# rel-8bit-computer.net
KiCad netlist of a schematic drawn in EAGLE
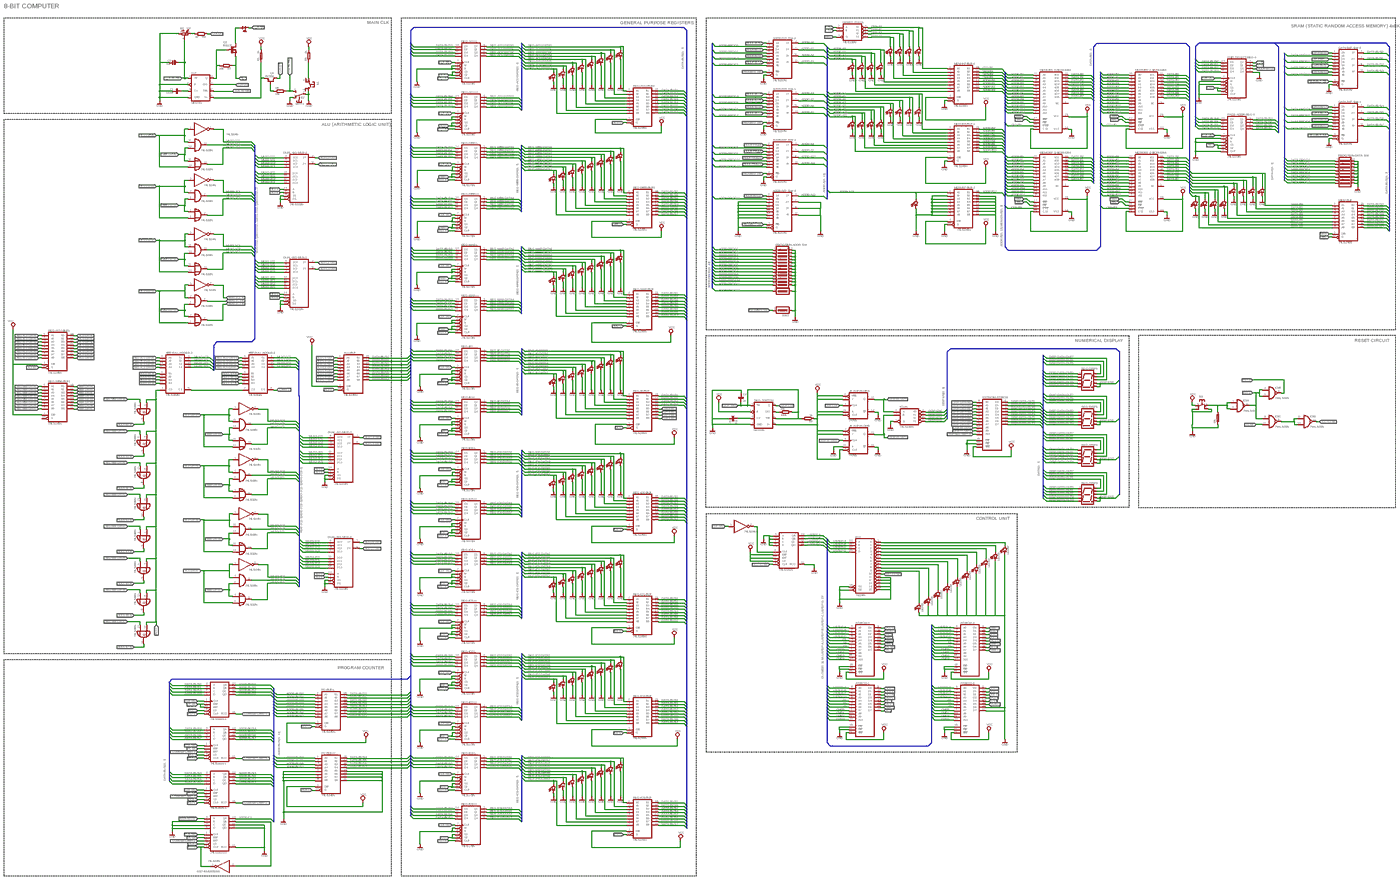
[diagram p0: schematic, sheet 1, overview]
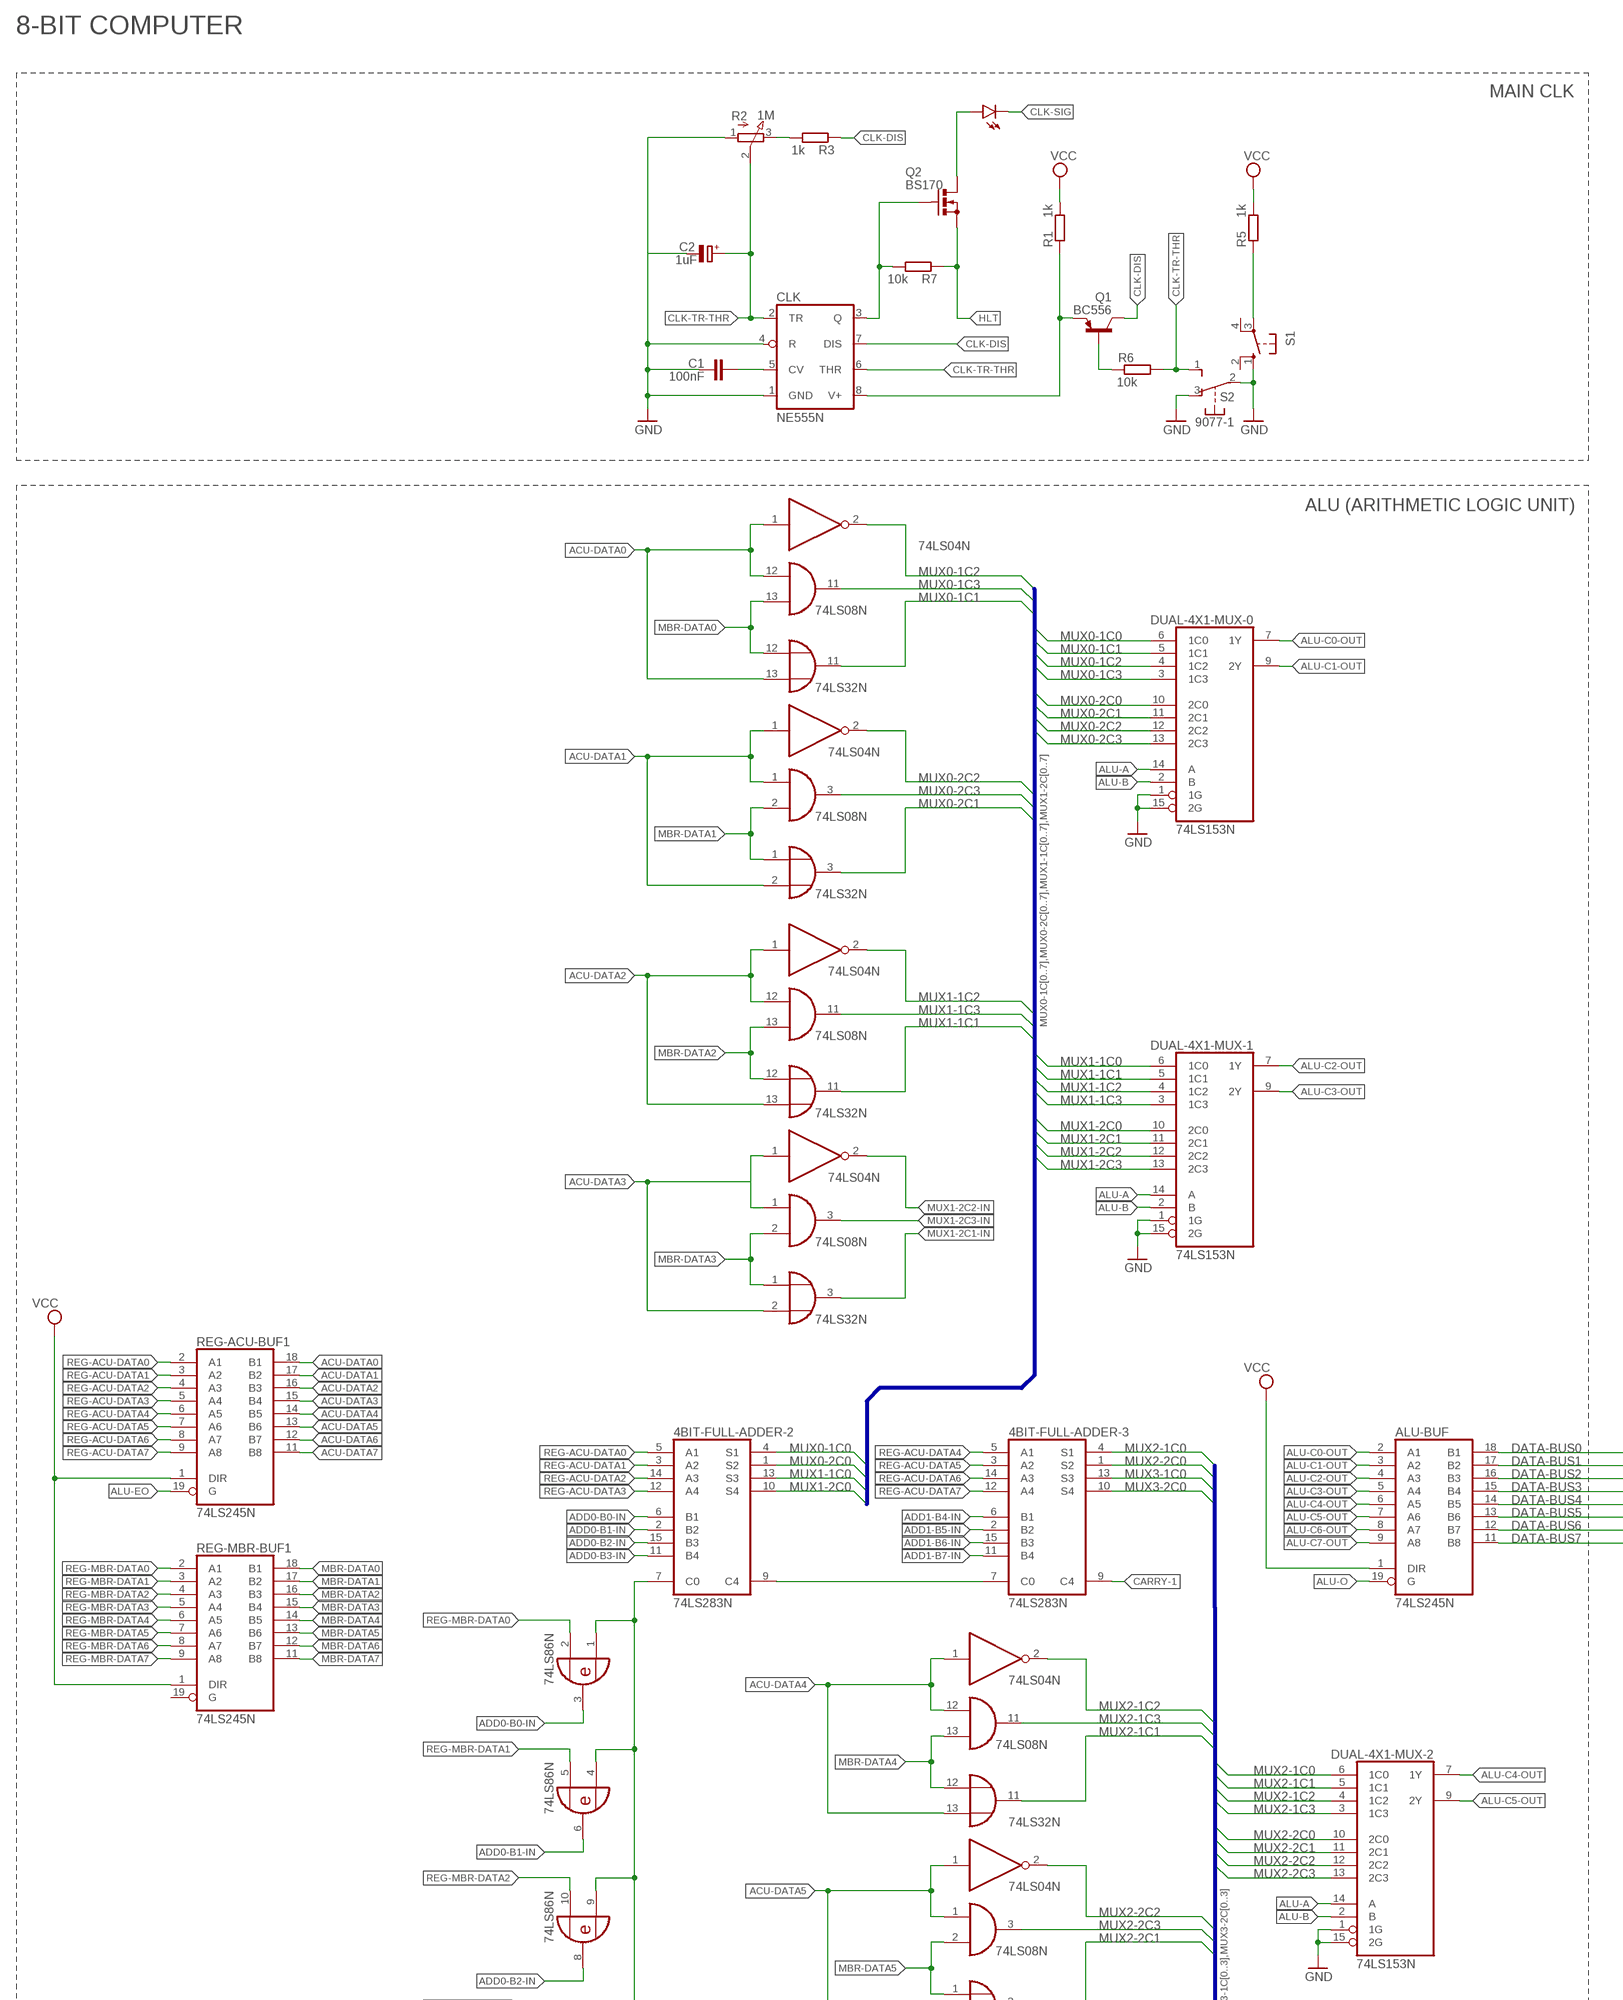
[diagram p1: schematic, sheet 1, part 1 of 8]
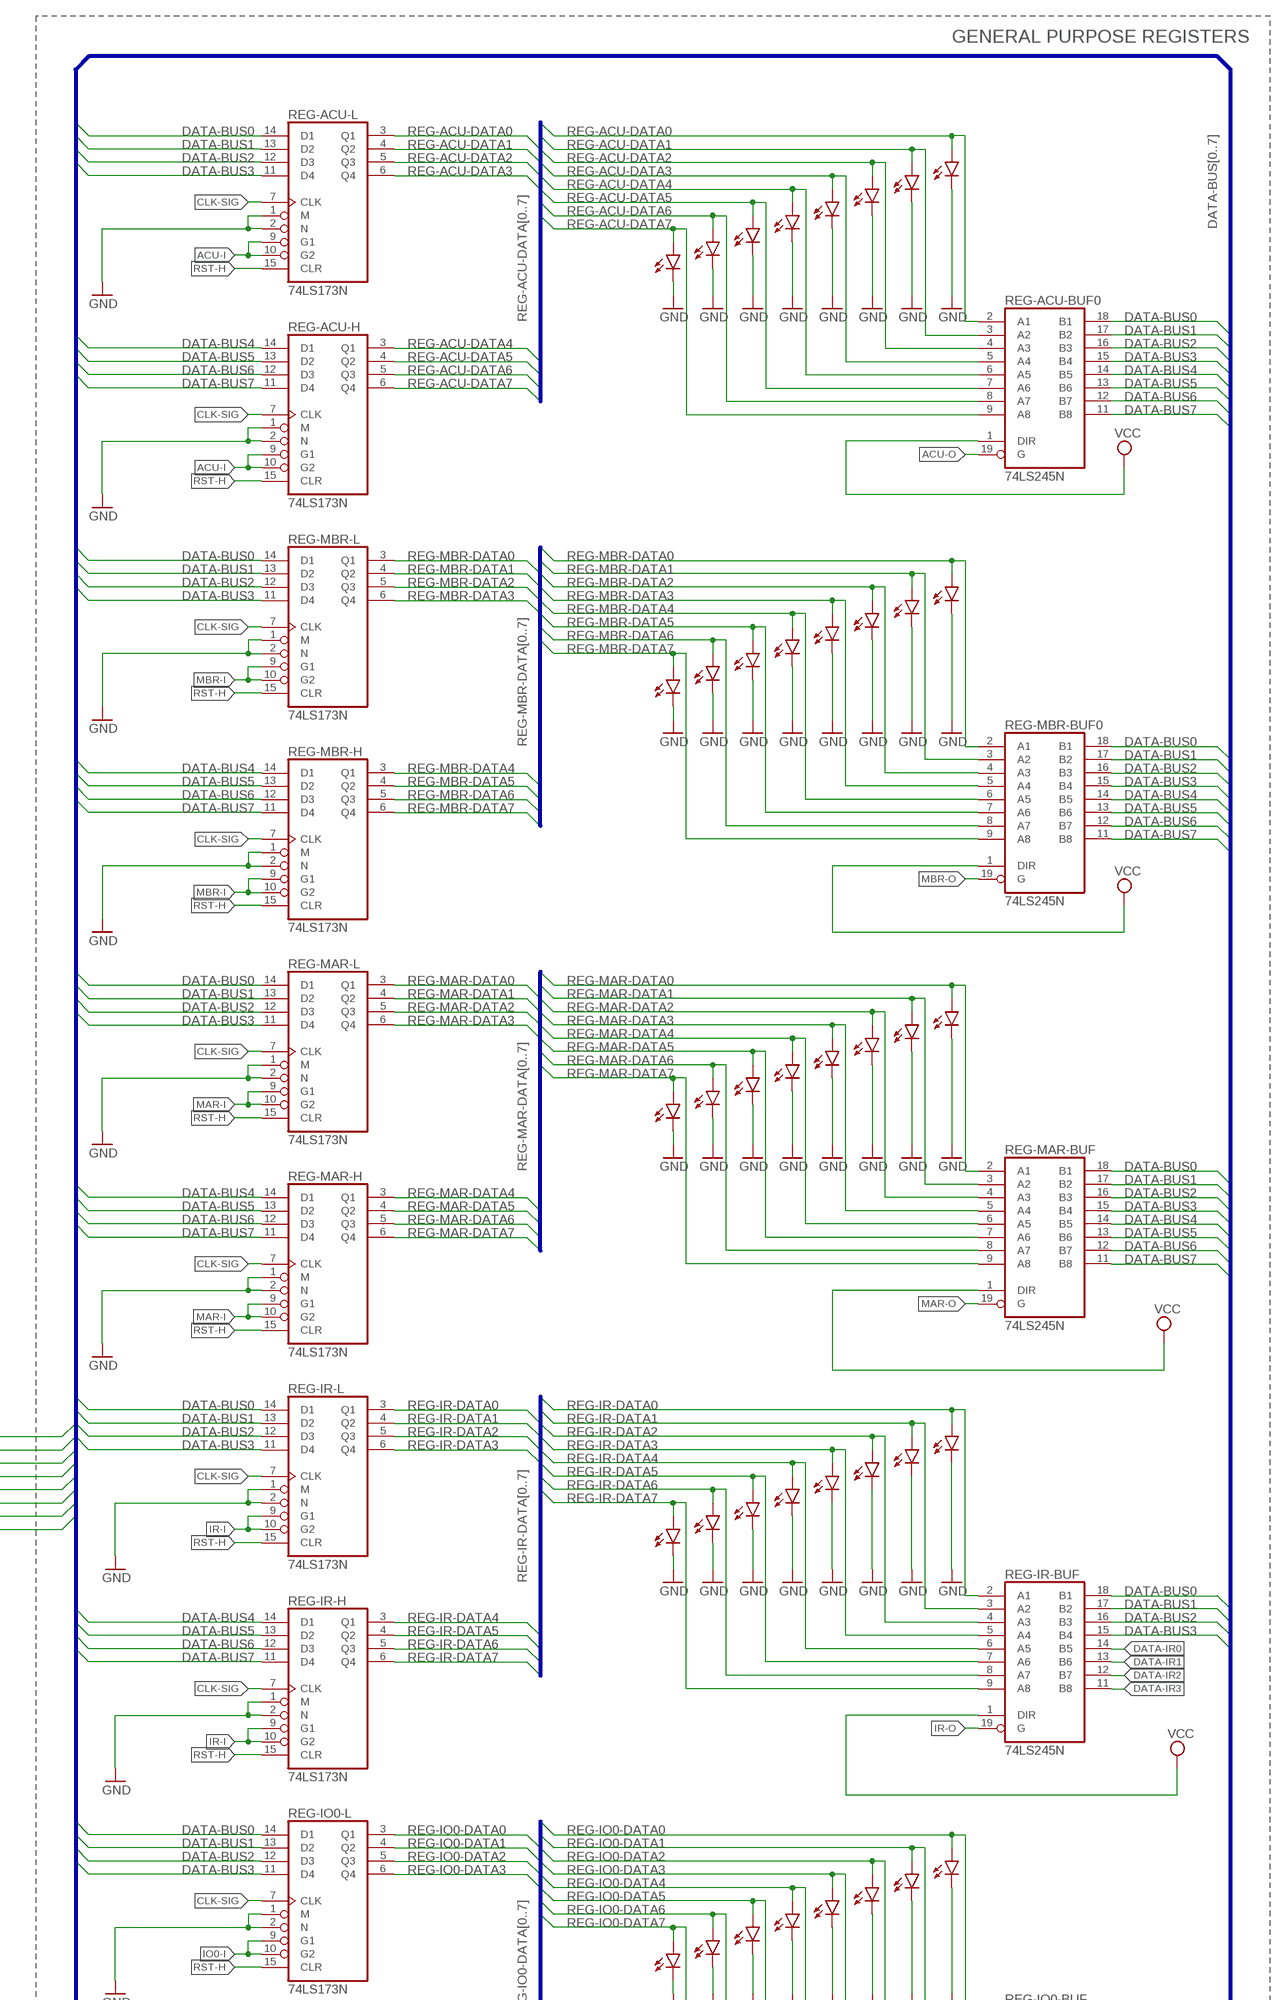
[diagram p2: schematic, sheet 1, part 2 of 8]
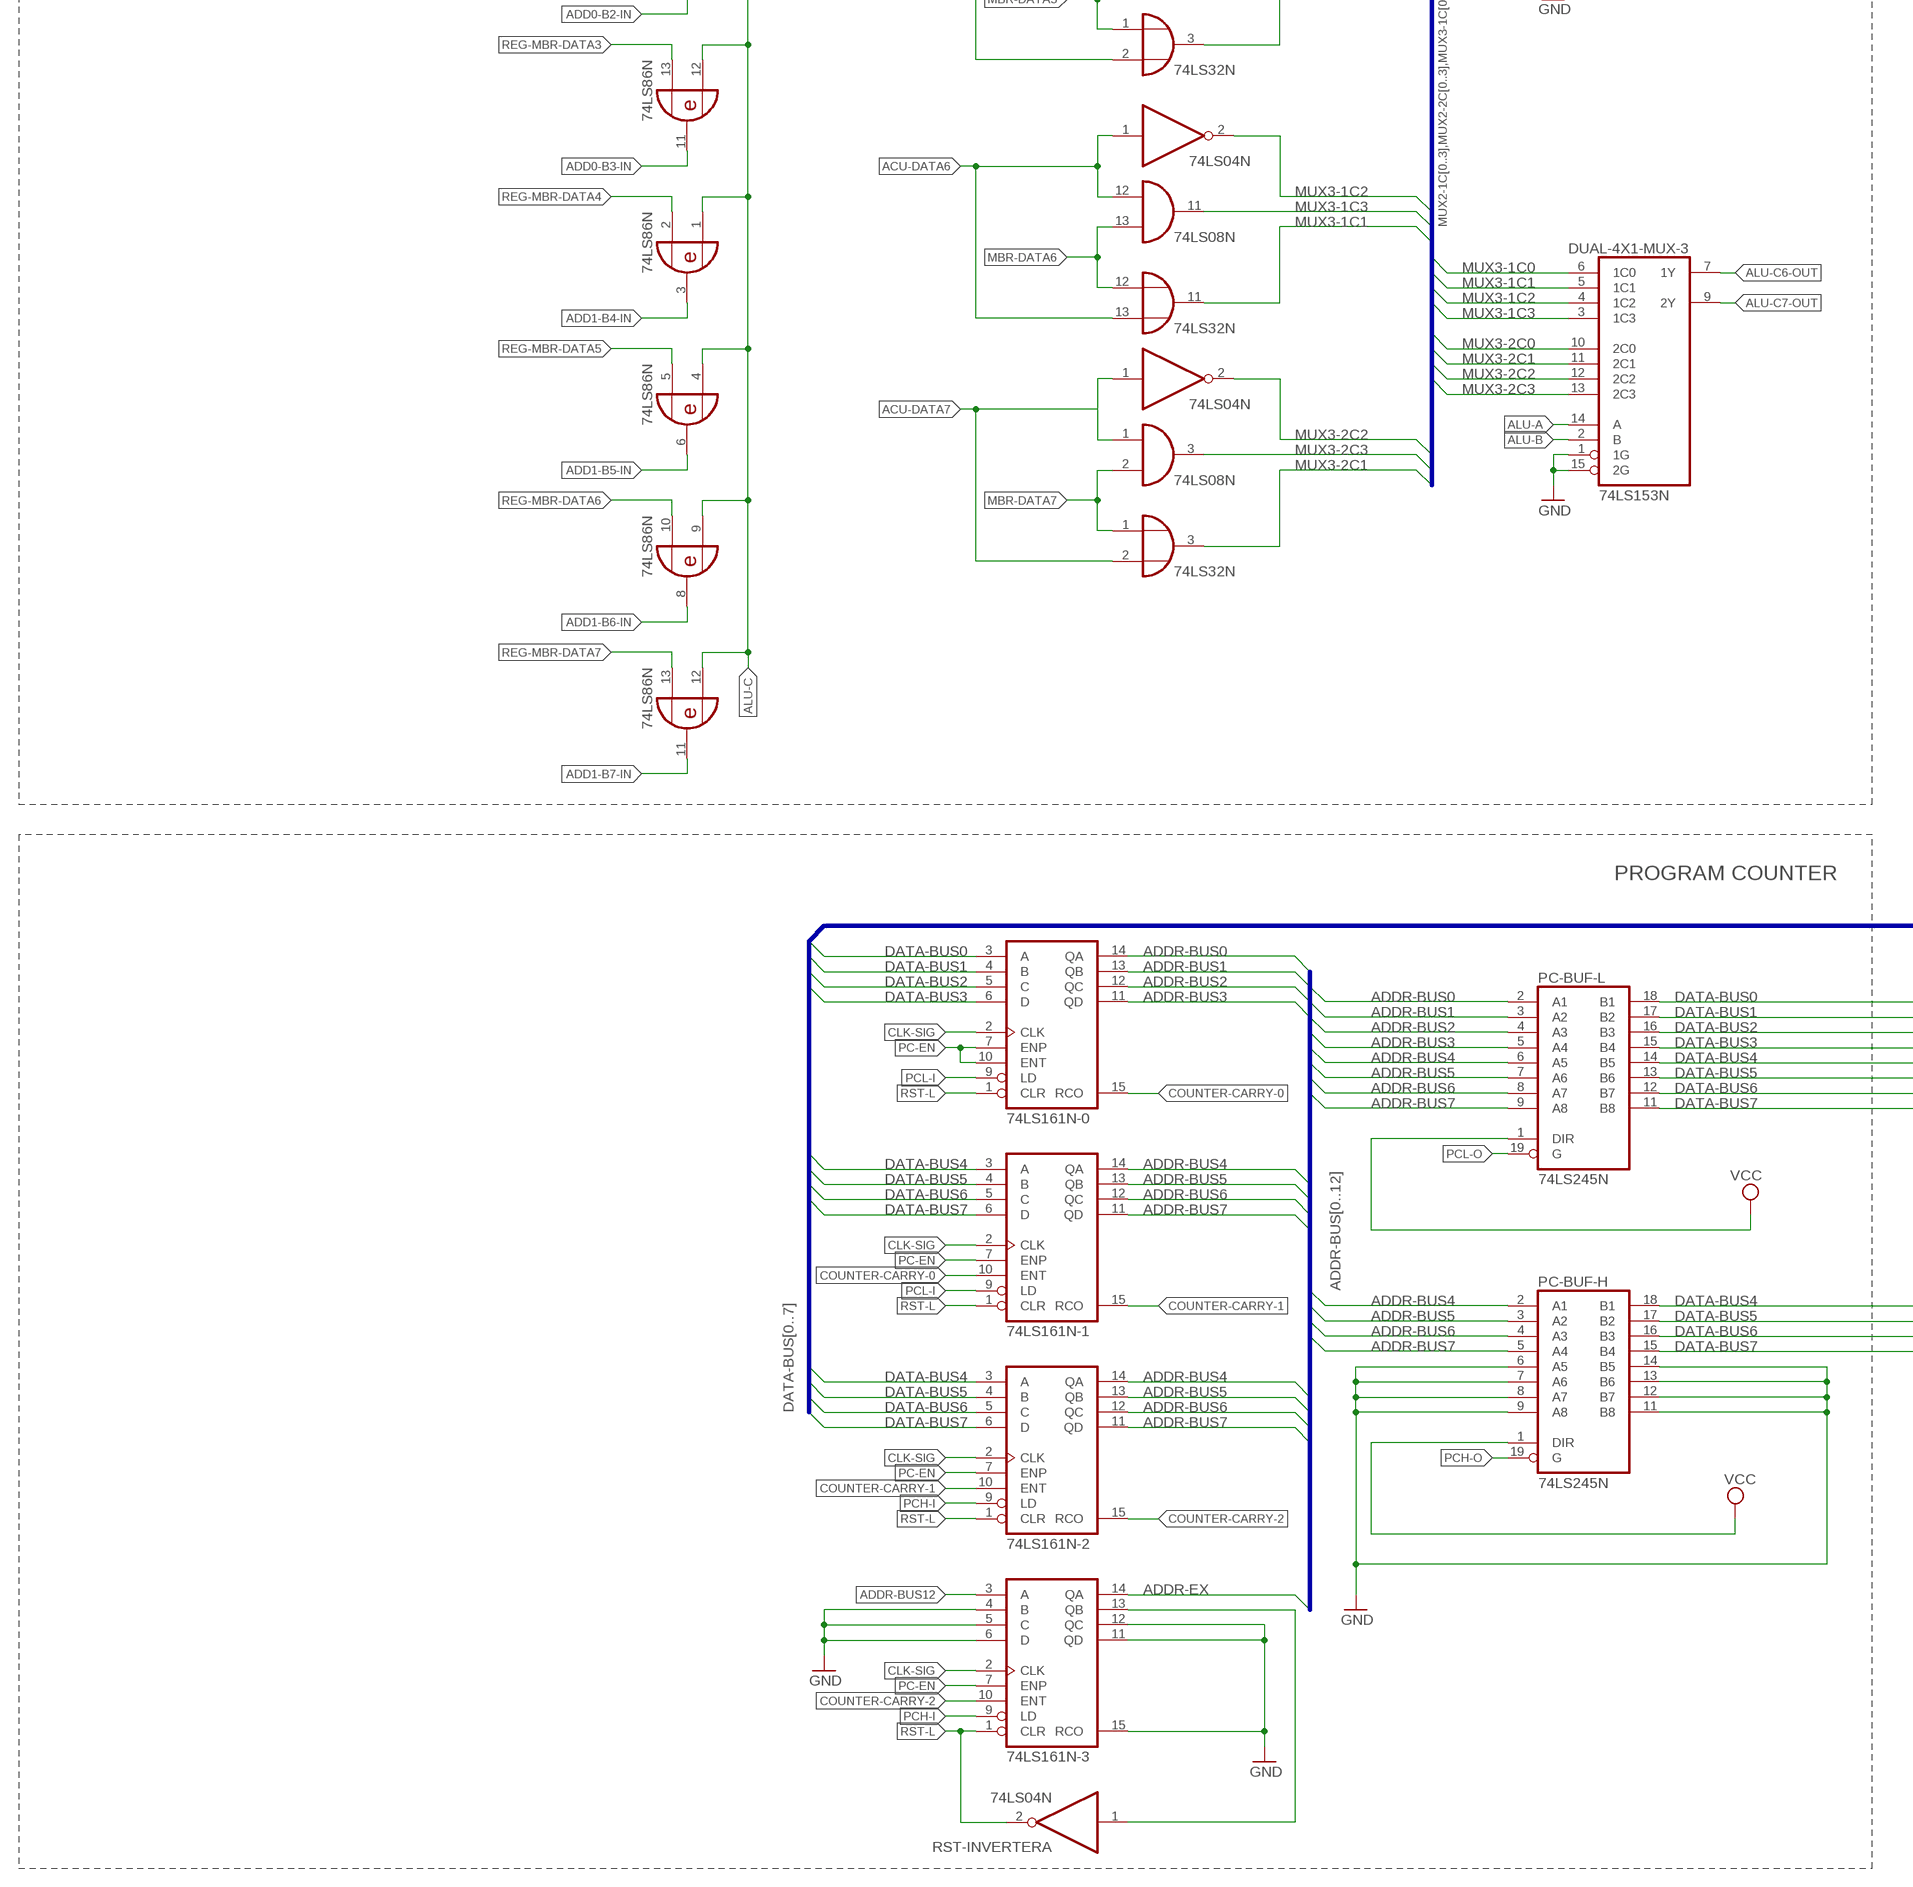
[diagram p3: schematic, sheet 1, part 3 of 8]
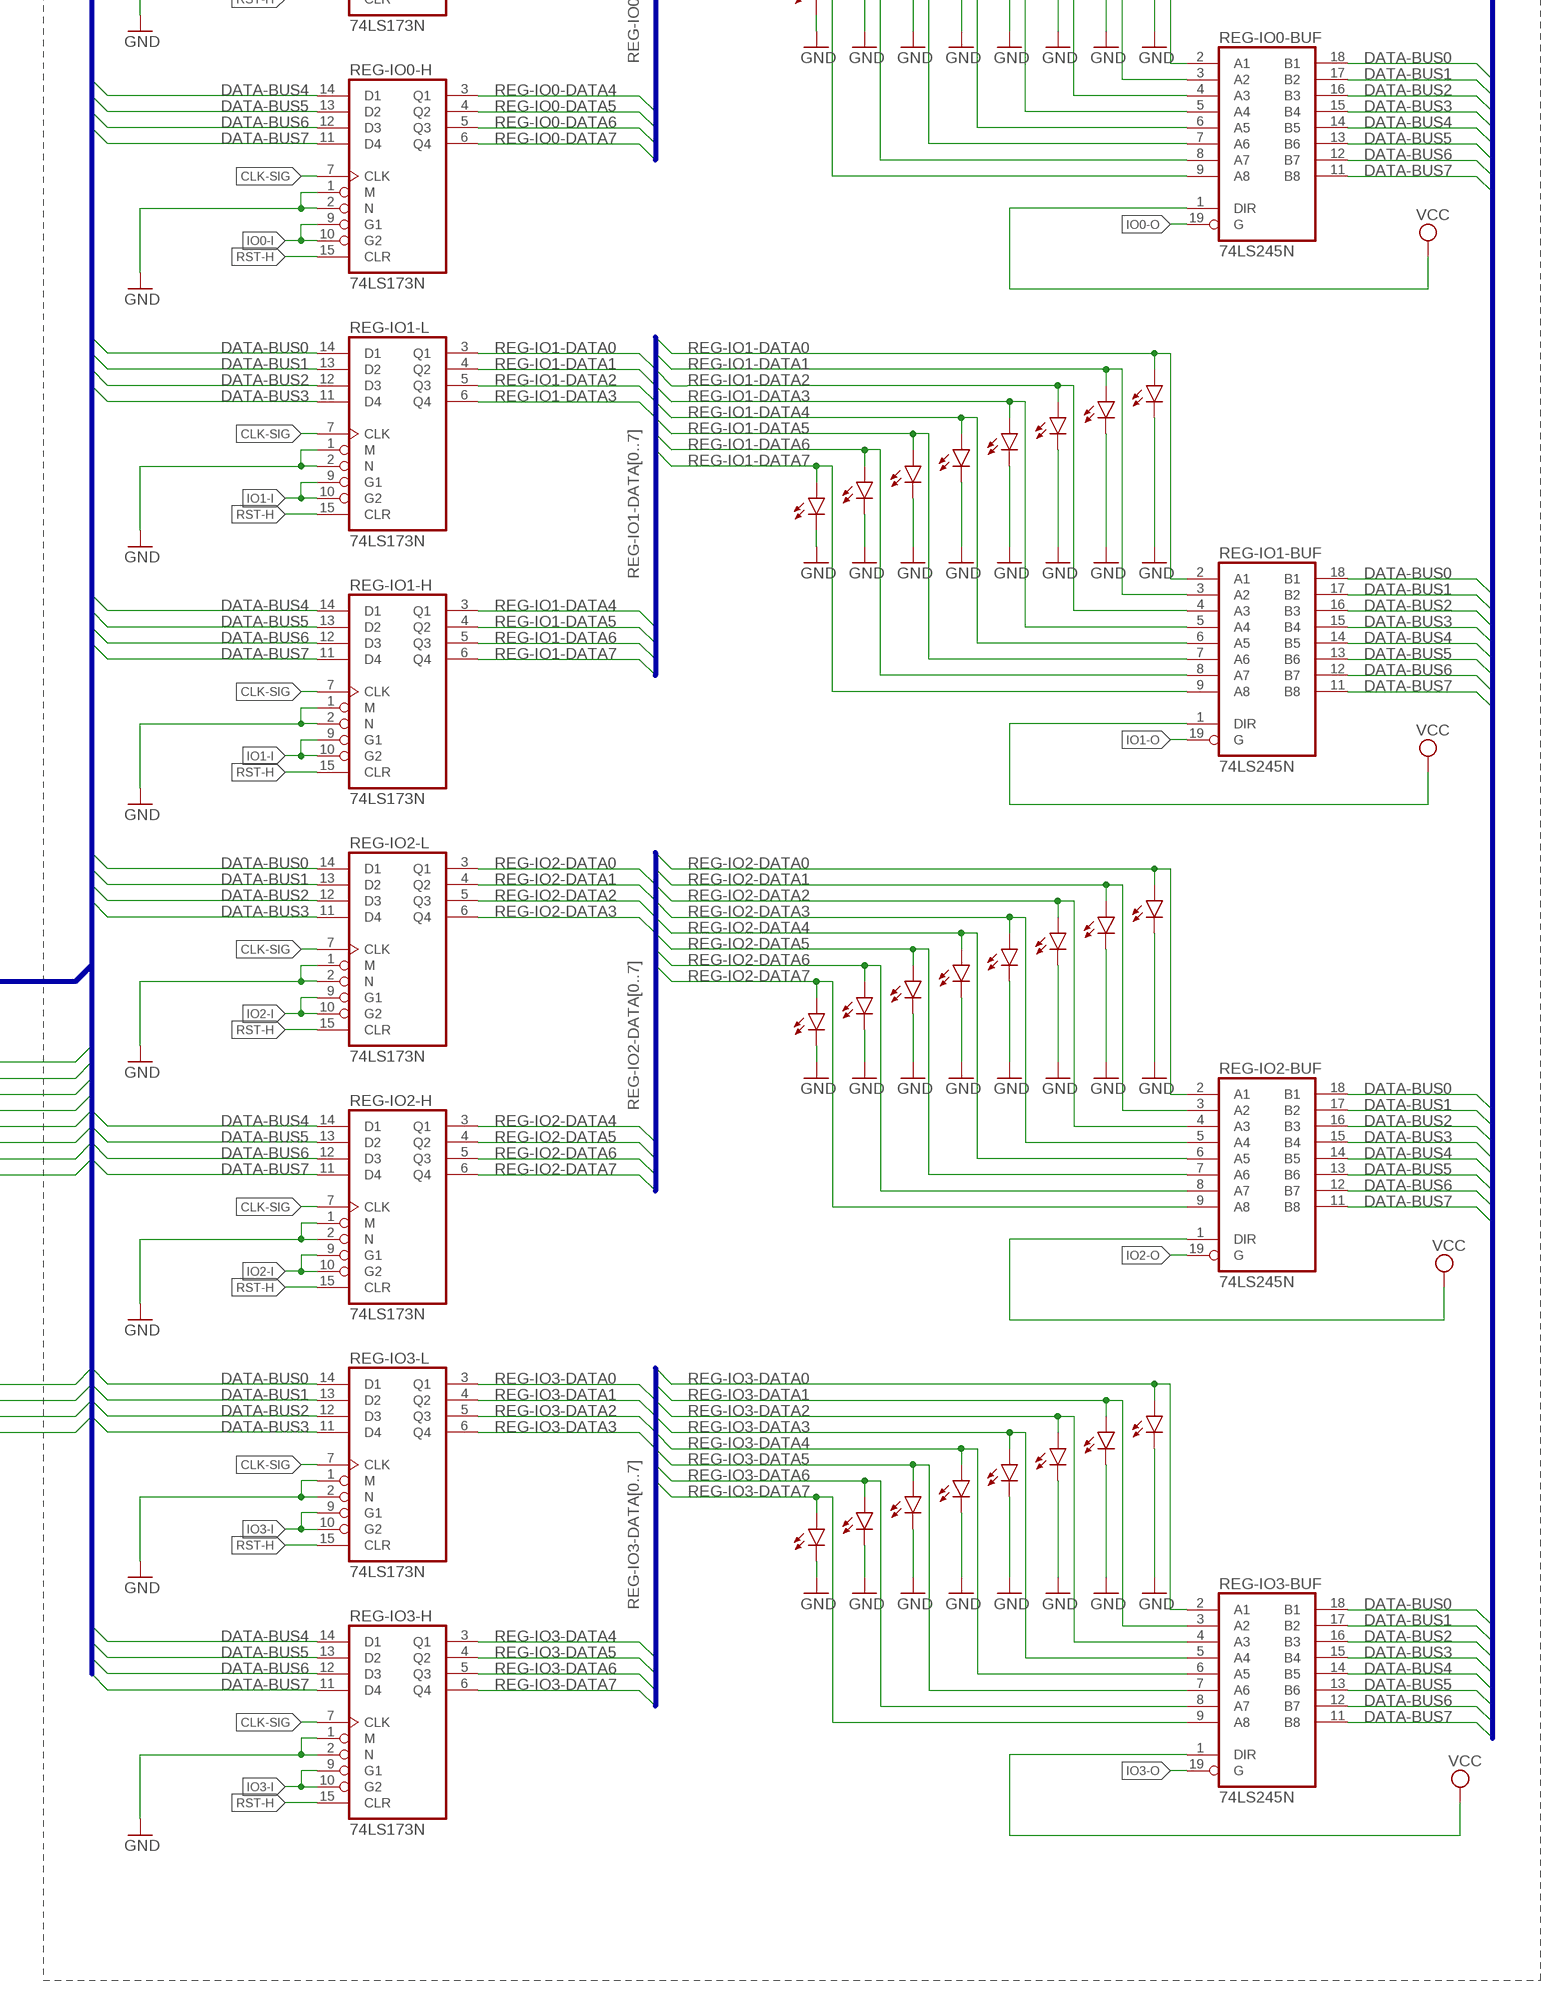
[diagram p4: schematic, sheet 1, part 4 of 8]
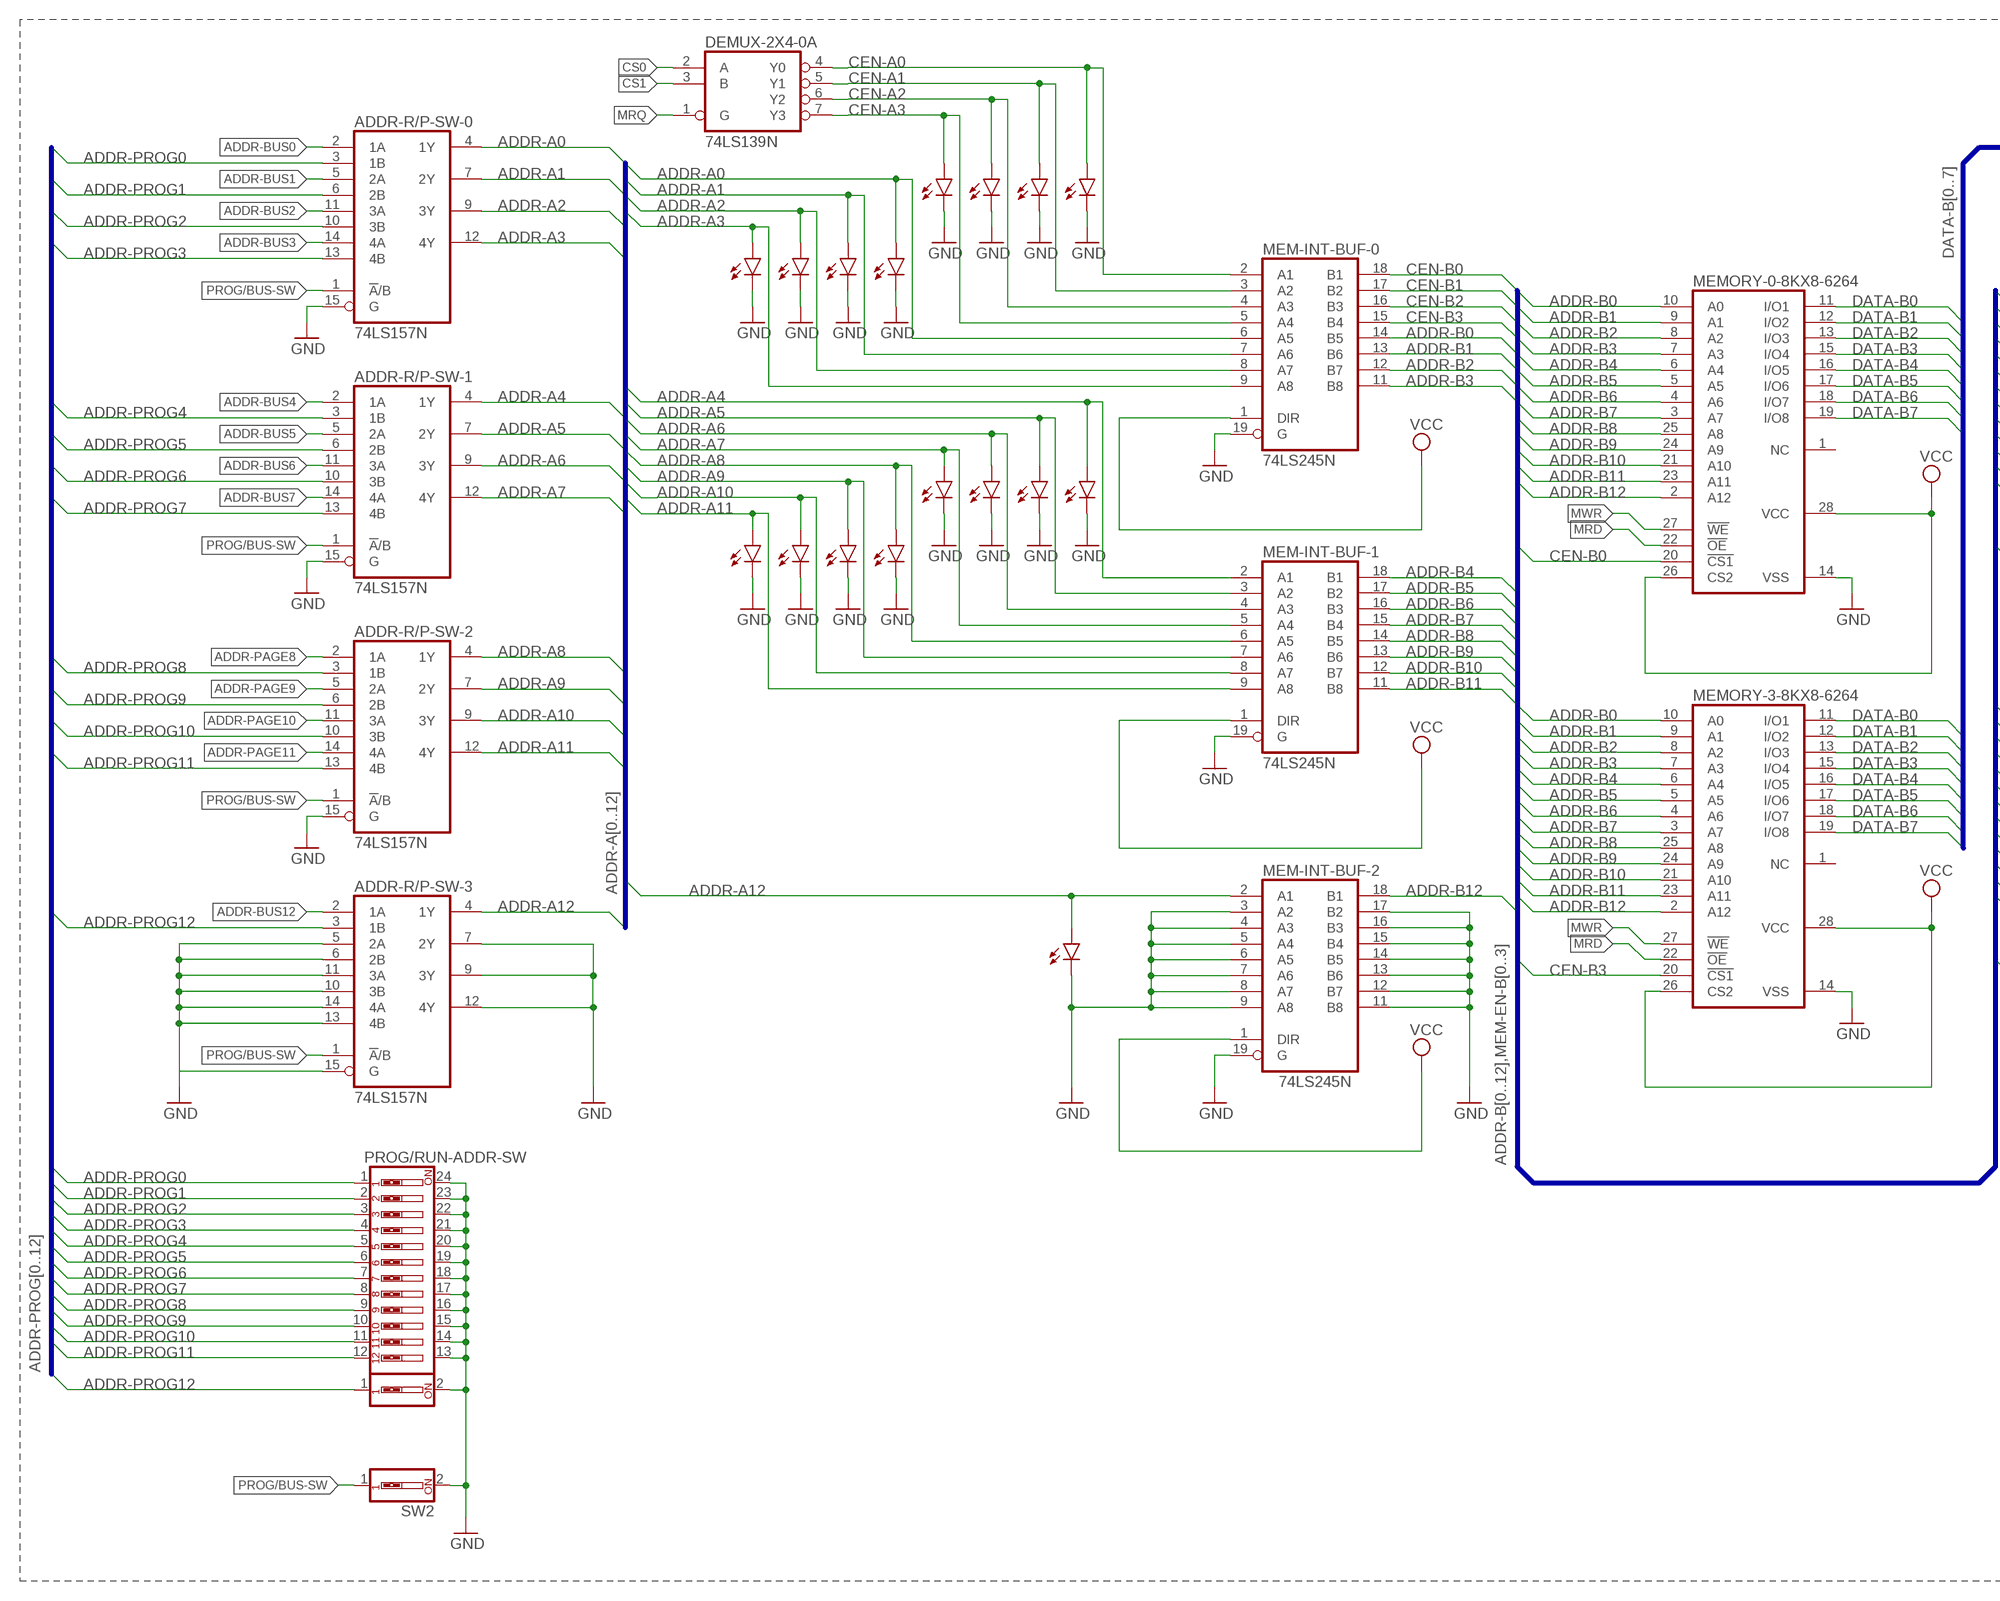
[diagram p5: schematic, sheet 1, part 5 of 8]
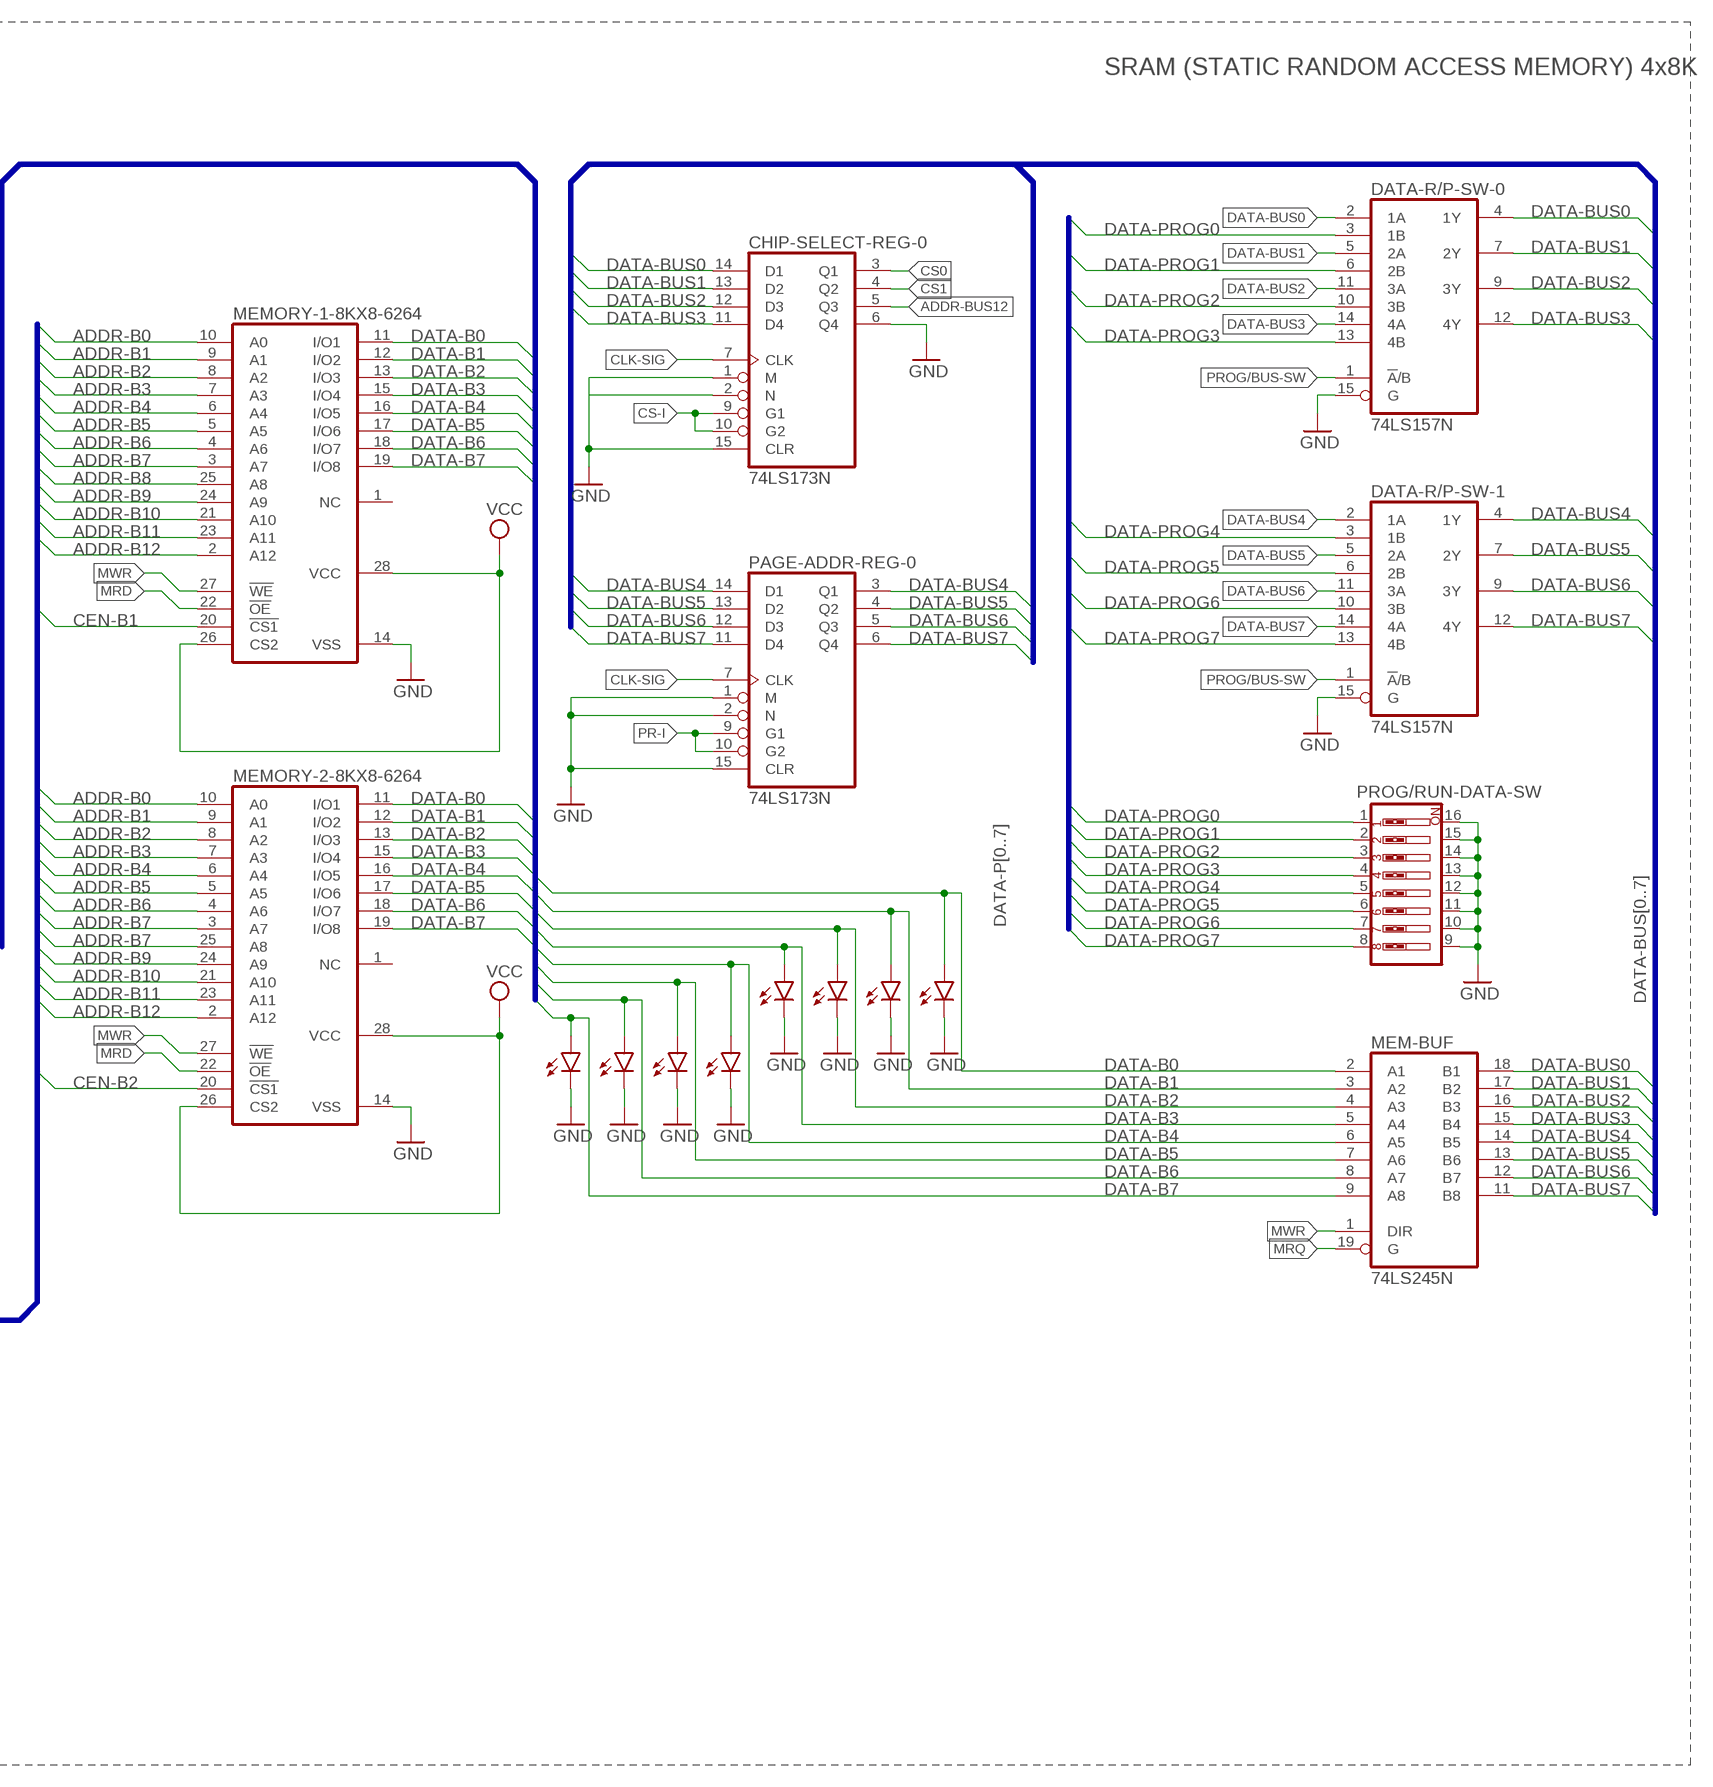
[diagram p6: schematic, sheet 1, part 6 of 8]
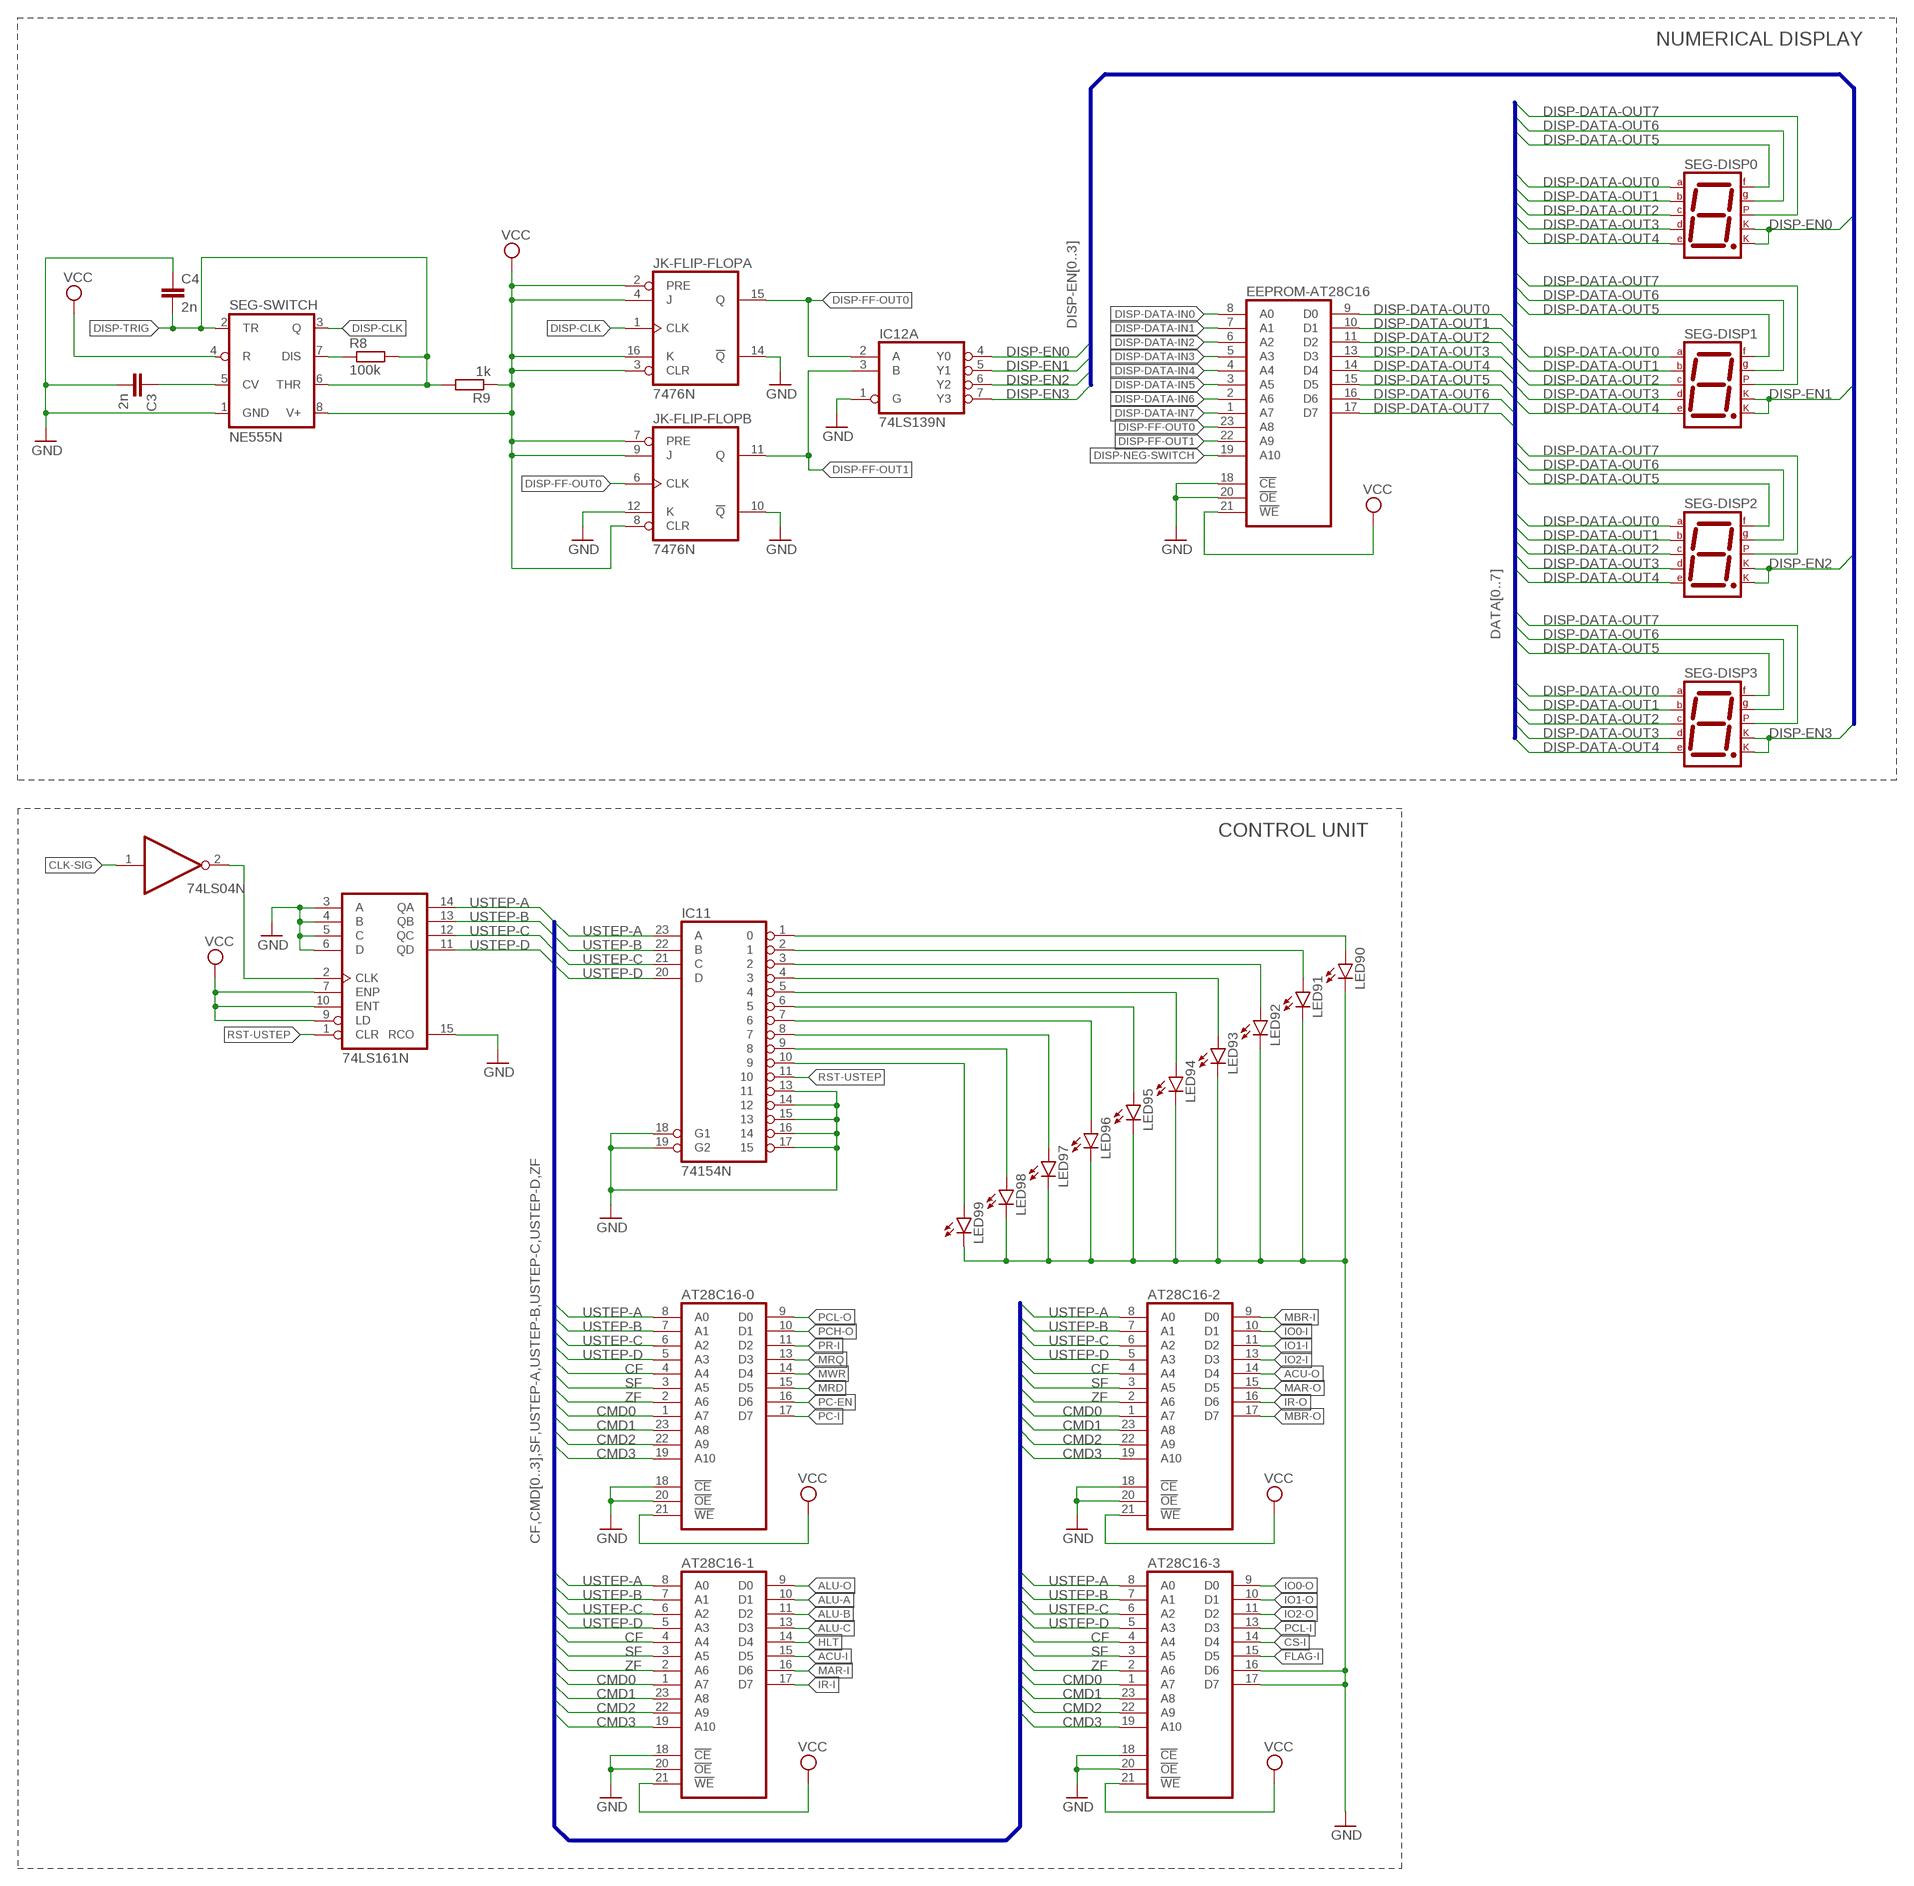
[diagram p7: schematic, sheet 1, part 7 of 8]
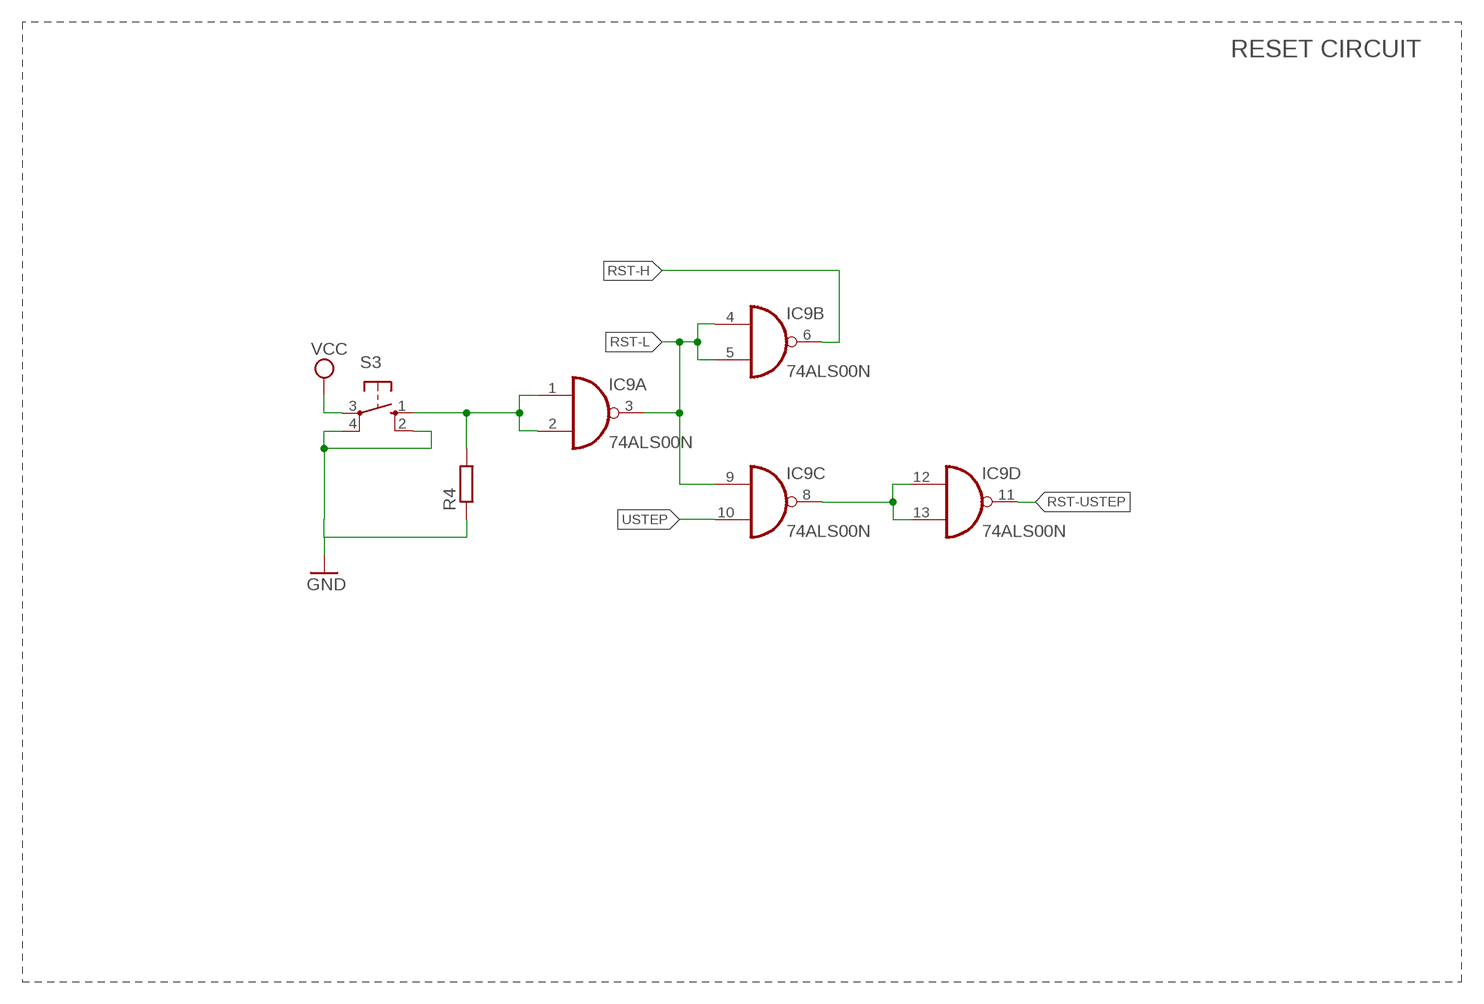
[diagram p8: schematic, sheet 1, part 8 of 8]

(export (version "E")
  (design (tool "Eeschema 10.0.6"))
  (components
    (comp (ref "4BIT-FULL-ADDER-2")
      (value "74LS283N")
      (footprint "eagle-import:DIL16")
      (libsource (lib "eagle-import") (part "74283NLS"))
    )
    (comp (ref "4BIT-FULL-ADDER-3")
      (value "74LS283N")
      (footprint "eagle-import:DIL16")
      (libsource (lib "eagle-import") (part "74283NLS"))
    )
    (comp (ref "74LS161N")
      (value "74160N")
      (footprint "eagle-import:DIL16")
      (libsource (lib "eagle-import") (part "74160N"))
    )
    (comp (ref "74LS161N-0")
      (value "74160N")
      (footprint "eagle-import:DIL16")
      (libsource (lib "eagle-import") (part "74160N"))
    )
    (comp (ref "74LS161N-1")
      (value "74160N")
      (footprint "eagle-import:DIL16")
      (libsource (lib "eagle-import") (part "74160N"))
    )
    (comp (ref "74LS161N-2")
      (value "74160N")
      (footprint "eagle-import:DIL16")
      (libsource (lib "eagle-import") (part "74160N"))
    )
    (comp (ref "74LS161N-3")
      (value "74160N")
      (footprint "eagle-import:DIL16")
      (libsource (lib "eagle-import") (part "74160N"))
    )
    (comp (ref "ADDR-R/P-SW-0")
      (value "74LS157N")
      (footprint "eagle-import:DIL16")
      (libsource (lib "eagle-import") (part "74157NLS"))
    )
    (comp (ref "ADDR-R/P-SW-1")
      (value "74LS157N")
      (footprint "eagle-import:DIL16")
      (libsource (lib "eagle-import") (part "74157NLS"))
    )
    (comp (ref "ADDR-R/P-SW-2")
      (value "74LS157N")
      (footprint "eagle-import:DIL16")
      (libsource (lib "eagle-import") (part "74157NLS"))
    )
    (comp (ref "ADDR-R/P-SW-3")
      (value "74LS157N")
      (footprint "eagle-import:DIL16")
      (libsource (lib "eagle-import") (part "74157NLS"))
    )
    (comp (ref "ALU-BUF")
      (value "74LS245N")
      (footprint "eagle-import:DIL20")
      (libsource (lib "eagle-import") (part "74245NLS"))
    )
    (comp (ref "AT28C16-0")
      (value "2816")
      (footprint "eagle-import:DIL24")
      (libsource (lib "eagle-import") (part "2816"))
    )
    (comp (ref "AT28C16-1")
      (value "2816")
      (footprint "eagle-import:DIL24")
      (libsource (lib "eagle-import") (part "2816"))
    )
    (comp (ref "AT28C16-2")
      (value "2816")
      (footprint "eagle-import:DIL24")
      (libsource (lib "eagle-import") (part "2816"))
    )
    (comp (ref "AT28C16-3")
      (value "2816")
      (footprint "eagle-import:DIL24")
      (libsource (lib "eagle-import") (part "2816"))
    )
    (comp (ref "C1")
      (value "100nF")
      (footprint "eagle-import:C025-050X050")
      (libsource (lib "eagle-import") (part "C-EU025-050X050"))
    )
    (comp (ref "C2")
      (value "1uF")
      (footprint "eagle-import:E2-5")
      (libsource (lib "eagle-import") (part "CPOL-EUE2-5"))
    )
    (comp (ref "C3")
      (value "2n")
      (footprint "eagle-import:C025-025X050")
      (libsource (lib "eagle-import") (part "C-EU025-025X050"))
    )
    (comp (ref "C4")
      (value "2n")
      (footprint "eagle-import:C025-025X050")
      (libsource (lib "eagle-import") (part "C-EU025-025X050"))
    )
    (comp (ref "CHIP-SELECT-REG-0")
      (value "74LS173N")
      (footprint "eagle-import:DIL16")
      (libsource (lib "eagle-import") (part "74173NLS"))
    )
    (comp (ref "CLK")
      (value "NE555N")
      (footprint "eagle-import:DIL08")
      (libsource (lib "eagle-import") (part "555NNE"))
    )
    (comp (ref "DATA-R/P-SW-0")
      (value "74LS157N")
      (footprint "eagle-import:DIL16")
      (libsource (lib "eagle-import") (part "74157NLS"))
    )
    (comp (ref "DATA-R/P-SW-1")
      (value "74LS157N")
      (footprint "eagle-import:DIL16")
      (libsource (lib "eagle-import") (part "74157NLS"))
    )
    (comp (ref "DEMUX-2X4-0")
      (value "74LS139N")
      (footprint "eagle-import:DIL16")
      (libsource (lib "eagle-import") (part "74139NLS"))
    )
    (comp (ref "DUAL-4X1-MUX-0")
      (value "74LS153N")
      (footprint "eagle-import:DIL16")
      (libsource (lib "eagle-import") (part "74153NLS"))
    )
    (comp (ref "DUAL-4X1-MUX-1")
      (value "74LS153N")
      (footprint "eagle-import:DIL16")
      (libsource (lib "eagle-import") (part "74153NLS"))
    )
    (comp (ref "DUAL-4X1-MUX-2")
      (value "74LS153N")
      (footprint "eagle-import:DIL16")
      (libsource (lib "eagle-import") (part "74153NLS"))
    )
    (comp (ref "DUAL-4X1-MUX-3")
      (value "74LS153N")
      (footprint "eagle-import:DIL16")
      (libsource (lib "eagle-import") (part "74153NLS"))
    )
    (comp (ref "EEPROM-AT28C16")
      (value "2816")
      (footprint "eagle-import:DIL24")
      (libsource (lib "eagle-import") (part "2816"))
    )
    (comp (ref "IC1")
      (value "74LS04N")
      (footprint "eagle-import:DIL14")
      (libsource (lib "eagle-import") (part "7404NLS"))
    )
    (comp (ref "IC2")
      (value "74LS04N")
      (footprint "eagle-import:DIL14")
      (libsource (lib "eagle-import") (part "7404NLS"))
    )
    (comp (ref "IC3")
      (value "74LS04N")
      (footprint "eagle-import:DIL14")
      (libsource (lib "eagle-import") (part "7404NLS"))
    )
    (comp (ref "IC4")
      (value "74LS04N")
      (footprint "eagle-import:DIL14")
      (libsource (lib "eagle-import") (part "7404NLS"))
    )
    (comp (ref "IC5")
      (value "74LS04N")
      (footprint "eagle-import:DIL14")
      (libsource (lib "eagle-import") (part "7404NLS"))
    )
    (comp (ref "IC6")
      (value "74LS04N")
      (footprint "eagle-import:DIL14")
      (libsource (lib "eagle-import") (part "7404NLS"))
    )
    (comp (ref "IC7")
      (value "74LS04N")
      (footprint "eagle-import:DIL14")
      (libsource (lib "eagle-import") (part "7404NLS"))
    )
    (comp (ref "IC8")
      (value "74LS04N")
      (footprint "eagle-import:DIL14")
      (libsource (lib "eagle-import") (part "7404NLS"))
    )
    (comp (ref "IC9")
      (value "74ALS00N")
      (footprint "eagle-import:DIL14")
      (libsource (lib "eagle-import") (part "7400NALS"))
    )
    (comp (ref "IC10")
      (value "74LS04N")
      (footprint "eagle-import:DIL14")
      (libsource (lib "eagle-import") (part "7404NLS"))
    )
    (comp (ref "IC11")
      (value "74154N")
      (footprint "eagle-import:DIL24-6")
      (libsource (lib "eagle-import") (part "74154N"))
    )
    (comp (ref "IC12")
      (value "74LS139N")
      (footprint "eagle-import:DIL16")
      (libsource (lib "eagle-import") (part "74139NLS"))
    )
    (comp (ref "IC35")
      (value "74LS32N")
      (footprint "eagle-import:DIL14")
      (libsource (lib "eagle-import") (part "7432NLS"))
    )
    (comp (ref "IC37")
      (value "74LS08N")
      (footprint "eagle-import:DIL14")
      (libsource (lib "eagle-import") (part "7408NLS"))
    )
    (comp (ref "IC38")
      (value "74LS08N")
      (footprint "eagle-import:DIL14")
      (libsource (lib "eagle-import") (part "7408NLS"))
    )
    (comp (ref "IC39")
      (value "74LS32N")
      (footprint "eagle-import:DIL14")
      (libsource (lib "eagle-import") (part "7432NLS"))
    )
    (comp (ref "IC41")
      (value "74LS08N")
      (footprint "eagle-import:DIL14")
      (libsource (lib "eagle-import") (part "7408NLS"))
    )
    (comp (ref "IC42")
      (value "74LS32N")
      (footprint "eagle-import:DIL14")
      (libsource (lib "eagle-import") (part "7432NLS"))
    )
    (comp (ref "IC44")
      (value "74LS08N")
      (footprint "eagle-import:DIL14")
      (libsource (lib "eagle-import") (part "7408NLS"))
    )
    (comp (ref "IC45")
      (value "74LS32N")
      (footprint "eagle-import:DIL14")
      (libsource (lib "eagle-import") (part "7432NLS"))
    )
    (comp (ref "IC46")
      (value "74LS86N")
      (footprint "eagle-import:DIL14")
      (libsource (lib "eagle-import") (part "7486NLS"))
    )
    (comp (ref "IC47")
      (value "74LS86N")
      (footprint "eagle-import:DIL14")
      (libsource (lib "eagle-import") (part "7486NLS"))
    )
    (comp (ref "IC48")
      (value "74LS32N")
      (footprint "eagle-import:DIL14")
      (libsource (lib "eagle-import") (part "7432NLS"))
    )
    (comp (ref "IC50")
      (value "74LS08N")
      (footprint "eagle-import:DIL14")
      (libsource (lib "eagle-import") (part "7408NLS"))
    )
    (comp (ref "IC51")
      (value "74LS08N")
      (footprint "eagle-import:DIL14")
      (libsource (lib "eagle-import") (part "7408NLS"))
    )
    (comp (ref "IC52")
      (value "74LS32N")
      (footprint "eagle-import:DIL14")
      (libsource (lib "eagle-import") (part "7432NLS"))
    )
    (comp (ref "IC54")
      (value "74LS08N")
      (footprint "eagle-import:DIL14")
      (libsource (lib "eagle-import") (part "7408NLS"))
    )
    (comp (ref "IC55")
      (value "74LS32N")
      (footprint "eagle-import:DIL14")
      (libsource (lib "eagle-import") (part "7432NLS"))
    )
    (comp (ref "IC57")
      (value "74LS08N")
      (footprint "eagle-import:DIL14")
      (libsource (lib "eagle-import") (part "7408NLS"))
    )
    (comp (ref "IC58")
      (value "74LS32N")
      (footprint "eagle-import:DIL14")
      (libsource (lib "eagle-import") (part "7432NLS"))
    )
    (comp (ref "JK-FLIP-FLOP")
      (value "7476N")
      (footprint "eagle-import:DIL16")
      (libsource (lib "eagle-import") (part "7476N"))
    )
    (comp (ref "LED0")
      (value "LED5MM")
      (footprint "eagle-import:LED5MM")
      (libsource (lib "eagle-import") (part "LED5MM"))
    )
    (comp (ref "LED1")
      (value "LED5MM")
      (footprint "eagle-import:LED5MM")
      (libsource (lib "eagle-import") (part "LED5MM"))
    )
    (comp (ref "LED2")
      (value "LED5MM")
      (footprint "eagle-import:LED5MM")
      (libsource (lib "eagle-import") (part "LED5MM"))
    )
    (comp (ref "LED3")
      (value "LED5MM")
      (footprint "eagle-import:LED5MM")
      (libsource (lib "eagle-import") (part "LED5MM"))
    )
    (comp (ref "LED4")
      (value "LED5MM")
      (footprint "eagle-import:LED5MM")
      (libsource (lib "eagle-import") (part "LED5MM"))
    )
    (comp (ref "LED5")
      (value "LED5MM")
      (footprint "eagle-import:LED5MM")
      (libsource (lib "eagle-import") (part "LED5MM"))
    )
    (comp (ref "LED6")
      (value "LED5MM")
      (footprint "eagle-import:LED5MM")
      (libsource (lib "eagle-import") (part "LED5MM"))
    )
    (comp (ref "LED7")
      (value "LED5MM")
      (footprint "eagle-import:LED5MM")
      (libsource (lib "eagle-import") (part "LED5MM"))
    )
    (comp (ref "LED8")
      (value "LED5MM")
      (footprint "eagle-import:LED5MM")
      (libsource (lib "eagle-import") (part "LED5MM"))
    )
    (comp (ref "LED9")
      (value "LED5MM")
      (footprint "eagle-import:LED5MM")
      (libsource (lib "eagle-import") (part "LED5MM"))
    )
    (comp (ref "LED10")
      (value "LED5MM")
      (footprint "eagle-import:LED5MM")
      (libsource (lib "eagle-import") (part "LED5MM"))
    )
    (comp (ref "LED11")
      (value "LED5MM")
      (footprint "eagle-import:LED5MM")
      (libsource (lib "eagle-import") (part "LED5MM"))
    )
    (comp (ref "LED12")
      (value "LED5MM")
      (footprint "eagle-import:LED5MM")
      (libsource (lib "eagle-import") (part "LED5MM"))
    )
    (comp (ref "LED13")
      (value "LED5MM")
      (footprint "eagle-import:LED5MM")
      (libsource (lib "eagle-import") (part "LED5MM"))
    )
    (comp (ref "LED14")
      (value "LED5MM")
      (footprint "eagle-import:LED5MM")
      (libsource (lib "eagle-import") (part "LED5MM"))
    )
    (comp (ref "LED15")
      (value "LED5MM")
      (footprint "eagle-import:LED5MM")
      (libsource (lib "eagle-import") (part "LED5MM"))
    )
    (comp (ref "LED16")
      (value "LED5MM")
      (footprint "eagle-import:LED5MM")
      (libsource (lib "eagle-import") (part "LED5MM"))
    )
    (comp (ref "LED17")
      (value "LED5MM")
      (footprint "eagle-import:LED5MM")
      (libsource (lib "eagle-import") (part "LED5MM"))
    )
    (comp (ref "LED18")
      (value "LED5MM")
      (footprint "eagle-import:LED5MM")
      (libsource (lib "eagle-import") (part "LED5MM"))
    )
    (comp (ref "LED19")
      (value "LED5MM")
      (footprint "eagle-import:LED5MM")
      (libsource (lib "eagle-import") (part "LED5MM"))
    )
    (comp (ref "LED20")
      (value "LED5MM")
      (footprint "eagle-import:LED5MM")
      (libsource (lib "eagle-import") (part "LED5MM"))
    )
    (comp (ref "LED21")
      (value "LED5MM")
      (footprint "eagle-import:LED5MM")
      (libsource (lib "eagle-import") (part "LED5MM"))
    )
    (comp (ref "LED22")
      (value "LED5MM")
      (footprint "eagle-import:LED5MM")
      (libsource (lib "eagle-import") (part "LED5MM"))
    )
    (comp (ref "LED23")
      (value "LED5MM")
      (footprint "eagle-import:LED5MM")
      (libsource (lib "eagle-import") (part "LED5MM"))
    )
    (comp (ref "LED24")
      (value "LED5MM")
      (footprint "eagle-import:LED5MM")
      (libsource (lib "eagle-import") (part "LED5MM"))
    )
    (comp (ref "LED25")
      (value "LED5MM")
      (footprint "eagle-import:LED5MM")
      (libsource (lib "eagle-import") (part "LED5MM"))
    )
    (comp (ref "LED26")
      (value "LED5MM")
      (footprint "eagle-import:LED5MM")
      (libsource (lib "eagle-import") (part "LED5MM"))
    )
    (comp (ref "LED27")
      (value "LED5MM")
      (footprint "eagle-import:LED5MM")
      (libsource (lib "eagle-import") (part "LED5MM"))
    )
    (comp (ref "LED28")
      (value "LED5MM")
      (footprint "eagle-import:LED5MM")
      (libsource (lib "eagle-import") (part "LED5MM"))
    )
    (comp (ref "LED29")
      (value "LED5MM")
      (footprint "eagle-import:LED5MM")
      (libsource (lib "eagle-import") (part "LED5MM"))
    )
    (comp (ref "LED30")
      (value "LED5MM")
      (footprint "eagle-import:LED5MM")
      (libsource (lib "eagle-import") (part "LED5MM"))
    )
    (comp (ref "LED31")
      (value "LED5MM")
      (footprint "eagle-import:LED5MM")
      (libsource (lib "eagle-import") (part "LED5MM"))
    )
    (comp (ref "LED32")
      (value "LED5MM")
      (footprint "eagle-import:LED5MM")
      (libsource (lib "eagle-import") (part "LED5MM"))
    )
    (comp (ref "LED33")
      (value "LED5MM")
      (footprint "eagle-import:LED5MM")
      (libsource (lib "eagle-import") (part "LED5MM"))
    )
    (comp (ref "LED34")
      (value "LED5MM")
      (footprint "eagle-import:LED5MM")
      (libsource (lib "eagle-import") (part "LED5MM"))
    )
    (comp (ref "LED35")
      (value "LED5MM")
      (footprint "eagle-import:LED5MM")
      (libsource (lib "eagle-import") (part "LED5MM"))
    )
    (comp (ref "LED36")
      (value "LED5MM")
      (footprint "eagle-import:LED5MM")
      (libsource (lib "eagle-import") (part "LED5MM"))
    )
    (comp (ref "LED37")
      (value "LED5MM")
      (footprint "eagle-import:LED5MM")
      (libsource (lib "eagle-import") (part "LED5MM"))
    )
    (comp (ref "LED38")
      (value "LED5MM")
      (footprint "eagle-import:LED5MM")
      (libsource (lib "eagle-import") (part "LED5MM"))
    )
    (comp (ref "LED39")
      (value "LED5MM")
      (footprint "eagle-import:LED5MM")
      (libsource (lib "eagle-import") (part "LED5MM"))
    )
    (comp (ref "LED40")
      (value "LED5MM")
      (footprint "eagle-import:LED5MM")
      (libsource (lib "eagle-import") (part "LED5MM"))
    )
    (comp (ref "LED41")
      (value "LED5MM")
      (footprint "eagle-import:LED5MM")
      (libsource (lib "eagle-import") (part "LED5MM"))
    )
    (comp (ref "LED42")
      (value "LED5MM")
      (footprint "eagle-import:LED5MM")
      (libsource (lib "eagle-import") (part "LED5MM"))
    )
    (comp (ref "LED43")
      (value "LED5MM")
      (footprint "eagle-import:LED5MM")
      (libsource (lib "eagle-import") (part "LED5MM"))
    )
    (comp (ref "LED44")
      (value "LED5MM")
      (footprint "eagle-import:LED5MM")
      (libsource (lib "eagle-import") (part "LED5MM"))
    )
    (comp (ref "LED45")
      (value "LED5MM")
      (footprint "eagle-import:LED5MM")
      (libsource (lib "eagle-import") (part "LED5MM"))
    )
    (comp (ref "LED46")
      (value "LED5MM")
      (footprint "eagle-import:LED5MM")
      (libsource (lib "eagle-import") (part "LED5MM"))
    )
    (comp (ref "LED47")
      (value "LED5MM")
      (footprint "eagle-import:LED5MM")
      (libsource (lib "eagle-import") (part "LED5MM"))
    )
    (comp (ref "LED48")
      (value "LED5MM")
      (footprint "eagle-import:LED5MM")
      (libsource (lib "eagle-import") (part "LED5MM"))
    )
    (comp (ref "LED49")
      (value "LED5MM")
      (footprint "eagle-import:LED5MM")
      (libsource (lib "eagle-import") (part "LED5MM"))
    )
    (comp (ref "LED50")
      (value "LED5MM")
      (footprint "eagle-import:LED5MM")
      (libsource (lib "eagle-import") (part "LED5MM"))
    )
    (comp (ref "LED51")
      (value "LED5MM")
      (footprint "eagle-import:LED5MM")
      (libsource (lib "eagle-import") (part "LED5MM"))
    )
    (comp (ref "LED52")
      (value "LED5MM")
      (footprint "eagle-import:LED5MM")
      (libsource (lib "eagle-import") (part "LED5MM"))
    )
    (comp (ref "LED53")
      (value "LED5MM")
      (footprint "eagle-import:LED5MM")
      (libsource (lib "eagle-import") (part "LED5MM"))
    )
    (comp (ref "LED54")
      (value "LED5MM")
      (footprint "eagle-import:LED5MM")
      (libsource (lib "eagle-import") (part "LED5MM"))
    )
    (comp (ref "LED55")
      (value "LED5MM")
      (footprint "eagle-import:LED5MM")
      (libsource (lib "eagle-import") (part "LED5MM"))
    )
    (comp (ref "LED56")
      (value "LED5MM")
      (footprint "eagle-import:LED5MM")
      (libsource (lib "eagle-import") (part "LED5MM"))
    )
    (comp (ref "LED57")
      (value "LED5MM")
      (footprint "eagle-import:LED5MM")
      (libsource (lib "eagle-import") (part "LED5MM"))
    )
    (comp (ref "LED58")
      (value "LED5MM")
      (footprint "eagle-import:LED5MM")
      (libsource (lib "eagle-import") (part "LED5MM"))
    )
    (comp (ref "LED59")
      (value "LED5MM")
      (footprint "eagle-import:LED5MM")
      (libsource (lib "eagle-import") (part "LED5MM"))
    )
    (comp (ref "LED60")
      (value "LED5MM")
      (footprint "eagle-import:LED5MM")
      (libsource (lib "eagle-import") (part "LED5MM"))
    )
    (comp (ref "LED61")
      (value "LED5MM")
      (footprint "eagle-import:LED5MM")
      (libsource (lib "eagle-import") (part "LED5MM"))
    )
    (comp (ref "LED62")
      (value "LED5MM")
      (footprint "eagle-import:LED5MM")
      (libsource (lib "eagle-import") (part "LED5MM"))
    )
    (comp (ref "LED63")
      (value "LED5MM")
      (footprint "eagle-import:LED5MM")
      (libsource (lib "eagle-import") (part "LED5MM"))
    )
    (comp (ref "LED64")
      (value "LED5MM")
      (footprint "eagle-import:LED5MM")
      (libsource (lib "eagle-import") (part "LED5MM"))
    )
    (comp (ref "LED65")
      (value "LED5MM")
      (footprint "eagle-import:LED5MM")
      (libsource (lib "eagle-import") (part "LED5MM"))
    )
    (comp (ref "LED66")
      (value "LED5MM")
      (footprint "eagle-import:LED5MM")
      (libsource (lib "eagle-import") (part "LED5MM"))
    )
    (comp (ref "LED67")
      (value "LED5MM")
      (footprint "eagle-import:LED5MM")
      (libsource (lib "eagle-import") (part "LED5MM"))
    )
    (comp (ref "LED68")
      (value "LED5MM")
      (footprint "eagle-import:LED5MM")
      (libsource (lib "eagle-import") (part "LED5MM"))
    )
    (comp (ref "LED69")
      (value "LED5MM")
      (footprint "eagle-import:LED5MM")
      (libsource (lib "eagle-import") (part "LED5MM"))
    )
    (comp (ref "LED70")
      (value "LED5MM")
      (footprint "eagle-import:LED5MM")
      (libsource (lib "eagle-import") (part "LED5MM"))
    )
    (comp (ref "LED71")
      (value "LED5MM")
      (footprint "eagle-import:LED5MM")
      (libsource (lib "eagle-import") (part "LED5MM"))
    )
    (comp (ref "LED72")
      (value "LED5MM")
      (footprint "eagle-import:LED5MM")
      (libsource (lib "eagle-import") (part "LED5MM"))
    )
    (comp (ref "LED73")
      (value "LED5MM")
      (footprint "eagle-import:LED5MM")
      (libsource (lib "eagle-import") (part "LED5MM"))
    )
    (comp (ref "LED74")
      (value "LED5MM")
      (footprint "eagle-import:LED5MM")
      (libsource (lib "eagle-import") (part "LED5MM"))
    )
    (comp (ref "LED75")
      (value "LED5MM")
      (footprint "eagle-import:LED5MM")
      (libsource (lib "eagle-import") (part "LED5MM"))
    )
    (comp (ref "LED76")
      (value "LED5MM")
      (footprint "eagle-import:LED5MM")
      (libsource (lib "eagle-import") (part "LED5MM"))
    )
    (comp (ref "LED77")
      (value "LED5MM")
      (footprint "eagle-import:LED5MM")
      (libsource (lib "eagle-import") (part "LED5MM"))
    )
    (comp (ref "LED78")
      (value "LED5MM")
      (footprint "eagle-import:LED5MM")
      (libsource (lib "eagle-import") (part "LED5MM"))
    )
    (comp (ref "LED79")
      (value "LED5MM")
      (footprint "eagle-import:LED5MM")
      (libsource (lib "eagle-import") (part "LED5MM"))
    )
    (comp (ref "LED80")
      (value "LED5MM")
      (footprint "eagle-import:LED5MM")
      (libsource (lib "eagle-import") (part "LED5MM"))
    )
    (comp (ref "LED81")
      (value "LED5MM")
      (footprint "eagle-import:LED5MM")
      (libsource (lib "eagle-import") (part "LED5MM"))
    )
    (comp (ref "LED82")
      (value "LED5MM")
      (footprint "eagle-import:LED5MM")
      (libsource (lib "eagle-import") (part "LED5MM"))
    )
    (comp (ref "LED83")
      (value "LED5MM")
      (footprint "eagle-import:LED5MM")
      (libsource (lib "eagle-import") (part "LED5MM"))
    )
    (comp (ref "LED84")
      (value "LED5MM")
      (footprint "eagle-import:LED5MM")
      (libsource (lib "eagle-import") (part "LED5MM"))
    )
    (comp (ref "LED85")
      (value "LED5MM")
      (footprint "eagle-import:LED5MM")
      (libsource (lib "eagle-import") (part "LED5MM"))
    )
    (comp (ref "LED86")
      (value "LED5MM")
      (footprint "eagle-import:LED5MM")
      (libsource (lib "eagle-import") (part "LED5MM"))
    )
    (comp (ref "LED87")
      (value "LED5MM")
      (footprint "eagle-import:LED5MM")
      (libsource (lib "eagle-import") (part "LED5MM"))
    )
    (comp (ref "LED88")
      (value "LED5MM")
      (footprint "eagle-import:LED5MM")
      (libsource (lib "eagle-import") (part "LED5MM"))
    )
    (comp (ref "LED89")
      (value "LED5MM")
      (footprint "eagle-import:LED5MM")
      (libsource (lib "eagle-import") (part "LED5MM"))
    )
    (comp (ref "LED90")
      (value "LED5MM")
      (footprint "eagle-import:LED5MM")
      (libsource (lib "eagle-import") (part "LED5MM"))
    )
    (comp (ref "LED91")
      (value "LED5MM")
      (footprint "eagle-import:LED5MM")
      (libsource (lib "eagle-import") (part "LED5MM"))
    )
    (comp (ref "LED92")
      (value "LED5MM")
      (footprint "eagle-import:LED5MM")
      (libsource (lib "eagle-import") (part "LED5MM"))
    )
    (comp (ref "LED93")
      (value "LED5MM")
      (footprint "eagle-import:LED5MM")
      (libsource (lib "eagle-import") (part "LED5MM"))
    )
    (comp (ref "LED94")
      (value "LED5MM")
      (footprint "eagle-import:LED5MM")
      (libsource (lib "eagle-import") (part "LED5MM"))
    )
    (comp (ref "LED95")
      (value "LED5MM")
      (footprint "eagle-import:LED5MM")
      (libsource (lib "eagle-import") (part "LED5MM"))
    )
    (comp (ref "LED96")
      (value "LED5MM")
      (footprint "eagle-import:LED5MM")
      (libsource (lib "eagle-import") (part "LED5MM"))
    )
    (comp (ref "LED97")
      (value "LED5MM")
      (footprint "eagle-import:LED5MM")
      (libsource (lib "eagle-import") (part "LED5MM"))
    )
    (comp (ref "LED98")
      (value "LED5MM")
      (footprint "eagle-import:LED5MM")
      (libsource (lib "eagle-import") (part "LED5MM"))
    )
    (comp (ref "LED99")
      (value "LED5MM")
      (footprint "eagle-import:LED5MM")
      (libsource (lib "eagle-import") (part "LED5MM"))
    )
    (comp (ref "MEM-BUF")
      (value "74LS245N")
      (footprint "eagle-import:DIL20")
      (libsource (lib "eagle-import") (part "74245NLS"))
    )
    (comp (ref "MEM-INT-BUF-0")
      (value "74LS245N")
      (footprint "eagle-import:DIL20")
      (libsource (lib "eagle-import") (part "74245NLS"))
    )
    (comp (ref "MEM-INT-BUF-1")
      (value "74LS245N")
      (footprint "eagle-import:DIL20")
      (libsource (lib "eagle-import") (part "74245NLS"))
    )
    (comp (ref "MEM-INT-BUF-2")
      (value "74LS245N")
      (footprint "eagle-import:DIL20")
      (libsource (lib "eagle-import") (part "74245NLS"))
    )
    (comp (ref "MEMORY-0-8KX8-6264")
      (value "6264A")
      (footprint "eagle-import:DIL28-6")
      (libsource (lib "eagle-import") (part "6264A"))
    )
    (comp (ref "MEMORY-1-8KX8-6264")
      (value "6264A")
      (footprint "eagle-import:DIL28-6")
      (libsource (lib "eagle-import") (part "6264A"))
    )
    (comp (ref "MEMORY-2-8KX8-6264")
      (value "6264A")
      (footprint "eagle-import:DIL28-6")
      (libsource (lib "eagle-import") (part "6264A"))
    )
    (comp (ref "MEMORY-3-8KX8-6264")
      (value "6264A")
      (footprint "eagle-import:DIL28-6")
      (libsource (lib "eagle-import") (part "6264A"))
    )
    (comp (ref "PAGE-ADDR-REG-0")
      (value "74LS173N")
      (footprint "eagle-import:DIL16")
      (libsource (lib "eagle-import") (part "74173NLS"))
    )
    (comp (ref "PC-BUF-H")
      (value "74LS245N")
      (footprint "eagle-import:DIL20")
      (libsource (lib "eagle-import") (part "74245NLS"))
    )
    (comp (ref "PC-BUF-L")
      (value "74LS245N")
      (footprint "eagle-import:DIL20")
      (libsource (lib "eagle-import") (part "74245NLS"))
    )
    (comp (ref "PROG/RUN-ADDR-SW")
      (value "SW_DIP-12")
      (footprint "eagle-import:EDG-12")
      (libsource (lib "eagle-import") (part "SW_DIP-12"))
    )
    (comp (ref "PROG/RUN-DATA-SW")
      (value "SW_DIP-8")
      (footprint "eagle-import:EDG-08")
      (libsource (lib "eagle-import") (part "SW_DIP-8"))
    )
    (comp (ref "Q1")
      (value "BC556")
      (footprint "eagle-import:TO92-EBC")
      (libsource (lib "eagle-import") (part "BC556"))
    )
    (comp (ref "Q2")
      (value "BS170")
      (footprint "eagle-import:SOT54E")
      (libsource (lib "eagle-import") (part "BS170"))
    )
    (comp (ref "R1")
      (value "1k")
      (footprint "eagle-import:0204_5")
      (libsource (lib "eagle-import") (part "R-EU_0204/5"))
    )
    (comp (ref "R2")
      (value "1M")
      (footprint "eagle-import:3RP_1610N")
      (libsource (lib "eagle-import") (part "3RP/1610N"))
    )
    (comp (ref "R3")
      (value "1k")
      (footprint "eagle-import:0204_5")
      (libsource (lib "eagle-import") (part "R-EU_0204/5"))
    )
    (comp (ref "R4")
      (value "R-EU_0204/5")
      (footprint "eagle-import:0204_5")
      (libsource (lib "eagle-import") (part "R-EU_0204/5"))
    )
    (comp (ref "R5")
      (value "1k")
      (footprint "eagle-import:0204_5")
      (libsource (lib "eagle-import") (part "R-EU_0204/5"))
    )
    (comp (ref "R6")
      (value "10k")
      (footprint "eagle-import:0204_5")
      (libsource (lib "eagle-import") (part "R-EU_0204/5"))
    )
    (comp (ref "R7")
      (value "10k")
      (footprint "eagle-import:0204_5")
      (libsource (lib "eagle-import") (part "R-EU_0204/5"))
    )
    (comp (ref "R8")
      (value "100k")
      (footprint "eagle-import:0204_5")
      (libsource (lib "eagle-import") (part "R-EU_0204/5"))
    )
    (comp (ref "R9")
      (value "1k")
      (footprint "eagle-import:0204_5")
      (libsource (lib "eagle-import") (part "R-EU_0204/5"))
    )
    (comp (ref "REG-ACU-BUF0")
      (value "74LS245N")
      (footprint "eagle-import:DIL20")
      (libsource (lib "eagle-import") (part "74245NLS"))
    )
    (comp (ref "REG-ACU-BUF1")
      (value "74LS245N")
      (footprint "eagle-import:DIL20")
      (libsource (lib "eagle-import") (part "74245NLS"))
    )
    (comp (ref "REG-ACU-H")
      (value "74LS173N")
      (footprint "eagle-import:DIL16")
      (libsource (lib "eagle-import") (part "74173NLS"))
    )
    (comp (ref "REG-ACU-L")
      (value "74LS173N")
      (footprint "eagle-import:DIL16")
      (libsource (lib "eagle-import") (part "74173NLS"))
    )
    (comp (ref "REG-IO0-BUF")
      (value "74LS245N")
      (footprint "eagle-import:DIL20")
      (libsource (lib "eagle-import") (part "74245NLS"))
    )
    (comp (ref "REG-IO0-H")
      (value "74LS173N")
      (footprint "eagle-import:DIL16")
      (libsource (lib "eagle-import") (part "74173NLS"))
    )
    (comp (ref "REG-IO0-L")
      (value "74LS173N")
      (footprint "eagle-import:DIL16")
      (libsource (lib "eagle-import") (part "74173NLS"))
    )
    (comp (ref "REG-IO1-BUF")
      (value "74LS245N")
      (footprint "eagle-import:DIL20")
      (libsource (lib "eagle-import") (part "74245NLS"))
    )
    (comp (ref "REG-IO1-H")
      (value "74LS173N")
      (footprint "eagle-import:DIL16")
      (libsource (lib "eagle-import") (part "74173NLS"))
    )
    (comp (ref "REG-IO1-L")
      (value "74LS173N")
      (footprint "eagle-import:DIL16")
      (libsource (lib "eagle-import") (part "74173NLS"))
    )
    (comp (ref "REG-IO2-BUF")
      (value "74LS245N")
      (footprint "eagle-import:DIL20")
      (libsource (lib "eagle-import") (part "74245NLS"))
    )
    (comp (ref "REG-IO2-H")
      (value "74LS173N")
      (footprint "eagle-import:DIL16")
      (libsource (lib "eagle-import") (part "74173NLS"))
    )
    (comp (ref "REG-IO2-L")
      (value "74LS173N")
      (footprint "eagle-import:DIL16")
      (libsource (lib "eagle-import") (part "74173NLS"))
    )
    (comp (ref "REG-IO3-BUF")
      (value "74LS245N")
      (footprint "eagle-import:DIL20")
      (libsource (lib "eagle-import") (part "74245NLS"))
    )
    (comp (ref "REG-IO3-H")
      (value "74LS173N")
      (footprint "eagle-import:DIL16")
      (libsource (lib "eagle-import") (part "74173NLS"))
    )
    (comp (ref "REG-IO3-L")
      (value "74LS173N")
      (footprint "eagle-import:DIL16")
      (libsource (lib "eagle-import") (part "74173NLS"))
    )
    (comp (ref "REG-IR-BUF")
      (value "74LS245N")
      (footprint "eagle-import:DIL20")
      (libsource (lib "eagle-import") (part "74245NLS"))
    )
    (comp (ref "REG-IR-H")
      (value "74LS173N")
      (footprint "eagle-import:DIL16")
      (libsource (lib "eagle-import") (part "74173NLS"))
    )
    (comp (ref "REG-IR-L")
      (value "74LS173N")
      (footprint "eagle-import:DIL16")
      (libsource (lib "eagle-import") (part "74173NLS"))
    )
    (comp (ref "REG-MAR-BUF")
      (value "74LS245N")
      (footprint "eagle-import:DIL20")
      (libsource (lib "eagle-import") (part "74245NLS"))
    )
    (comp (ref "REG-MAR-H")
      (value "74LS173N")
      (footprint "eagle-import:DIL16")
      (libsource (lib "eagle-import") (part "74173NLS"))
    )
    (comp (ref "REG-MAR-L")
      (value "74LS173N")
      (footprint "eagle-import:DIL16")
      (libsource (lib "eagle-import") (part "74173NLS"))
    )
    (comp (ref "REG-MBR-BUF0")
      (value "74LS245N")
      (footprint "eagle-import:DIL20")
      (libsource (lib "eagle-import") (part "74245NLS"))
    )
    (comp (ref "REG-MBR-BUF1")
      (value "74LS245N")
      (footprint "eagle-import:DIL20")
      (libsource (lib "eagle-import") (part "74245NLS"))
    )
    (comp (ref "REG-MBR-H")
      (value "74LS173N")
      (footprint "eagle-import:DIL16")
      (libsource (lib "eagle-import") (part "74173NLS"))
    )
    (comp (ref "REG-MBR-L")
      (value "74LS173N")
      (footprint "eagle-import:DIL16")
      (libsource (lib "eagle-import") (part "74173NLS"))
    )
    (comp (ref "RST-INVERTER")
      (value "74LS04N")
      (footprint "eagle-import:DIL14")
      (libsource (lib "eagle-import") (part "7404NLS"))
    )
    (comp (ref "S1")
      (value "10-XX")
      (footprint "eagle-import:B3F-10XX")
      (fields (field (name "MPN") "B3F-1000"))
      (libsource (lib "eagle-import") (part "10-XX"))
    )
    (comp (ref "S2")
      (value "9077-1")
      (footprint "eagle-import:9077-1")
      (libsource (lib "eagle-import") (part "9077-1"))
    )
    (comp (ref "S3")
      (value "10-XX")
      (footprint "eagle-import:B3F-10XX")
      (fields (field (name "MPN") "B3F-1000"))
      (libsource (lib "eagle-import") (part "10-XX"))
    )
    (comp (ref "SEG-DISP0")
      (value "7SEG-CK")
      (footprint "eagle-import:7SEG-13")
      (libsource (lib "eagle-import") (part "7SEG-CK"))
    )
    (comp (ref "SEG-DISP1")
      (value "7SEG-CK")
      (footprint "eagle-import:7SEG-13")
      (libsource (lib "eagle-import") (part "7SEG-CK"))
    )
    (comp (ref "SEG-DISP2")
      (value "7SEG-CK")
      (footprint "eagle-import:7SEG-13")
      (libsource (lib "eagle-import") (part "7SEG-CK"))
    )
    (comp (ref "SEG-DISP3")
      (value "7SEG-CK")
      (footprint "eagle-import:7SEG-13")
      (libsource (lib "eagle-import") (part "7SEG-CK"))
    )
    (comp (ref "SEG-SWITCH")
      (value "NE555N")
      (footprint "eagle-import:DIL08")
      (libsource (lib "eagle-import") (part "555NNE"))
    )
    (comp (ref "SW2")
      (value "SW_DIP-1")
      (footprint "eagle-import:EDG-01")
      (libsource (lib "eagle-import") (part "SW_DIP-1"))
    )
    (comp (ref "SW3")
      (value "SW_DIP-1")
      (footprint "eagle-import:EDG-01")
      (libsource (lib "eagle-import") (part "SW_DIP-1"))
    )
  )
  (nets
    (net (code "21") (name "/ADDR-A0") (class "Default")
      (node (ref "ADDR-R/P-SW-0") (pin "4") (pinfunction "1Y_4") (pintype "output"))
      (node (ref "LED2") (pin "A") (pinfunction "A_A") (pintype "passive"))
      (node (ref "MEM-INT-BUF-0") (pin "6") (pinfunction "A5_6") (pintype "bidirectional"))
    )
    (net (code "22") (name "/ADDR-A1") (class "Default")
      (node (ref "ADDR-R/P-SW-0") (pin "7") (pinfunction "2Y_7") (pintype "output"))
      (node (ref "LED3") (pin "A") (pinfunction "A_A") (pintype "passive"))
      (node (ref "MEM-INT-BUF-0") (pin "7") (pinfunction "A6_7") (pintype "bidirectional"))
    )
    (net (code "23") (name "/ADDR-A2") (class "Default")
      (node (ref "ADDR-R/P-SW-0") (pin "9") (pinfunction "3Y_9") (pintype "output"))
      (node (ref "LED4") (pin "A") (pinfunction "A_A") (pintype "passive"))
      (node (ref "MEM-INT-BUF-0") (pin "8") (pinfunction "A7_8") (pintype "bidirectional"))
    )
    (net (code "24") (name "/ADDR-A3") (class "Default")
      (node (ref "ADDR-R/P-SW-0") (pin "12") (pinfunction "4Y_12") (pintype "output"))
      (node (ref "LED5") (pin "A") (pinfunction "A_A") (pintype "passive"))
      (node (ref "MEM-INT-BUF-0") (pin "9") (pinfunction "A8_9") (pintype "bidirectional"))
    )
    (net (code "25") (name "/ADDR-A4") (class "Default")
      (node (ref "ADDR-R/P-SW-1") (pin "4") (pinfunction "1Y_4") (pintype "output"))
      (node (ref "LED6") (pin "A") (pinfunction "A_A") (pintype "passive"))
      (node (ref "MEM-INT-BUF-1") (pin "2") (pinfunction "A1_2") (pintype "bidirectional"))
    )
    (net (code "26") (name "/ADDR-A5") (class "Default")
      (node (ref "ADDR-R/P-SW-1") (pin "7") (pinfunction "2Y_7") (pintype "output"))
      (node (ref "LED7") (pin "A") (pinfunction "A_A") (pintype "passive"))
      (node (ref "MEM-INT-BUF-1") (pin "3") (pinfunction "A2_3") (pintype "bidirectional"))
    )
    (net (code "27") (name "/ADDR-A6") (class "Default")
      (node (ref "ADDR-R/P-SW-1") (pin "9") (pinfunction "3Y_9") (pintype "output"))
      (node (ref "LED11") (pin "A") (pinfunction "A_A") (pintype "passive"))
      (node (ref "MEM-INT-BUF-1") (pin "4") (pinfunction "A3_4") (pintype "bidirectional"))
    )
    (net (code "28") (name "/ADDR-A7") (class "Default")
      (node (ref "ADDR-R/P-SW-1") (pin "12") (pinfunction "4Y_12") (pintype "output"))
      (node (ref "LED8") (pin "A") (pinfunction "A_A") (pintype "passive"))
      (node (ref "MEM-INT-BUF-1") (pin "5") (pinfunction "A4_5") (pintype "bidirectional"))
    )
    (net (code "29") (name "/ADDR-A8") (class "Default")
      (node (ref "ADDR-R/P-SW-2") (pin "4") (pinfunction "1Y_4") (pintype "output"))
      (node (ref "LED9") (pin "A") (pinfunction "A_A") (pintype "passive"))
      (node (ref "MEM-INT-BUF-1") (pin "6") (pinfunction "A5_6") (pintype "bidirectional"))
    )
    (net (code "30") (name "/ADDR-A9") (class "Default")
      (node (ref "ADDR-R/P-SW-2") (pin "7") (pinfunction "2Y_7") (pintype "output"))
      (node (ref "LED10") (pin "A") (pinfunction "A_A") (pintype "passive"))
      (node (ref "MEM-INT-BUF-1") (pin "7") (pinfunction "A6_7") (pintype "bidirectional"))
    )
    (net (code "31") (name "/ADDR-A10") (class "Default")
      (node (ref "ADDR-R/P-SW-2") (pin "9") (pinfunction "3Y_9") (pintype "output"))
      (node (ref "LED16") (pin "A") (pinfunction "A_A") (pintype "passive"))
      (node (ref "MEM-INT-BUF-1") (pin "8") (pinfunction "A7_8") (pintype "bidirectional"))
    )
    (net (code "32") (name "/ADDR-A11") (class "Default")
      (node (ref "ADDR-R/P-SW-2") (pin "12") (pinfunction "4Y_12") (pintype "output"))
      (node (ref "LED17") (pin "A") (pinfunction "A_A") (pintype "passive"))
      (node (ref "MEM-INT-BUF-1") (pin "9") (pinfunction "A8_9") (pintype "bidirectional"))
    )
    (net (code "33") (name "/ADDR-A12") (class "Default")
      (node (ref "ADDR-R/P-SW-3") (pin "4") (pinfunction "1Y_4") (pintype "output"))
      (node (ref "LED26") (pin "A") (pinfunction "A_A") (pintype "passive"))
      (node (ref "MEM-INT-BUF-2") (pin "2") (pinfunction "A1_2") (pintype "bidirectional"))
    )
    (net (code "35") (name "/ADDR-B0") (class "Default")
      (node (ref "MEM-INT-BUF-0") (pin "14") (pinfunction "B5_14") (pintype "bidirectional"))
      (node (ref "MEMORY-0-8KX8-6264") (pin "10") (pinfunction "A0_10") (pintype "input"))
      (node (ref "MEMORY-1-8KX8-6264") (pin "10") (pinfunction "A0_10") (pintype "input"))
      (node (ref "MEMORY-2-8KX8-6264") (pin "10") (pinfunction "A0_10") (pintype "input"))
      (node (ref "MEMORY-3-8KX8-6264") (pin "10") (pinfunction "A0_10") (pintype "input"))
    )
    (net (code "36") (name "/ADDR-B1") (class "Default")
      (node (ref "MEM-INT-BUF-0") (pin "13") (pinfunction "B6_13") (pintype "bidirectional"))
      (node (ref "MEMORY-0-8KX8-6264") (pin "9") (pinfunction "A1_9") (pintype "input"))
      (node (ref "MEMORY-1-8KX8-6264") (pin "9") (pinfunction "A1_9") (pintype "input"))
      (node (ref "MEMORY-2-8KX8-6264") (pin "9") (pinfunction "A1_9") (pintype "input"))
      (node (ref "MEMORY-3-8KX8-6264") (pin "9") (pinfunction "A1_9") (pintype "input"))
    )
    (net (code "37") (name "/ADDR-B2") (class "Default")
      (node (ref "MEM-INT-BUF-0") (pin "12") (pinfunction "B7_12") (pintype "bidirectional"))
      (node (ref "MEMORY-0-8KX8-6264") (pin "8") (pinfunction "A2_8") (pintype "input"))
      (node (ref "MEMORY-1-8KX8-6264") (pin "8") (pinfunction "A2_8") (pintype "input"))
      (node (ref "MEMORY-2-8KX8-6264") (pin "8") (pinfunction "A2_8") (pintype "input"))
      (node (ref "MEMORY-3-8KX8-6264") (pin "8") (pinfunction "A2_8") (pintype "input"))
    )
    (net (code "38") (name "/ADDR-B3") (class "Default")
      (node (ref "MEM-INT-BUF-0") (pin "11") (pinfunction "B8_11") (pintype "bidirectional"))
      (node (ref "MEMORY-0-8KX8-6264") (pin "7") (pinfunction "A3_7") (pintype "input"))
      (node (ref "MEMORY-1-8KX8-6264") (pin "7") (pinfunction "A3_7") (pintype "input"))
      (node (ref "MEMORY-2-8KX8-6264") (pin "7") (pinfunction "A3_7") (pintype "input"))
      (node (ref "MEMORY-3-8KX8-6264") (pin "7") (pinfunction "A3_7") (pintype "input"))
    )
    (net (code "39") (name "/ADDR-B4") (class "Default")
      (node (ref "MEM-INT-BUF-1") (pin "18") (pinfunction "B1_18") (pintype "bidirectional"))
      (node (ref "MEMORY-0-8KX8-6264") (pin "6") (pinfunction "A4_6") (pintype "input"))
      (node (ref "MEMORY-1-8KX8-6264") (pin "6") (pinfunction "A4_6") (pintype "input"))
      (node (ref "MEMORY-2-8KX8-6264") (pin "6") (pinfunction "A4_6") (pintype "input"))
      (node (ref "MEMORY-3-8KX8-6264") (pin "6") (pinfunction "A4_6") (pintype "input"))
    )
    (net (code "40") (name "/ADDR-B5") (class "Default")
      (node (ref "MEM-INT-BUF-1") (pin "17") (pinfunction "B2_17") (pintype "bidirectional"))
      (node (ref "MEMORY-0-8KX8-6264") (pin "5") (pinfunction "A5_5") (pintype "input"))
      (node (ref "MEMORY-1-8KX8-6264") (pin "5") (pinfunction "A5_5") (pintype "input"))
      (node (ref "MEMORY-2-8KX8-6264") (pin "5") (pinfunction "A5_5") (pintype "input"))
      (node (ref "MEMORY-3-8KX8-6264") (pin "5") (pinfunction "A5_5") (pintype "input"))
    )
    (net (code "41") (name "/ADDR-B6") (class "Default")
      (node (ref "MEM-INT-BUF-1") (pin "16") (pinfunction "B3_16") (pintype "bidirectional"))
      (node (ref "MEMORY-0-8KX8-6264") (pin "4") (pinfunction "A6_4") (pintype "input"))
      (node (ref "MEMORY-1-8KX8-6264") (pin "4") (pinfunction "A6_4") (pintype "input"))
      (node (ref "MEMORY-2-8KX8-6264") (pin "4") (pinfunction "A6_4") (pintype "input"))
      (node (ref "MEMORY-3-8KX8-6264") (pin "4") (pinfunction "A6_4") (pintype "input"))
    )
    (net (code "42") (name "/ADDR-B7") (class "Default")
      (node (ref "MEM-INT-BUF-1") (pin "15") (pinfunction "B4_15") (pintype "bidirectional"))
      (node (ref "MEMORY-0-8KX8-6264") (pin "3") (pinfunction "A7_3") (pintype "input"))
      (node (ref "MEMORY-1-8KX8-6264") (pin "3") (pinfunction "A7_3") (pintype "input"))
      (node (ref "MEMORY-2-8KX8-6264") (pin "25") (pinfunction "A8_25") (pintype "input"))
      (node (ref "MEMORY-2-8KX8-6264") (pin "3") (pinfunction "A7_3") (pintype "input"))
      (node (ref "MEMORY-3-8KX8-6264") (pin "3") (pinfunction "A7_3") (pintype "input"))
    )
    (net (code "43") (name "/ADDR-B8") (class "Default")
      (node (ref "MEM-INT-BUF-1") (pin "14") (pinfunction "B5_14") (pintype "bidirectional"))
      (node (ref "MEMORY-0-8KX8-6264") (pin "25") (pinfunction "A8_25") (pintype "input"))
      (node (ref "MEMORY-1-8KX8-6264") (pin "25") (pinfunction "A8_25") (pintype "input"))
      (node (ref "MEMORY-3-8KX8-6264") (pin "25") (pinfunction "A8_25") (pintype "input"))
    )
    (net (code "44") (name "/ADDR-B9") (class "Default")
      (node (ref "MEM-INT-BUF-1") (pin "13") (pinfunction "B6_13") (pintype "bidirectional"))
      (node (ref "MEMORY-0-8KX8-6264") (pin "24") (pinfunction "A9_24") (pintype "input"))
      (node (ref "MEMORY-1-8KX8-6264") (pin "24") (pinfunction "A9_24") (pintype "input"))
      (node (ref "MEMORY-2-8KX8-6264") (pin "24") (pinfunction "A9_24") (pintype "input"))
      (node (ref "MEMORY-3-8KX8-6264") (pin "24") (pinfunction "A9_24") (pintype "input"))
    )
    (net (code "45") (name "/ADDR-B10") (class "Default")
      (node (ref "MEM-INT-BUF-1") (pin "12") (pinfunction "B7_12") (pintype "bidirectional"))
      (node (ref "MEMORY-0-8KX8-6264") (pin "21") (pinfunction "A10_21") (pintype "input"))
      (node (ref "MEMORY-1-8KX8-6264") (pin "21") (pinfunction "A10_21") (pintype "input"))
      (node (ref "MEMORY-2-8KX8-6264") (pin "21") (pinfunction "A10_21") (pintype "input"))
      (node (ref "MEMORY-3-8KX8-6264") (pin "21") (pinfunction "A10_21") (pintype "input"))
    )
    (net (code "46") (name "/ADDR-B11") (class "Default")
      (node (ref "MEM-INT-BUF-1") (pin "11") (pinfunction "B8_11") (pintype "bidirectional"))
      (node (ref "MEMORY-0-8KX8-6264") (pin "23") (pinfunction "A11_23") (pintype "input"))
      (node (ref "MEMORY-1-8KX8-6264") (pin "23") (pinfunction "A11_23") (pintype "input"))
      (node (ref "MEMORY-2-8KX8-6264") (pin "23") (pinfunction "A11_23") (pintype "input"))
      (node (ref "MEMORY-3-8KX8-6264") (pin "23") (pinfunction "A11_23") (pintype "input"))
    )
    (net (code "47") (name "/ADDR-B12") (class "Default")
      (node (ref "MEM-INT-BUF-2") (pin "18") (pinfunction "B1_18") (pintype "bidirectional"))
      (node (ref "MEMORY-0-8KX8-6264") (pin "2") (pinfunction "A12_2") (pintype "input"))
      (node (ref "MEMORY-1-8KX8-6264") (pin "2") (pinfunction "A12_2") (pintype "input"))
      (node (ref "MEMORY-2-8KX8-6264") (pin "2") (pinfunction "A12_2") (pintype "input"))
      (node (ref "MEMORY-3-8KX8-6264") (pin "2") (pinfunction "A12_2") (pintype "input"))
    )
    (net (code "49") (name "/ADDR-EX") (class "Default")
      (node (ref "74LS161N-3") (pin "14") (pinfunction "QA_14") (pintype "output"))
    )
    (net (code "50") (name "/ADDR-PROG0") (class "Default")
      (node (ref "ADDR-R/P-SW-0") (pin "3") (pinfunction "1B_3") (pintype "input"))
      (node (ref "PROG/RUN-ADDR-SW") (pin "1") (pinfunction "1_1") (pintype "passive"))
    )
    (net (code "51") (name "/ADDR-PROG1") (class "Default")
      (node (ref "ADDR-R/P-SW-0") (pin "6") (pinfunction "2B_6") (pintype "input"))
      (node (ref "PROG/RUN-ADDR-SW") (pin "2") (pinfunction "2_2") (pintype "passive"))
    )
    (net (code "52") (name "/ADDR-PROG2") (class "Default")
      (node (ref "ADDR-R/P-SW-0") (pin "10") (pinfunction "3B_10") (pintype "input"))
      (node (ref "PROG/RUN-ADDR-SW") (pin "3") (pinfunction "3_3") (pintype "passive"))
    )
    (net (code "53") (name "/ADDR-PROG3") (class "Default")
      (node (ref "ADDR-R/P-SW-0") (pin "13") (pinfunction "4B_13") (pintype "input"))
      (node (ref "PROG/RUN-ADDR-SW") (pin "4") (pinfunction "4_4") (pintype "passive"))
    )
    (net (code "54") (name "/ADDR-PROG4") (class "Default")
      (node (ref "ADDR-R/P-SW-1") (pin "3") (pinfunction "1B_3") (pintype "input"))
      (node (ref "PROG/RUN-ADDR-SW") (pin "5") (pinfunction "5_5") (pintype "passive"))
    )
    (net (code "55") (name "/ADDR-PROG5") (class "Default")
      (node (ref "ADDR-R/P-SW-1") (pin "6") (pinfunction "2B_6") (pintype "input"))
      (node (ref "PROG/RUN-ADDR-SW") (pin "6") (pinfunction "6_6") (pintype "passive"))
    )
    (net (code "56") (name "/ADDR-PROG6") (class "Default")
      (node (ref "ADDR-R/P-SW-1") (pin "10") (pinfunction "3B_10") (pintype "input"))
      (node (ref "PROG/RUN-ADDR-SW") (pin "7") (pinfunction "7_7") (pintype "passive"))
    )
    (net (code "57") (name "/ADDR-PROG7") (class "Default")
      (node (ref "ADDR-R/P-SW-1") (pin "13") (pinfunction "4B_13") (pintype "input"))
      (node (ref "PROG/RUN-ADDR-SW") (pin "8") (pinfunction "8_8") (pintype "passive"))
    )
    (net (code "58") (name "/ADDR-PROG8") (class "Default")
      (node (ref "ADDR-R/P-SW-2") (pin "3") (pinfunction "1B_3") (pintype "input"))
      (node (ref "PROG/RUN-ADDR-SW") (pin "9") (pinfunction "9_9") (pintype "passive"))
    )
    (net (code "59") (name "/ADDR-PROG9") (class "Default")
      (node (ref "ADDR-R/P-SW-2") (pin "6") (pinfunction "2B_6") (pintype "input"))
      (node (ref "PROG/RUN-ADDR-SW") (pin "10") (pinfunction "10_10") (pintype "passive"))
    )
    (net (code "60") (name "/ADDR-PROG10") (class "Default")
      (node (ref "ADDR-R/P-SW-2") (pin "10") (pinfunction "3B_10") (pintype "input"))
      (node (ref "PROG/RUN-ADDR-SW") (pin "11") (pinfunction "11_11") (pintype "passive"))
    )
    (net (code "61") (name "/ADDR-PROG11") (class "Default")
      (node (ref "ADDR-R/P-SW-2") (pin "13") (pinfunction "4B_13") (pintype "input"))
      (node (ref "PROG/RUN-ADDR-SW") (pin "12") (pinfunction "12_12") (pintype "passive"))
    )
    (net (code "62") (name "/ADDR-PROG12") (class "Default")
      (node (ref "ADDR-R/P-SW-3") (pin "3") (pinfunction "1B_3") (pintype "input"))
      (node (ref "SW3") (pin "1") (pinfunction "1_1") (pintype "passive"))
    )
    (net (code "64") (name "/CEN-A0") (class "Default")
      (node (ref "DEMUX-2X4-0") (pin "4") (pinfunction "Y0_4") (pintype "output"))
      (node (ref "LED12") (pin "A") (pinfunction "A_A") (pintype "passive"))
      (node (ref "MEM-INT-BUF-0") (pin "2") (pinfunction "A1_2") (pintype "bidirectional"))
    )
    (net (code "65") (name "/CEN-A1") (class "Default")
      (node (ref "DEMUX-2X4-0") (pin "5") (pinfunction "Y1_5") (pintype "output"))
      (node (ref "LED13") (pin "A") (pinfunction "A_A") (pintype "passive"))
      (node (ref "MEM-INT-BUF-0") (pin "3") (pinfunction "A2_3") (pintype "bidirectional"))
    )
    (net (code "66") (name "/CEN-A2") (class "Default")
      (node (ref "DEMUX-2X4-0") (pin "6") (pinfunction "Y2_6") (pintype "output"))
      (node (ref "LED14") (pin "A") (pinfunction "A_A") (pintype "passive"))
      (node (ref "MEM-INT-BUF-0") (pin "4") (pinfunction "A3_4") (pintype "bidirectional"))
    )
    (net (code "67") (name "/CEN-A3") (class "Default")
      (node (ref "DEMUX-2X4-0") (pin "7") (pinfunction "Y3_7") (pintype "output"))
      (node (ref "LED15") (pin "A") (pinfunction "A_A") (pintype "passive"))
      (node (ref "MEM-INT-BUF-0") (pin "5") (pinfunction "A4_5") (pintype "bidirectional"))
    )
    (net (code "68") (name "/CEN-B0") (class "Default")
      (node (ref "MEM-INT-BUF-0") (pin "18") (pinfunction "B1_18") (pintype "bidirectional"))
      (node (ref "MEMORY-0-8KX8-6264") (pin "20") (pinfunction "~{CS1}_20") (pintype "input"))
    )
    (net (code "69") (name "/CEN-B1") (class "Default")
      (node (ref "MEM-INT-BUF-0") (pin "17") (pinfunction "B2_17") (pintype "bidirectional"))
      (node (ref "MEMORY-1-8KX8-6264") (pin "20") (pinfunction "~{CS1}_20") (pintype "input"))
    )
    (net (code "70") (name "/CEN-B2") (class "Default")
      (node (ref "MEM-INT-BUF-0") (pin "16") (pinfunction "B3_16") (pintype "bidirectional"))
      (node (ref "MEMORY-2-8KX8-6264") (pin "20") (pinfunction "~{CS1}_20") (pintype "input"))
    )
    (net (code "71") (name "/CEN-B3") (class "Default")
      (node (ref "MEM-INT-BUF-0") (pin "15") (pinfunction "B4_15") (pintype "bidirectional"))
      (node (ref "MEMORY-3-8KX8-6264") (pin "20") (pinfunction "~{CS1}_20") (pintype "input"))
    )
    (net (code "72") (name "/CF") (class "Default")
      (node (ref "AT28C16-0") (pin "4") (pinfunction "A4_4") (pintype "input"))
      (node (ref "AT28C16-1") (pin "4") (pinfunction "A4_4") (pintype "input"))
      (node (ref "AT28C16-2") (pin "4") (pinfunction "A4_4") (pintype "input"))
      (node (ref "AT28C16-3") (pin "4") (pinfunction "A4_4") (pintype "input"))
    )
    (net (code "73") (name "/CMD0") (class "Default")
      (node (ref "AT28C16-0") (pin "1") (pinfunction "A7_1") (pintype "input"))
      (node (ref "AT28C16-1") (pin "1") (pinfunction "A7_1") (pintype "input"))
      (node (ref "AT28C16-2") (pin "1") (pinfunction "A7_1") (pintype "input"))
      (node (ref "AT28C16-3") (pin "1") (pinfunction "A7_1") (pintype "input"))
    )
    (net (code "74") (name "/CMD1") (class "Default")
      (node (ref "AT28C16-0") (pin "23") (pinfunction "A8_23") (pintype "input"))
      (node (ref "AT28C16-1") (pin "23") (pinfunction "A8_23") (pintype "input"))
      (node (ref "AT28C16-2") (pin "23") (pinfunction "A8_23") (pintype "input"))
      (node (ref "AT28C16-3") (pin "23") (pinfunction "A8_23") (pintype "input"))
    )
    (net (code "75") (name "/CMD2") (class "Default")
      (node (ref "AT28C16-0") (pin "22") (pinfunction "A9_22") (pintype "input"))
      (node (ref "AT28C16-1") (pin "22") (pinfunction "A9_22") (pintype "input"))
      (node (ref "AT28C16-2") (pin "22") (pinfunction "A9_22") (pintype "input"))
      (node (ref "AT28C16-3") (pin "22") (pinfunction "A9_22") (pintype "input"))
    )
    (net (code "76") (name "/CMD3") (class "Default")
      (node (ref "AT28C16-0") (pin "19") (pinfunction "A10_19") (pintype "input"))
      (node (ref "AT28C16-1") (pin "19") (pinfunction "A10_19") (pintype "input"))
      (node (ref "AT28C16-2") (pin "19") (pinfunction "A10_19") (pintype "input"))
      (node (ref "AT28C16-3") (pin "19") (pinfunction "A10_19") (pintype "input"))
    )
    (net (code "77") (name "/DATA-B0") (class "Default")
      (node (ref "LED25") (pin "A") (pinfunction "A_A") (pintype "passive"))
      (node (ref "MEM-BUF") (pin "2") (pinfunction "A1_2") (pintype "bidirectional"))
      (node (ref "MEMORY-0-8KX8-6264") (pin "11") (pinfunction "I/O1_11") (pintype "bidirectional"))
      (node (ref "MEMORY-1-8KX8-6264") (pin "11") (pinfunction "I/O1_11") (pintype "bidirectional"))
      (node (ref "MEMORY-2-8KX8-6264") (pin "11") (pinfunction "I/O1_11") (pintype "bidirectional"))
      (node (ref "MEMORY-3-8KX8-6264") (pin "11") (pinfunction "I/O1_11") (pintype "bidirectional"))
    )
    (net (code "78") (name "/DATA-B1") (class "Default")
      (node (ref "LED24") (pin "A") (pinfunction "A_A") (pintype "passive"))
      (node (ref "MEM-BUF") (pin "3") (pinfunction "A2_3") (pintype "bidirectional"))
      (node (ref "MEMORY-0-8KX8-6264") (pin "12") (pinfunction "I/O2_12") (pintype "bidirectional"))
      (node (ref "MEMORY-1-8KX8-6264") (pin "12") (pinfunction "I/O2_12") (pintype "bidirectional"))
      (node (ref "MEMORY-2-8KX8-6264") (pin "12") (pinfunction "I/O2_12") (pintype "bidirectional"))
      (node (ref "MEMORY-3-8KX8-6264") (pin "12") (pinfunction "I/O2_12") (pintype "bidirectional"))
    )
    (net (code "79") (name "/DATA-B2") (class "Default")
      (node (ref "LED23") (pin "A") (pinfunction "A_A") (pintype "passive"))
      (node (ref "MEM-BUF") (pin "4") (pinfunction "A3_4") (pintype "bidirectional"))
      (node (ref "MEMORY-0-8KX8-6264") (pin "13") (pinfunction "I/O3_13") (pintype "bidirectional"))
      (node (ref "MEMORY-1-8KX8-6264") (pin "13") (pinfunction "I/O3_13") (pintype "bidirectional"))
      (node (ref "MEMORY-2-8KX8-6264") (pin "13") (pinfunction "I/O3_13") (pintype "bidirectional"))
      (node (ref "MEMORY-3-8KX8-6264") (pin "13") (pinfunction "I/O3_13") (pintype "bidirectional"))
    )
    (net (code "80") (name "/DATA-B3") (class "Default")
      (node (ref "LED22") (pin "A") (pinfunction "A_A") (pintype "passive"))
      (node (ref "MEM-BUF") (pin "5") (pinfunction "A4_5") (pintype "bidirectional"))
      (node (ref "MEMORY-0-8KX8-6264") (pin "15") (pinfunction "I/O4_15") (pintype "bidirectional"))
      (node (ref "MEMORY-1-8KX8-6264") (pin "15") (pinfunction "I/O4_15") (pintype "bidirectional"))
      (node (ref "MEMORY-2-8KX8-6264") (pin "15") (pinfunction "I/O4_15") (pintype "bidirectional"))
      (node (ref "MEMORY-3-8KX8-6264") (pin "15") (pinfunction "I/O4_15") (pintype "bidirectional"))
    )
    (net (code "81") (name "/DATA-B4") (class "Default")
      (node (ref "LED21") (pin "A") (pinfunction "A_A") (pintype "passive"))
      (node (ref "MEM-BUF") (pin "6") (pinfunction "A5_6") (pintype "bidirectional"))
      (node (ref "MEMORY-0-8KX8-6264") (pin "16") (pinfunction "I/O5_16") (pintype "bidirectional"))
      (node (ref "MEMORY-1-8KX8-6264") (pin "16") (pinfunction "I/O5_16") (pintype "bidirectional"))
      (node (ref "MEMORY-2-8KX8-6264") (pin "16") (pinfunction "I/O5_16") (pintype "bidirectional"))
      (node (ref "MEMORY-3-8KX8-6264") (pin "16") (pinfunction "I/O5_16") (pintype "bidirectional"))
    )
    (net (code "82") (name "/DATA-B5") (class "Default")
      (node (ref "LED20") (pin "A") (pinfunction "A_A") (pintype "passive"))
      (node (ref "MEM-BUF") (pin "7") (pinfunction "A6_7") (pintype "bidirectional"))
      (node (ref "MEMORY-0-8KX8-6264") (pin "17") (pinfunction "I/O6_17") (pintype "bidirectional"))
      (node (ref "MEMORY-1-8KX8-6264") (pin "17") (pinfunction "I/O6_17") (pintype "bidirectional"))
      (node (ref "MEMORY-2-8KX8-6264") (pin "17") (pinfunction "I/O6_17") (pintype "bidirectional"))
      (node (ref "MEMORY-3-8KX8-6264") (pin "17") (pinfunction "I/O6_17") (pintype "bidirectional"))
    )
    (net (code "83") (name "/DATA-B6") (class "Default")
      (node (ref "LED19") (pin "A") (pinfunction "A_A") (pintype "passive"))
      (node (ref "MEM-BUF") (pin "8") (pinfunction "A7_8") (pintype "bidirectional"))
      (node (ref "MEMORY-0-8KX8-6264") (pin "18") (pinfunction "I/O7_18") (pintype "bidirectional"))
      (node (ref "MEMORY-1-8KX8-6264") (pin "18") (pinfunction "I/O7_18") (pintype "bidirectional"))
      (node (ref "MEMORY-2-8KX8-6264") (pin "18") (pinfunction "I/O7_18") (pintype "bidirectional"))
      (node (ref "MEMORY-3-8KX8-6264") (pin "18") (pinfunction "I/O7_18") (pintype "bidirectional"))
    )
    (net (code "84") (name "/DATA-B7") (class "Default")
      (node (ref "LED18") (pin "A") (pinfunction "A_A") (pintype "passive"))
      (node (ref "MEM-BUF") (pin "9") (pinfunction "A8_9") (pintype "bidirectional"))
      (node (ref "MEMORY-0-8KX8-6264") (pin "19") (pinfunction "I/O8_19") (pintype "bidirectional"))
      (node (ref "MEMORY-1-8KX8-6264") (pin "19") (pinfunction "I/O8_19") (pintype "bidirectional"))
      (node (ref "MEMORY-2-8KX8-6264") (pin "19") (pinfunction "I/O8_19") (pintype "bidirectional"))
      (node (ref "MEMORY-3-8KX8-6264") (pin "19") (pinfunction "I/O8_19") (pintype "bidirectional"))
    )
    (net (code "87") (name "/DATA-PROG0") (class "Default")
      (node (ref "DATA-R/P-SW-0") (pin "3") (pinfunction "1B_3") (pintype "input"))
      (node (ref "PROG/RUN-DATA-SW") (pin "1") (pinfunction "1_1") (pintype "passive"))
    )
    (net (code "88") (name "/DATA-PROG1") (class "Default")
      (node (ref "DATA-R/P-SW-0") (pin "6") (pinfunction "2B_6") (pintype "input"))
      (node (ref "PROG/RUN-DATA-SW") (pin "2") (pinfunction "2_2") (pintype "passive"))
    )
    (net (code "89") (name "/DATA-PROG2") (class "Default")
      (node (ref "DATA-R/P-SW-0") (pin "10") (pinfunction "3B_10") (pintype "input"))
      (node (ref "PROG/RUN-DATA-SW") (pin "3") (pinfunction "3_3") (pintype "passive"))
    )
    (net (code "90") (name "/DATA-PROG3") (class "Default")
      (node (ref "DATA-R/P-SW-0") (pin "13") (pinfunction "4B_13") (pintype "input"))
      (node (ref "PROG/RUN-DATA-SW") (pin "4") (pinfunction "4_4") (pintype "passive"))
    )
    (net (code "91") (name "/DATA-PROG4") (class "Default")
      (node (ref "DATA-R/P-SW-1") (pin "3") (pinfunction "1B_3") (pintype "input"))
      (node (ref "PROG/RUN-DATA-SW") (pin "5") (pinfunction "5_5") (pintype "passive"))
    )
    (net (code "92") (name "/DATA-PROG5") (class "Default")
      (node (ref "DATA-R/P-SW-1") (pin "6") (pinfunction "2B_6") (pintype "input"))
      (node (ref "PROG/RUN-DATA-SW") (pin "6") (pinfunction "6_6") (pintype "passive"))
    )
    (net (code "93") (name "/DATA-PROG6") (class "Default")
      (node (ref "DATA-R/P-SW-1") (pin "10") (pinfunction "3B_10") (pintype "input"))
      (node (ref "PROG/RUN-DATA-SW") (pin "7") (pinfunction "7_7") (pintype "passive"))
    )
    (net (code "94") (name "/DATA-PROG7") (class "Default")
      (node (ref "DATA-R/P-SW-1") (pin "13") (pinfunction "4B_13") (pintype "input"))
      (node (ref "PROG/RUN-DATA-SW") (pin "8") (pinfunction "8_8") (pintype "passive"))
    )
    (net (code "97") (name "/DISP-DATA-OUT0") (class "Default")
      (node (ref "EEPROM-AT28C16") (pin "9") (pinfunction "D0_9") (pintype "bidirectional"))
      (node (ref "SEG-DISP0") (pin "7") (pinfunction "A_7") (pintype "passive"))
      (node (ref "SEG-DISP1") (pin "7") (pinfunction "A_7") (pintype "passive"))
      (node (ref "SEG-DISP2") (pin "7") (pinfunction "A_7") (pintype "passive"))
      (node (ref "SEG-DISP3") (pin "7") (pinfunction "A_7") (pintype "passive"))
    )
    (net (code "98") (name "/DISP-DATA-OUT1") (class "Default")
      (node (ref "EEPROM-AT28C16") (pin "10") (pinfunction "D1_10") (pintype "bidirectional"))
      (node (ref "SEG-DISP0") (pin "6") (pinfunction "B_6") (pintype "passive"))
      (node (ref "SEG-DISP1") (pin "6") (pinfunction "B_6") (pintype "passive"))
      (node (ref "SEG-DISP2") (pin "6") (pinfunction "B_6") (pintype "passive"))
      (node (ref "SEG-DISP3") (pin "6") (pinfunction "B_6") (pintype "passive"))
    )
    (net (code "99") (name "/DISP-DATA-OUT2") (class "Default")
      (node (ref "EEPROM-AT28C16") (pin "11") (pinfunction "D2_11") (pintype "bidirectional"))
      (node (ref "SEG-DISP0") (pin "4") (pinfunction "C_4") (pintype "passive"))
      (node (ref "SEG-DISP1") (pin "4") (pinfunction "C_4") (pintype "passive"))
      (node (ref "SEG-DISP2") (pin "4") (pinfunction "C_4") (pintype "passive"))
      (node (ref "SEG-DISP3") (pin "4") (pinfunction "C_4") (pintype "passive"))
    )
    (net (code "100") (name "/DISP-DATA-OUT3") (class "Default")
      (node (ref "EEPROM-AT28C16") (pin "13") (pinfunction "D3_13") (pintype "bidirectional"))
      (node (ref "SEG-DISP0") (pin "2") (pinfunction "D_2") (pintype "passive"))
      (node (ref "SEG-DISP1") (pin "2") (pinfunction "D_2") (pintype "passive"))
      (node (ref "SEG-DISP2") (pin "2") (pinfunction "D_2") (pintype "passive"))
      (node (ref "SEG-DISP3") (pin "2") (pinfunction "D_2") (pintype "passive"))
    )
    (net (code "101") (name "/DISP-DATA-OUT4") (class "Default")
      (node (ref "EEPROM-AT28C16") (pin "14") (pinfunction "D4_14") (pintype "bidirectional"))
      (node (ref "SEG-DISP0") (pin "1") (pinfunction "E_1") (pintype "passive"))
      (node (ref "SEG-DISP1") (pin "1") (pinfunction "E_1") (pintype "passive"))
      (node (ref "SEG-DISP2") (pin "1") (pinfunction "E_1") (pintype "passive"))
      (node (ref "SEG-DISP3") (pin "1") (pinfunction "E_1") (pintype "passive"))
    )
    (net (code "102") (name "/DISP-DATA-OUT5") (class "Default")
      (node (ref "EEPROM-AT28C16") (pin "15") (pinfunction "D5_15") (pintype "bidirectional"))
      (node (ref "SEG-DISP0") (pin "9") (pinfunction "F_9") (pintype "passive"))
      (node (ref "SEG-DISP1") (pin "9") (pinfunction "F_9") (pintype "passive"))
      (node (ref "SEG-DISP2") (pin "9") (pinfunction "F_9") (pintype "passive"))
      (node (ref "SEG-DISP3") (pin "9") (pinfunction "F_9") (pintype "passive"))
    )
    (net (code "103") (name "/DISP-DATA-OUT6") (class "Default")
      (node (ref "EEPROM-AT28C16") (pin "16") (pinfunction "D6_16") (pintype "bidirectional"))
      (node (ref "SEG-DISP0") (pin "10") (pinfunction "G_10") (pintype "passive"))
      (node (ref "SEG-DISP1") (pin "10") (pinfunction "G_10") (pintype "passive"))
      (node (ref "SEG-DISP2") (pin "10") (pinfunction "G_10") (pintype "passive"))
      (node (ref "SEG-DISP3") (pin "10") (pinfunction "G_10") (pintype "passive"))
    )
    (net (code "104") (name "/DISP-DATA-OUT7") (class "Default")
      (node (ref "EEPROM-AT28C16") (pin "17") (pinfunction "D7_17") (pintype "bidirectional"))
      (node (ref "SEG-DISP0") (pin "5") (pinfunction "DP_5") (pintype "passive"))
      (node (ref "SEG-DISP1") (pin "5") (pinfunction "DP_5") (pintype "passive"))
      (node (ref "SEG-DISP2") (pin "5") (pinfunction "DP_5") (pintype "passive"))
      (node (ref "SEG-DISP3") (pin "5") (pinfunction "DP_5") (pintype "passive"))
    )
    (net (code "105") (name "/DISP-EN0") (class "Default")
      (node (ref "IC12") (pin "4") (pinfunction "Y0_4") (pintype "output"))
      (node (ref "SEG-DISP0") (pin "3") (pinfunction "CK1_3") (pintype "passive"))
      (node (ref "SEG-DISP0") (pin "8") (pinfunction "CK2_8") (pintype "passive"))
    )
    (net (code "106") (name "/DISP-EN1") (class "Default")
      (node (ref "IC12") (pin "5") (pinfunction "Y1_5") (pintype "output"))
      (node (ref "SEG-DISP1") (pin "3") (pinfunction "CK1_3") (pintype "passive"))
      (node (ref "SEG-DISP1") (pin "8") (pinfunction "CK2_8") (pintype "passive"))
    )
    (net (code "107") (name "/DISP-EN2") (class "Default")
      (node (ref "IC12") (pin "6") (pinfunction "Y2_6") (pintype "output"))
      (node (ref "SEG-DISP2") (pin "3") (pinfunction "CK1_3") (pintype "passive"))
      (node (ref "SEG-DISP2") (pin "8") (pinfunction "CK2_8") (pintype "passive"))
    )
    (net (code "108") (name "/DISP-EN3") (class "Default")
      (node (ref "IC12") (pin "7") (pinfunction "Y3_7") (pintype "output"))
      (node (ref "SEG-DISP3") (pin "3") (pinfunction "CK1_3") (pintype "passive"))
      (node (ref "SEG-DISP3") (pin "8") (pinfunction "CK2_8") (pintype "passive"))
    )
    (net (code "110") (name "/MUX0-1C0") (class "Default")
      (node (ref "4BIT-FULL-ADDER-2") (pin "4") (pinfunction "S1_4") (pintype "output"))
      (node (ref "DUAL-4X1-MUX-0") (pin "6") (pinfunction "1C0_6") (pintype "input"))
    )
    (net (code "111") (name "/MUX0-1C1") (class "Default")
      (node (ref "DUAL-4X1-MUX-0") (pin "5") (pinfunction "1C1_5") (pintype "input"))
      (node (ref "IC35") (pin "11") (pinfunction "O_11") (pintype "output"))
    )
    (net (code "112") (name "/MUX0-1C2") (class "Default")
      (node (ref "DUAL-4X1-MUX-0") (pin "4") (pinfunction "1C2_4") (pintype "input"))
      (node (ref "IC1") (pin "2") (pinfunction "O_2") (pintype "output"))
    )
    (net (code "113") (name "/MUX0-1C3") (class "Default")
      (node (ref "DUAL-4X1-MUX-0") (pin "3") (pinfunction "1C3_3") (pintype "input"))
      (node (ref "IC37") (pin "11") (pinfunction "O_11") (pintype "output"))
    )
    (net (code "114") (name "/MUX0-2C0") (class "Default")
      (node (ref "4BIT-FULL-ADDER-2") (pin "1") (pinfunction "S2_1") (pintype "output"))
      (node (ref "DUAL-4X1-MUX-0") (pin "10") (pinfunction "2C0_10") (pintype "input"))
    )
    (net (code "115") (name "/MUX0-2C1") (class "Default")
      (node (ref "DUAL-4X1-MUX-0") (pin "11") (pinfunction "2C1_11") (pintype "input"))
      (node (ref "IC39") (pin "3") (pinfunction "O_3") (pintype "output"))
    )
    (net (code "116") (name "/MUX0-2C2") (class "Default")
      (node (ref "DUAL-4X1-MUX-0") (pin "12") (pinfunction "2C2_12") (pintype "input"))
      (node (ref "IC2") (pin "2") (pinfunction "O_2") (pintype "output"))
    )
    (net (code "117") (name "/MUX0-2C3") (class "Default")
      (node (ref "DUAL-4X1-MUX-0") (pin "13") (pinfunction "2C3_13") (pintype "input"))
      (node (ref "IC38") (pin "3") (pinfunction "O_3") (pintype "output"))
    )
    (net (code "118") (name "/MUX1-1C0") (class "Default")
      (node (ref "4BIT-FULL-ADDER-2") (pin "13") (pinfunction "S3_13") (pintype "output"))
      (node (ref "DUAL-4X1-MUX-1") (pin "6") (pinfunction "1C0_6") (pintype "input"))
    )
    (net (code "119") (name "/MUX1-1C1") (class "Default")
      (node (ref "DUAL-4X1-MUX-1") (pin "5") (pinfunction "1C1_5") (pintype "input"))
      (node (ref "IC42") (pin "11") (pinfunction "O_11") (pintype "output"))
    )
    (net (code "120") (name "/MUX1-1C2") (class "Default")
      (node (ref "DUAL-4X1-MUX-1") (pin "4") (pinfunction "1C2_4") (pintype "input"))
      (node (ref "IC3") (pin "2") (pinfunction "O_2") (pintype "output"))
    )
    (net (code "121") (name "/MUX1-1C3") (class "Default")
      (node (ref "DUAL-4X1-MUX-1") (pin "3") (pinfunction "1C3_3") (pintype "input"))
      (node (ref "IC41") (pin "11") (pinfunction "O_11") (pintype "output"))
    )
    (net (code "122") (name "/MUX1-2C0") (class "Default")
      (node (ref "4BIT-FULL-ADDER-2") (pin "10") (pinfunction "S4_10") (pintype "output"))
      (node (ref "DUAL-4X1-MUX-1") (pin "10") (pinfunction "2C0_10") (pintype "input"))
    )
    (net (code "123") (name "/MUX1-2C1") (class "Default")
      (node (ref "DUAL-4X1-MUX-1") (pin "11") (pinfunction "2C1_11") (pintype "input"))
    )
    (net (code "124") (name "/MUX1-2C2") (class "Default")
      (node (ref "DUAL-4X1-MUX-1") (pin "12") (pinfunction "2C2_12") (pintype "input"))
    )
    (net (code "125") (name "/MUX1-2C3") (class "Default")
      (node (ref "DUAL-4X1-MUX-1") (pin "13") (pinfunction "2C3_13") (pintype "input"))
    )
    (net (code "126") (name "/MUX2-1C0") (class "Default")
      (node (ref "4BIT-FULL-ADDER-3") (pin "4") (pinfunction "S1_4") (pintype "output"))
      (node (ref "DUAL-4X1-MUX-2") (pin "6") (pinfunction "1C0_6") (pintype "input"))
    )
    (net (code "127") (name "/MUX2-1C1") (class "Default")
      (node (ref "DUAL-4X1-MUX-2") (pin "5") (pinfunction "1C1_5") (pintype "input"))
      (node (ref "IC48") (pin "11") (pinfunction "O_11") (pintype "output"))
    )
    (net (code "128") (name "/MUX2-1C2") (class "Default")
      (node (ref "DUAL-4X1-MUX-2") (pin "4") (pinfunction "1C2_4") (pintype "input"))
      (node (ref "IC5") (pin "2") (pinfunction "O_2") (pintype "output"))
    )
    (net (code "129") (name "/MUX2-1C3") (class "Default")
      (node (ref "DUAL-4X1-MUX-2") (pin "3") (pinfunction "1C3_3") (pintype "input"))
      (node (ref "IC50") (pin "11") (pinfunction "O_11") (pintype "output"))
    )
    (net (code "130") (name "/MUX2-2C0") (class "Default")
      (node (ref "4BIT-FULL-ADDER-3") (pin "1") (pinfunction "S2_1") (pintype "output"))
      (node (ref "DUAL-4X1-MUX-2") (pin "10") (pinfunction "2C0_10") (pintype "input"))
    )
    (net (code "131") (name "/MUX2-2C1") (class "Default")
      (node (ref "DUAL-4X1-MUX-2") (pin "11") (pinfunction "2C1_11") (pintype "input"))
      (node (ref "IC52") (pin "3") (pinfunction "O_3") (pintype "output"))
    )
    (net (code "132") (name "/MUX2-2C2") (class "Default")
      (node (ref "DUAL-4X1-MUX-2") (pin "12") (pinfunction "2C2_12") (pintype "input"))
      (node (ref "IC6") (pin "2") (pinfunction "O_2") (pintype "output"))
    )
    (net (code "133") (name "/MUX2-2C3") (class "Default")
      (node (ref "DUAL-4X1-MUX-2") (pin "13") (pinfunction "2C3_13") (pintype "input"))
      (node (ref "IC51") (pin "3") (pinfunction "O_3") (pintype "output"))
    )
    (net (code "134") (name "/MUX3-1C0") (class "Default")
      (node (ref "4BIT-FULL-ADDER-3") (pin "13") (pinfunction "S3_13") (pintype "output"))
      (node (ref "DUAL-4X1-MUX-3") (pin "6") (pinfunction "1C0_6") (pintype "input"))
    )
    (net (code "135") (name "/MUX3-1C1") (class "Default")
      (node (ref "DUAL-4X1-MUX-3") (pin "5") (pinfunction "1C1_5") (pintype "input"))
      (node (ref "IC55") (pin "11") (pinfunction "O_11") (pintype "output"))
    )
    (net (code "136") (name "/MUX3-1C2") (class "Default")
      (node (ref "DUAL-4X1-MUX-3") (pin "4") (pinfunction "1C2_4") (pintype "input"))
      (node (ref "IC7") (pin "2") (pinfunction "O_2") (pintype "output"))
    )
    (net (code "137") (name "/MUX3-1C3") (class "Default")
      (node (ref "DUAL-4X1-MUX-3") (pin "3") (pinfunction "1C3_3") (pintype "input"))
      (node (ref "IC54") (pin "11") (pinfunction "O_11") (pintype "output"))
    )
    (net (code "138") (name "/MUX3-2C0") (class "Default")
      (node (ref "4BIT-FULL-ADDER-3") (pin "10") (pinfunction "S4_10") (pintype "output"))
      (node (ref "DUAL-4X1-MUX-3") (pin "10") (pinfunction "2C0_10") (pintype "input"))
    )
    (net (code "139") (name "/MUX3-2C1") (class "Default")
      (node (ref "DUAL-4X1-MUX-3") (pin "11") (pinfunction "2C1_11") (pintype "input"))
      (node (ref "IC58") (pin "3") (pinfunction "O_3") (pintype "output"))
    )
    (net (code "140") (name "/MUX3-2C2") (class "Default")
      (node (ref "DUAL-4X1-MUX-3") (pin "12") (pinfunction "2C2_12") (pintype "input"))
      (node (ref "IC8") (pin "2") (pinfunction "O_2") (pintype "output"))
    )
    (net (code "141") (name "/MUX3-2C3") (class "Default")
      (node (ref "DUAL-4X1-MUX-3") (pin "13") (pinfunction "2C3_13") (pintype "input"))
      (node (ref "IC57") (pin "3") (pinfunction "O_3") (pintype "output"))
    )
    (net (code "143") (name "/REG-IO0-DATA0") (class "Default")
      (node (ref "LED58") (pin "A") (pinfunction "A_A") (pintype "passive"))
      (node (ref "REG-IO0-BUF") (pin "2") (pinfunction "A1_2") (pintype "bidirectional"))
      (node (ref "REG-IO0-L") (pin "3") (pinfunction "Q1_3") (pintype "tri_state"))
    )
    (net (code "144") (name "/REG-IO0-DATA1") (class "Default")
      (node (ref "LED59") (pin "A") (pinfunction "A_A") (pintype "passive"))
      (node (ref "REG-IO0-BUF") (pin "3") (pinfunction "A2_3") (pintype "bidirectional"))
      (node (ref "REG-IO0-L") (pin "4") (pinfunction "Q2_4") (pintype "tri_state"))
    )
    (net (code "145") (name "/REG-IO0-DATA2") (class "Default")
      (node (ref "LED60") (pin "A") (pinfunction "A_A") (pintype "passive"))
      (node (ref "REG-IO0-BUF") (pin "4") (pinfunction "A3_4") (pintype "bidirectional"))
      (node (ref "REG-IO0-L") (pin "5") (pinfunction "Q3_5") (pintype "tri_state"))
    )
    (net (code "146") (name "/REG-IO0-DATA3") (class "Default")
      (node (ref "LED61") (pin "A") (pinfunction "A_A") (pintype "passive"))
      (node (ref "REG-IO0-BUF") (pin "5") (pinfunction "A4_5") (pintype "bidirectional"))
      (node (ref "REG-IO0-L") (pin "6") (pinfunction "Q4_6") (pintype "tri_state"))
    )
    (net (code "147") (name "/REG-IO0-DATA4") (class "Default")
      (node (ref "LED62") (pin "A") (pinfunction "A_A") (pintype "passive"))
      (node (ref "REG-IO0-BUF") (pin "6") (pinfunction "A5_6") (pintype "bidirectional"))
      (node (ref "REG-IO0-H") (pin "3") (pinfunction "Q1_3") (pintype "tri_state"))
    )
    (net (code "148") (name "/REG-IO0-DATA5") (class "Default")
      (node (ref "LED63") (pin "A") (pinfunction "A_A") (pintype "passive"))
      (node (ref "REG-IO0-BUF") (pin "7") (pinfunction "A6_7") (pintype "bidirectional"))
      (node (ref "REG-IO0-H") (pin "4") (pinfunction "Q2_4") (pintype "tri_state"))
    )
    (net (code "149") (name "/REG-IO0-DATA6") (class "Default")
      (node (ref "LED64") (pin "A") (pinfunction "A_A") (pintype "passive"))
      (node (ref "REG-IO0-BUF") (pin "8") (pinfunction "A7_8") (pintype "bidirectional"))
      (node (ref "REG-IO0-H") (pin "5") (pinfunction "Q3_5") (pintype "tri_state"))
    )
    (net (code "150") (name "/REG-IO0-DATA7") (class "Default")
      (node (ref "LED65") (pin "A") (pinfunction "A_A") (pintype "passive"))
      (node (ref "REG-IO0-BUF") (pin "9") (pinfunction "A8_9") (pintype "bidirectional"))
      (node (ref "REG-IO0-H") (pin "6") (pinfunction "Q4_6") (pintype "tri_state"))
    )
    (net (code "152") (name "/REG-IO1-DATA0") (class "Default")
      (node (ref "LED66") (pin "A") (pinfunction "A_A") (pintype "passive"))
      (node (ref "REG-IO1-BUF") (pin "2") (pinfunction "A1_2") (pintype "bidirectional"))
      (node (ref "REG-IO1-L") (pin "3") (pinfunction "Q1_3") (pintype "tri_state"))
    )
    (net (code "153") (name "/REG-IO1-DATA1") (class "Default")
      (node (ref "LED67") (pin "A") (pinfunction "A_A") (pintype "passive"))
      (node (ref "REG-IO1-BUF") (pin "3") (pinfunction "A2_3") (pintype "bidirectional"))
      (node (ref "REG-IO1-L") (pin "4") (pinfunction "Q2_4") (pintype "tri_state"))
    )
    (net (code "154") (name "/REG-IO1-DATA2") (class "Default")
      (node (ref "LED68") (pin "A") (pinfunction "A_A") (pintype "passive"))
      (node (ref "REG-IO1-BUF") (pin "4") (pinfunction "A3_4") (pintype "bidirectional"))
      (node (ref "REG-IO1-L") (pin "5") (pinfunction "Q3_5") (pintype "tri_state"))
    )
    (net (code "155") (name "/REG-IO1-DATA3") (class "Default")
      (node (ref "LED69") (pin "A") (pinfunction "A_A") (pintype "passive"))
      (node (ref "REG-IO1-BUF") (pin "5") (pinfunction "A4_5") (pintype "bidirectional"))
      (node (ref "REG-IO1-L") (pin "6") (pinfunction "Q4_6") (pintype "tri_state"))
    )
    (net (code "156") (name "/REG-IO1-DATA4") (class "Default")
      (node (ref "LED70") (pin "A") (pinfunction "A_A") (pintype "passive"))
      (node (ref "REG-IO1-BUF") (pin "6") (pinfunction "A5_6") (pintype "bidirectional"))
      (node (ref "REG-IO1-H") (pin "3") (pinfunction "Q1_3") (pintype "tri_state"))
    )
    (net (code "157") (name "/REG-IO1-DATA5") (class "Default")
      (node (ref "LED71") (pin "A") (pinfunction "A_A") (pintype "passive"))
      (node (ref "REG-IO1-BUF") (pin "7") (pinfunction "A6_7") (pintype "bidirectional"))
      (node (ref "REG-IO1-H") (pin "4") (pinfunction "Q2_4") (pintype "tri_state"))
    )
    (net (code "158") (name "/REG-IO1-DATA6") (class "Default")
      (node (ref "LED72") (pin "A") (pinfunction "A_A") (pintype "passive"))
      (node (ref "REG-IO1-BUF") (pin "8") (pinfunction "A7_8") (pintype "bidirectional"))
      (node (ref "REG-IO1-H") (pin "5") (pinfunction "Q3_5") (pintype "tri_state"))
    )
    (net (code "159") (name "/REG-IO1-DATA7") (class "Default")
      (node (ref "LED73") (pin "A") (pinfunction "A_A") (pintype "passive"))
      (node (ref "REG-IO1-BUF") (pin "9") (pinfunction "A8_9") (pintype "bidirectional"))
      (node (ref "REG-IO1-H") (pin "6") (pinfunction "Q4_6") (pintype "tri_state"))
    )
    (net (code "161") (name "/REG-IO2-DATA0") (class "Default")
      (node (ref "LED74") (pin "A") (pinfunction "A_A") (pintype "passive"))
      (node (ref "REG-IO2-BUF") (pin "2") (pinfunction "A1_2") (pintype "bidirectional"))
      (node (ref "REG-IO2-L") (pin "3") (pinfunction "Q1_3") (pintype "tri_state"))
    )
    (net (code "162") (name "/REG-IO2-DATA1") (class "Default")
      (node (ref "LED75") (pin "A") (pinfunction "A_A") (pintype "passive"))
      (node (ref "REG-IO2-BUF") (pin "3") (pinfunction "A2_3") (pintype "bidirectional"))
      (node (ref "REG-IO2-L") (pin "4") (pinfunction "Q2_4") (pintype "tri_state"))
    )
    (net (code "163") (name "/REG-IO2-DATA2") (class "Default")
      (node (ref "LED76") (pin "A") (pinfunction "A_A") (pintype "passive"))
      (node (ref "REG-IO2-BUF") (pin "4") (pinfunction "A3_4") (pintype "bidirectional"))
      (node (ref "REG-IO2-L") (pin "5") (pinfunction "Q3_5") (pintype "tri_state"))
    )
    (net (code "164") (name "/REG-IO2-DATA3") (class "Default")
      (node (ref "LED77") (pin "A") (pinfunction "A_A") (pintype "passive"))
      (node (ref "REG-IO2-BUF") (pin "5") (pinfunction "A4_5") (pintype "bidirectional"))
      (node (ref "REG-IO2-L") (pin "6") (pinfunction "Q4_6") (pintype "tri_state"))
    )
    (net (code "165") (name "/REG-IO2-DATA4") (class "Default")
      (node (ref "LED78") (pin "A") (pinfunction "A_A") (pintype "passive"))
      (node (ref "REG-IO2-BUF") (pin "6") (pinfunction "A5_6") (pintype "bidirectional"))
      (node (ref "REG-IO2-H") (pin "3") (pinfunction "Q1_3") (pintype "tri_state"))
    )
    (net (code "166") (name "/REG-IO2-DATA5") (class "Default")
      (node (ref "LED79") (pin "A") (pinfunction "A_A") (pintype "passive"))
      (node (ref "REG-IO2-BUF") (pin "7") (pinfunction "A6_7") (pintype "bidirectional"))
      (node (ref "REG-IO2-H") (pin "4") (pinfunction "Q2_4") (pintype "tri_state"))
    )
    (net (code "167") (name "/REG-IO2-DATA6") (class "Default")
      (node (ref "LED80") (pin "A") (pinfunction "A_A") (pintype "passive"))
      (node (ref "REG-IO2-BUF") (pin "8") (pinfunction "A7_8") (pintype "bidirectional"))
      (node (ref "REG-IO2-H") (pin "5") (pinfunction "Q3_5") (pintype "tri_state"))
    )
    (net (code "168") (name "/REG-IO2-DATA7") (class "Default")
      (node (ref "LED81") (pin "A") (pinfunction "A_A") (pintype "passive"))
      (node (ref "REG-IO2-BUF") (pin "9") (pinfunction "A8_9") (pintype "bidirectional"))
      (node (ref "REG-IO2-H") (pin "6") (pinfunction "Q4_6") (pintype "tri_state"))
    )
    (net (code "170") (name "/REG-IO3-DATA0") (class "Default")
      (node (ref "LED82") (pin "A") (pinfunction "A_A") (pintype "passive"))
      (node (ref "REG-IO3-BUF") (pin "2") (pinfunction "A1_2") (pintype "bidirectional"))
      (node (ref "REG-IO3-L") (pin "3") (pinfunction "Q1_3") (pintype "tri_state"))
    )
    (net (code "171") (name "/REG-IO3-DATA1") (class "Default")
      (node (ref "LED83") (pin "A") (pinfunction "A_A") (pintype "passive"))
      (node (ref "REG-IO3-BUF") (pin "3") (pinfunction "A2_3") (pintype "bidirectional"))
      (node (ref "REG-IO3-L") (pin "4") (pinfunction "Q2_4") (pintype "tri_state"))
    )
    (net (code "172") (name "/REG-IO3-DATA2") (class "Default")
      (node (ref "LED84") (pin "A") (pinfunction "A_A") (pintype "passive"))
      (node (ref "REG-IO3-BUF") (pin "4") (pinfunction "A3_4") (pintype "bidirectional"))
      (node (ref "REG-IO3-L") (pin "5") (pinfunction "Q3_5") (pintype "tri_state"))
    )
    (net (code "173") (name "/REG-IO3-DATA3") (class "Default")
      (node (ref "LED85") (pin "A") (pinfunction "A_A") (pintype "passive"))
      (node (ref "REG-IO3-BUF") (pin "5") (pinfunction "A4_5") (pintype "bidirectional"))
      (node (ref "REG-IO3-L") (pin "6") (pinfunction "Q4_6") (pintype "tri_state"))
    )
    (net (code "174") (name "/REG-IO3-DATA4") (class "Default")
      (node (ref "LED86") (pin "A") (pinfunction "A_A") (pintype "passive"))
      (node (ref "REG-IO3-BUF") (pin "6") (pinfunction "A5_6") (pintype "bidirectional"))
      (node (ref "REG-IO3-H") (pin "3") (pinfunction "Q1_3") (pintype "tri_state"))
    )
    (net (code "175") (name "/REG-IO3-DATA5") (class "Default")
      (node (ref "LED87") (pin "A") (pinfunction "A_A") (pintype "passive"))
      (node (ref "REG-IO3-BUF") (pin "7") (pinfunction "A6_7") (pintype "bidirectional"))
      (node (ref "REG-IO3-H") (pin "4") (pinfunction "Q2_4") (pintype "tri_state"))
    )
    (net (code "176") (name "/REG-IO3-DATA6") (class "Default")
      (node (ref "LED88") (pin "A") (pinfunction "A_A") (pintype "passive"))
      (node (ref "REG-IO3-BUF") (pin "8") (pinfunction "A7_8") (pintype "bidirectional"))
      (node (ref "REG-IO3-H") (pin "5") (pinfunction "Q3_5") (pintype "tri_state"))
    )
    (net (code "177") (name "/REG-IO3-DATA7") (class "Default")
      (node (ref "LED89") (pin "A") (pinfunction "A_A") (pintype "passive"))
      (node (ref "REG-IO3-BUF") (pin "9") (pinfunction "A8_9") (pintype "bidirectional"))
      (node (ref "REG-IO3-H") (pin "6") (pinfunction "Q4_6") (pintype "tri_state"))
    )
    (net (code "179") (name "/REG-IR-DATA0") (class "Default")
      (node (ref "LED50") (pin "A") (pinfunction "A_A") (pintype "passive"))
      (node (ref "REG-IR-BUF") (pin "2") (pinfunction "A1_2") (pintype "bidirectional"))
      (node (ref "REG-IR-L") (pin "3") (pinfunction "Q1_3") (pintype "tri_state"))
    )
    (net (code "180") (name "/REG-IR-DATA1") (class "Default")
      (node (ref "LED51") (pin "A") (pinfunction "A_A") (pintype "passive"))
      (node (ref "REG-IR-BUF") (pin "3") (pinfunction "A2_3") (pintype "bidirectional"))
      (node (ref "REG-IR-L") (pin "4") (pinfunction "Q2_4") (pintype "tri_state"))
    )
    (net (code "181") (name "/REG-IR-DATA2") (class "Default")
      (node (ref "LED52") (pin "A") (pinfunction "A_A") (pintype "passive"))
      (node (ref "REG-IR-BUF") (pin "4") (pinfunction "A3_4") (pintype "bidirectional"))
      (node (ref "REG-IR-L") (pin "5") (pinfunction "Q3_5") (pintype "tri_state"))
    )
    (net (code "182") (name "/REG-IR-DATA3") (class "Default")
      (node (ref "LED53") (pin "A") (pinfunction "A_A") (pintype "passive"))
      (node (ref "REG-IR-BUF") (pin "5") (pinfunction "A4_5") (pintype "bidirectional"))
      (node (ref "REG-IR-L") (pin "6") (pinfunction "Q4_6") (pintype "tri_state"))
    )
    (net (code "183") (name "/REG-IR-DATA4") (class "Default")
      (node (ref "LED54") (pin "A") (pinfunction "A_A") (pintype "passive"))
      (node (ref "REG-IR-BUF") (pin "6") (pinfunction "A5_6") (pintype "bidirectional"))
      (node (ref "REG-IR-H") (pin "3") (pinfunction "Q1_3") (pintype "tri_state"))
    )
    (net (code "184") (name "/REG-IR-DATA5") (class "Default")
      (node (ref "LED55") (pin "A") (pinfunction "A_A") (pintype "passive"))
      (node (ref "REG-IR-BUF") (pin "7") (pinfunction "A6_7") (pintype "bidirectional"))
      (node (ref "REG-IR-H") (pin "4") (pinfunction "Q2_4") (pintype "tri_state"))
    )
    (net (code "185") (name "/REG-IR-DATA6") (class "Default")
      (node (ref "LED56") (pin "A") (pinfunction "A_A") (pintype "passive"))
      (node (ref "REG-IR-BUF") (pin "8") (pinfunction "A7_8") (pintype "bidirectional"))
      (node (ref "REG-IR-H") (pin "5") (pinfunction "Q3_5") (pintype "tri_state"))
    )
    (net (code "186") (name "/REG-IR-DATA7") (class "Default")
      (node (ref "LED57") (pin "A") (pinfunction "A_A") (pintype "passive"))
      (node (ref "REG-IR-BUF") (pin "9") (pinfunction "A8_9") (pintype "bidirectional"))
      (node (ref "REG-IR-H") (pin "6") (pinfunction "Q4_6") (pintype "tri_state"))
    )
    (net (code "188") (name "/REG-MAR-DATA0") (class "Default")
      (node (ref "LED42") (pin "A") (pinfunction "A_A") (pintype "passive"))
      (node (ref "REG-MAR-BUF") (pin "2") (pinfunction "A1_2") (pintype "bidirectional"))
      (node (ref "REG-MAR-L") (pin "3") (pinfunction "Q1_3") (pintype "tri_state"))
    )
    (net (code "189") (name "/REG-MAR-DATA1") (class "Default")
      (node (ref "LED43") (pin "A") (pinfunction "A_A") (pintype "passive"))
      (node (ref "REG-MAR-BUF") (pin "3") (pinfunction "A2_3") (pintype "bidirectional"))
      (node (ref "REG-MAR-L") (pin "4") (pinfunction "Q2_4") (pintype "tri_state"))
    )
    (net (code "190") (name "/REG-MAR-DATA2") (class "Default")
      (node (ref "LED44") (pin "A") (pinfunction "A_A") (pintype "passive"))
      (node (ref "REG-MAR-BUF") (pin "4") (pinfunction "A3_4") (pintype "bidirectional"))
      (node (ref "REG-MAR-L") (pin "5") (pinfunction "Q3_5") (pintype "tri_state"))
    )
    (net (code "191") (name "/REG-MAR-DATA3") (class "Default")
      (node (ref "LED45") (pin "A") (pinfunction "A_A") (pintype "passive"))
      (node (ref "REG-MAR-BUF") (pin "5") (pinfunction "A4_5") (pintype "bidirectional"))
      (node (ref "REG-MAR-L") (pin "6") (pinfunction "Q4_6") (pintype "tri_state"))
    )
    (net (code "192") (name "/REG-MAR-DATA4") (class "Default")
      (node (ref "LED46") (pin "A") (pinfunction "A_A") (pintype "passive"))
      (node (ref "REG-MAR-BUF") (pin "6") (pinfunction "A5_6") (pintype "bidirectional"))
      (node (ref "REG-MAR-H") (pin "3") (pinfunction "Q1_3") (pintype "tri_state"))
    )
    (net (code "193") (name "/REG-MAR-DATA5") (class "Default")
      (node (ref "LED47") (pin "A") (pinfunction "A_A") (pintype "passive"))
      (node (ref "REG-MAR-BUF") (pin "7") (pinfunction "A6_7") (pintype "bidirectional"))
      (node (ref "REG-MAR-H") (pin "4") (pinfunction "Q2_4") (pintype "tri_state"))
    )
    (net (code "194") (name "/REG-MAR-DATA6") (class "Default")
      (node (ref "LED48") (pin "A") (pinfunction "A_A") (pintype "passive"))
      (node (ref "REG-MAR-BUF") (pin "8") (pinfunction "A7_8") (pintype "bidirectional"))
      (node (ref "REG-MAR-H") (pin "5") (pinfunction "Q3_5") (pintype "tri_state"))
    )
    (net (code "195") (name "/REG-MAR-DATA7") (class "Default")
      (node (ref "LED49") (pin "A") (pinfunction "A_A") (pintype "passive"))
      (node (ref "REG-MAR-BUF") (pin "9") (pinfunction "A8_9") (pintype "bidirectional"))
      (node (ref "REG-MAR-H") (pin "6") (pinfunction "Q4_6") (pintype "tri_state"))
    )
    (net (code "198") (name "/SF") (class "Default")
      (node (ref "AT28C16-0") (pin "3") (pinfunction "A5_3") (pintype "input"))
      (node (ref "AT28C16-1") (pin "3") (pinfunction "A5_3") (pintype "input"))
      (node (ref "AT28C16-2") (pin "3") (pinfunction "A5_3") (pintype "input"))
      (node (ref "AT28C16-3") (pin "3") (pinfunction "A5_3") (pintype "input"))
    )
    (net (code "199") (name "/USTEP-A") (class "Default")
      (node (ref "74LS161N") (pin "14") (pinfunction "QA_14") (pintype "output"))
      (node (ref "AT28C16-0") (pin "8") (pinfunction "A0_8") (pintype "input"))
      (node (ref "AT28C16-1") (pin "8") (pinfunction "A0_8") (pintype "input"))
      (node (ref "AT28C16-2") (pin "8") (pinfunction "A0_8") (pintype "input"))
      (node (ref "AT28C16-3") (pin "8") (pinfunction "A0_8") (pintype "input"))
      (node (ref "IC11") (pin "23") (pinfunction "A_23") (pintype "input"))
    )
    (net (code "200") (name "/USTEP-B") (class "Default")
      (node (ref "74LS161N") (pin "13") (pinfunction "QB_13") (pintype "output"))
      (node (ref "AT28C16-0") (pin "7") (pinfunction "A1_7") (pintype "input"))
      (node (ref "AT28C16-1") (pin "7") (pinfunction "A1_7") (pintype "input"))
      (node (ref "AT28C16-2") (pin "7") (pinfunction "A1_7") (pintype "input"))
      (node (ref "AT28C16-3") (pin "7") (pinfunction "A1_7") (pintype "input"))
      (node (ref "IC11") (pin "22") (pinfunction "B_22") (pintype "input"))
    )
    (net (code "201") (name "/USTEP-C") (class "Default")
      (node (ref "74LS161N") (pin "12") (pinfunction "QC_12") (pintype "output"))
      (node (ref "AT28C16-0") (pin "6") (pinfunction "A2_6") (pintype "input"))
      (node (ref "AT28C16-1") (pin "6") (pinfunction "A2_6") (pintype "input"))
      (node (ref "AT28C16-2") (pin "6") (pinfunction "A2_6") (pintype "input"))
      (node (ref "AT28C16-3") (pin "6") (pinfunction "A2_6") (pintype "input"))
      (node (ref "IC11") (pin "21") (pinfunction "C_21") (pintype "input"))
    )
    (net (code "202") (name "/USTEP-D") (class "Default")
      (node (ref "74LS161N") (pin "11") (pinfunction "QD_11") (pintype "output"))
      (node (ref "AT28C16-0") (pin "5") (pinfunction "A3_5") (pintype "input"))
      (node (ref "AT28C16-1") (pin "5") (pinfunction "A3_5") (pintype "input"))
      (node (ref "AT28C16-2") (pin "5") (pinfunction "A3_5") (pintype "input"))
      (node (ref "AT28C16-3") (pin "5") (pinfunction "A3_5") (pintype "input"))
      (node (ref "IC11") (pin "20") (pinfunction "D_20") (pintype "input"))
    )
    (net (code "203") (name "/ZF") (class "Default")
      (node (ref "AT28C16-0") (pin "2") (pinfunction "A6_2") (pintype "input"))
      (node (ref "AT28C16-1") (pin "2") (pinfunction "A6_2") (pintype "input"))
      (node (ref "AT28C16-2") (pin "2") (pinfunction "A6_2") (pintype "input"))
      (node (ref "AT28C16-3") (pin "2") (pinfunction "A6_2") (pintype "input"))
    )
    (net (code "208") (name "ACU-DATA0") (class "Default")
      (node (ref "IC1") (pin "1") (pinfunction "I_1") (pintype "input"))
      (node (ref "IC35") (pin "13") (pinfunction "I1_13") (pintype "input"))
      (node (ref "IC37") (pin "12") (pinfunction "I0_12") (pintype "input"))
      (node (ref "REG-ACU-BUF1") (pin "18") (pinfunction "B1_18") (pintype "bidirectional"))
    )
    (net (code "209") (name "ACU-DATA1") (class "Default")
      (node (ref "IC2") (pin "1") (pinfunction "I_1") (pintype "input"))
      (node (ref "IC38") (pin "1") (pinfunction "I0_1") (pintype "input"))
      (node (ref "IC39") (pin "2") (pinfunction "I1_2") (pintype "input"))
      (node (ref "REG-ACU-BUF1") (pin "17") (pinfunction "B2_17") (pintype "bidirectional"))
    )
    (net (code "210") (name "ACU-DATA2") (class "Default")
      (node (ref "IC3") (pin "1") (pinfunction "I_1") (pintype "input"))
      (node (ref "IC41") (pin "12") (pinfunction "I0_12") (pintype "input"))
      (node (ref "IC42") (pin "13") (pinfunction "I1_13") (pintype "input"))
      (node (ref "REG-ACU-BUF1") (pin "16") (pinfunction "B3_16") (pintype "bidirectional"))
    )
    (net (code "211") (name "ACU-DATA3") (class "Default")
      (node (ref "IC4") (pin "1") (pinfunction "I_1") (pintype "input"))
      (node (ref "IC44") (pin "1") (pinfunction "I0_1") (pintype "input"))
      (node (ref "IC45") (pin "2") (pinfunction "I1_2") (pintype "input"))
      (node (ref "REG-ACU-BUF1") (pin "15") (pinfunction "B4_15") (pintype "bidirectional"))
    )
    (net (code "212") (name "ACU-DATA4") (class "Default")
      (node (ref "IC48") (pin "13") (pinfunction "I1_13") (pintype "input"))
      (node (ref "IC5") (pin "1") (pinfunction "I_1") (pintype "input"))
      (node (ref "IC50") (pin "12") (pinfunction "I0_12") (pintype "input"))
      (node (ref "REG-ACU-BUF1") (pin "14") (pinfunction "B5_14") (pintype "bidirectional"))
    )
    (net (code "213") (name "ACU-DATA5") (class "Default")
      (node (ref "IC51") (pin "1") (pinfunction "I0_1") (pintype "input"))
      (node (ref "IC52") (pin "2") (pinfunction "I1_2") (pintype "input"))
      (node (ref "IC6") (pin "1") (pinfunction "I_1") (pintype "input"))
      (node (ref "REG-ACU-BUF1") (pin "13") (pinfunction "B6_13") (pintype "bidirectional"))
    )
    (net (code "214") (name "ACU-DATA6") (class "Default")
      (node (ref "IC54") (pin "12") (pinfunction "I0_12") (pintype "input"))
      (node (ref "IC55") (pin "13") (pinfunction "I1_13") (pintype "input"))
      (node (ref "IC7") (pin "1") (pinfunction "I_1") (pintype "input"))
      (node (ref "REG-ACU-BUF1") (pin "12") (pinfunction "B7_12") (pintype "bidirectional"))
    )
    (net (code "215") (name "ACU-DATA7") (class "Default")
      (node (ref "IC57") (pin "1") (pinfunction "I0_1") (pintype "input"))
      (node (ref "IC58") (pin "2") (pinfunction "I1_2") (pintype "input"))
      (node (ref "IC8") (pin "1") (pinfunction "I_1") (pintype "input"))
      (node (ref "REG-ACU-BUF1") (pin "11") (pinfunction "B8_11") (pintype "bidirectional"))
    )
    (net (code "216") (name "ACU-I") (class "Default")
      (node (ref "AT28C16-1") (pin "15") (pinfunction "D5_15") (pintype "bidirectional"))
      (node (ref "REG-ACU-H") (pin "10") (pinfunction "G2_10") (pintype "input"))
      (node (ref "REG-ACU-H") (pin "9") (pinfunction "G1_9") (pintype "input"))
      (node (ref "REG-ACU-L") (pin "10") (pinfunction "G2_10") (pintype "input"))
      (node (ref "REG-ACU-L") (pin "9") (pinfunction "G1_9") (pintype "input"))
    )
    (net (code "217") (name "ACU-O") (class "Default")
      (node (ref "AT28C16-2") (pin "14") (pinfunction "D4_14") (pintype "bidirectional"))
      (node (ref "REG-ACU-BUF0") (pin "19") (pinfunction "G_19") (pintype "input"))
    )
    (net (code "218") (name "ADD0-B0-IN") (class "Default")
      (node (ref "4BIT-FULL-ADDER-2") (pin "6") (pinfunction "B1_6") (pintype "input"))
      (node (ref "IC46") (pin "3") (pinfunction "O_3") (pintype "output"))
    )
    (net (code "219") (name "ADD0-B1-IN") (class "Default")
      (node (ref "4BIT-FULL-ADDER-2") (pin "2") (pinfunction "B2_2") (pintype "input"))
      (node (ref "IC46") (pin "6") (pinfunction "O_6") (pintype "output"))
    )
    (net (code "220") (name "ADD0-B2-IN") (class "Default")
      (node (ref "4BIT-FULL-ADDER-2") (pin "15") (pinfunction "B3_15") (pintype "input"))
      (node (ref "IC46") (pin "8") (pinfunction "O_8") (pintype "output"))
    )
    (net (code "221") (name "ADD0-B3-IN") (class "Default")
      (node (ref "4BIT-FULL-ADDER-2") (pin "11") (pinfunction "B4_11") (pintype "input"))
      (node (ref "IC46") (pin "11") (pinfunction "O_11") (pintype "output"))
    )
    (net (code "222") (name "ADD1-B4-IN") (class "Default")
      (node (ref "4BIT-FULL-ADDER-3") (pin "6") (pinfunction "B1_6") (pintype "input"))
      (node (ref "IC47") (pin "3") (pinfunction "O_3") (pintype "output"))
    )
    (net (code "223") (name "ADD1-B5-IN") (class "Default")
      (node (ref "4BIT-FULL-ADDER-3") (pin "2") (pinfunction "B2_2") (pintype "input"))
      (node (ref "IC47") (pin "6") (pinfunction "O_6") (pintype "output"))
    )
    (net (code "224") (name "ADD1-B6-IN") (class "Default")
      (node (ref "4BIT-FULL-ADDER-3") (pin "15") (pinfunction "B3_15") (pintype "input"))
      (node (ref "IC47") (pin "8") (pinfunction "O_8") (pintype "output"))
    )
    (net (code "225") (name "ADD1-B7-IN") (class "Default")
      (node (ref "4BIT-FULL-ADDER-3") (pin "11") (pinfunction "B4_11") (pintype "input"))
      (node (ref "IC47") (pin "11") (pinfunction "O_11") (pintype "output"))
    )
    (net (code "226") (name "ADDR-BUS0") (class "Default")
      (node (ref "74LS161N-0") (pin "14") (pinfunction "QA_14") (pintype "output"))
      (node (ref "ADDR-R/P-SW-0") (pin "2") (pinfunction "1A_2") (pintype "input"))
      (node (ref "PC-BUF-L") (pin "2") (pinfunction "A1_2") (pintype "bidirectional"))
    )
    (net (code "227") (name "ADDR-BUS1") (class "Default")
      (node (ref "74LS161N-0") (pin "13") (pinfunction "QB_13") (pintype "output"))
      (node (ref "ADDR-R/P-SW-0") (pin "5") (pinfunction "2A_5") (pintype "input"))
      (node (ref "PC-BUF-L") (pin "3") (pinfunction "A2_3") (pintype "bidirectional"))
    )
    (net (code "228") (name "ADDR-BUS2") (class "Default")
      (node (ref "74LS161N-0") (pin "12") (pinfunction "QC_12") (pintype "output"))
      (node (ref "ADDR-R/P-SW-0") (pin "11") (pinfunction "3A_11") (pintype "input"))
      (node (ref "PC-BUF-L") (pin "4") (pinfunction "A3_4") (pintype "bidirectional"))
    )
    (net (code "229") (name "ADDR-BUS3") (class "Default")
      (node (ref "74LS161N-0") (pin "11") (pinfunction "QD_11") (pintype "output"))
      (node (ref "ADDR-R/P-SW-0") (pin "14") (pinfunction "4A_14") (pintype "input"))
      (node (ref "PC-BUF-L") (pin "5") (pinfunction "A4_5") (pintype "bidirectional"))
    )
    (net (code "230") (name "ADDR-BUS4") (class "Default")
      (node (ref "74LS161N-1") (pin "14") (pinfunction "QA_14") (pintype "output"))
      (node (ref "74LS161N-2") (pin "14") (pinfunction "QA_14") (pintype "output"))
      (node (ref "ADDR-R/P-SW-1") (pin "2") (pinfunction "1A_2") (pintype "input"))
      (node (ref "PC-BUF-H") (pin "2") (pinfunction "A1_2") (pintype "bidirectional"))
      (node (ref "PC-BUF-L") (pin "6") (pinfunction "A5_6") (pintype "bidirectional"))
    )
    (net (code "231") (name "ADDR-BUS5") (class "Default")
      (node (ref "74LS161N-1") (pin "13") (pinfunction "QB_13") (pintype "output"))
      (node (ref "74LS161N-2") (pin "13") (pinfunction "QB_13") (pintype "output"))
      (node (ref "ADDR-R/P-SW-1") (pin "5") (pinfunction "2A_5") (pintype "input"))
      (node (ref "PC-BUF-H") (pin "3") (pinfunction "A2_3") (pintype "bidirectional"))
      (node (ref "PC-BUF-L") (pin "7") (pinfunction "A6_7") (pintype "bidirectional"))
    )
    (net (code "232") (name "ADDR-BUS6") (class "Default")
      (node (ref "74LS161N-1") (pin "12") (pinfunction "QC_12") (pintype "output"))
      (node (ref "74LS161N-2") (pin "12") (pinfunction "QC_12") (pintype "output"))
      (node (ref "ADDR-R/P-SW-1") (pin "11") (pinfunction "3A_11") (pintype "input"))
      (node (ref "PC-BUF-H") (pin "4") (pinfunction "A3_4") (pintype "bidirectional"))
      (node (ref "PC-BUF-L") (pin "8") (pinfunction "A7_8") (pintype "bidirectional"))
    )
    (net (code "233") (name "ADDR-BUS7") (class "Default")
      (node (ref "74LS161N-1") (pin "11") (pinfunction "QD_11") (pintype "output"))
      (node (ref "74LS161N-2") (pin "11") (pinfunction "QD_11") (pintype "output"))
      (node (ref "ADDR-R/P-SW-1") (pin "14") (pinfunction "4A_14") (pintype "input"))
      (node (ref "PC-BUF-H") (pin "5") (pinfunction "A4_5") (pintype "bidirectional"))
      (node (ref "PC-BUF-L") (pin "9") (pinfunction "A8_9") (pintype "bidirectional"))
    )
    (net (code "234") (name "ADDR-BUS12") (class "Default")
      (node (ref "74LS161N-3") (pin "3") (pinfunction "A_3") (pintype "input"))
      (node (ref "ADDR-R/P-SW-3") (pin "2") (pinfunction "1A_2") (pintype "input"))
      (node (ref "CHIP-SELECT-REG-0") (pin "5") (pinfunction "Q3_5") (pintype "tri_state"))
    )
    (net (code "235") (name "ADDR-PAGE8") (class "Default")
      (node (ref "ADDR-R/P-SW-2") (pin "2") (pinfunction "1A_2") (pintype "input"))
    )
    (net (code "236") (name "ADDR-PAGE9") (class "Default")
      (node (ref "ADDR-R/P-SW-2") (pin "5") (pinfunction "2A_5") (pintype "input"))
    )
    (net (code "237") (name "ADDR-PAGE10") (class "Default")
      (node (ref "ADDR-R/P-SW-2") (pin "11") (pinfunction "3A_11") (pintype "input"))
    )
    (net (code "238") (name "ADDR-PAGE11") (class "Default")
      (node (ref "ADDR-R/P-SW-2") (pin "14") (pinfunction "4A_14") (pintype "input"))
    )
    (net (code "239") (name "ALU-A") (class "Default")
      (node (ref "AT28C16-1") (pin "10") (pinfunction "D1_10") (pintype "bidirectional"))
      (node (ref "DUAL-4X1-MUX-0") (pin "14") (pinfunction "A_14") (pintype "input"))
      (node (ref "DUAL-4X1-MUX-1") (pin "14") (pinfunction "A_14") (pintype "input"))
      (node (ref "DUAL-4X1-MUX-2") (pin "14") (pinfunction "A_14") (pintype "input"))
      (node (ref "DUAL-4X1-MUX-3") (pin "14") (pinfunction "A_14") (pintype "input"))
    )
    (net (code "240") (name "ALU-B") (class "Default")
      (node (ref "AT28C16-1") (pin "11") (pinfunction "D2_11") (pintype "bidirectional"))
      (node (ref "DUAL-4X1-MUX-0") (pin "2") (pinfunction "B_2") (pintype "input"))
      (node (ref "DUAL-4X1-MUX-1") (pin "2") (pinfunction "B_2") (pintype "input"))
      (node (ref "DUAL-4X1-MUX-2") (pin "2") (pinfunction "B_2") (pintype "input"))
      (node (ref "DUAL-4X1-MUX-3") (pin "2") (pinfunction "B_2") (pintype "input"))
    )
    (net (code "241") (name "ALU-C") (class "Default")
      (node (ref "4BIT-FULL-ADDER-2") (pin "7") (pinfunction "C0_7") (pintype "input"))
      (node (ref "AT28C16-1") (pin "13") (pinfunction "D3_13") (pintype "bidirectional"))
      (node (ref "IC46") (pin "1") (pinfunction "I0_1") (pintype "input"))
      (node (ref "IC46") (pin "12") (pinfunction "I0_12") (pintype "input"))
      (node (ref "IC46") (pin "4") (pinfunction "I0_4") (pintype "input"))
      (node (ref "IC46") (pin "9") (pinfunction "I0_9") (pintype "input"))
      (node (ref "IC47") (pin "1") (pinfunction "I0_1") (pintype "input"))
      (node (ref "IC47") (pin "12") (pinfunction "I0_12") (pintype "input"))
      (node (ref "IC47") (pin "4") (pinfunction "I0_4") (pintype "input"))
      (node (ref "IC47") (pin "9") (pinfunction "I0_9") (pintype "input"))
    )
    (net (code "242") (name "ALU-C0-OUT") (class "Default")
      (node (ref "ALU-BUF") (pin "2") (pinfunction "A1_2") (pintype "bidirectional"))
      (node (ref "DUAL-4X1-MUX-0") (pin "7") (pinfunction "1Y_7") (pintype "output"))
    )
    (net (code "243") (name "ALU-C1-OUT") (class "Default")
      (node (ref "ALU-BUF") (pin "3") (pinfunction "A2_3") (pintype "bidirectional"))
      (node (ref "DUAL-4X1-MUX-0") (pin "9") (pinfunction "2Y_9") (pintype "output"))
    )
    (net (code "244") (name "ALU-C2-OUT") (class "Default")
      (node (ref "ALU-BUF") (pin "4") (pinfunction "A3_4") (pintype "bidirectional"))
      (node (ref "DUAL-4X1-MUX-1") (pin "7") (pinfunction "1Y_7") (pintype "output"))
    )
    (net (code "245") (name "ALU-C3-OUT") (class "Default")
      (node (ref "ALU-BUF") (pin "5") (pinfunction "A4_5") (pintype "bidirectional"))
      (node (ref "DUAL-4X1-MUX-1") (pin "9") (pinfunction "2Y_9") (pintype "output"))
    )
    (net (code "246") (name "ALU-C4-OUT") (class "Default")
      (node (ref "ALU-BUF") (pin "6") (pinfunction "A5_6") (pintype "bidirectional"))
      (node (ref "DUAL-4X1-MUX-2") (pin "7") (pinfunction "1Y_7") (pintype "output"))
    )
    (net (code "247") (name "ALU-C5-OUT") (class "Default")
      (node (ref "ALU-BUF") (pin "7") (pinfunction "A6_7") (pintype "bidirectional"))
      (node (ref "DUAL-4X1-MUX-2") (pin "9") (pinfunction "2Y_9") (pintype "output"))
    )
    (net (code "248") (name "ALU-C6-OUT") (class "Default")
      (node (ref "ALU-BUF") (pin "8") (pinfunction "A7_8") (pintype "bidirectional"))
      (node (ref "DUAL-4X1-MUX-3") (pin "7") (pinfunction "1Y_7") (pintype "output"))
    )
    (net (code "249") (name "ALU-C7-OUT") (class "Default")
      (node (ref "ALU-BUF") (pin "9") (pinfunction "A8_9") (pintype "bidirectional"))
      (node (ref "DUAL-4X1-MUX-3") (pin "9") (pinfunction "2Y_9") (pintype "output"))
    )
    (net (code "250") (name "ALU-EO") (class "Default")
      (node (ref "REG-ACU-BUF1") (pin "19") (pinfunction "G_19") (pintype "input"))
    )
    (net (code "251") (name "ALU-O") (class "Default")
      (node (ref "ALU-BUF") (pin "19") (pinfunction "G_19") (pintype "input"))
      (node (ref "AT28C16-1") (pin "9") (pinfunction "D0_9") (pintype "bidirectional"))
    )
    (net (code "252") (name "CARRY-1") (class "Default")
      (node (ref "4BIT-FULL-ADDER-3") (pin "9") (pinfunction "C4_9") (pintype "output"))
    )
    (net (code "253") (name "CLK-DIS") (class "Default")
      (node (ref "CLK") (pin "7") (pinfunction "DIS_7") (pintype "input"))
      (node (ref "Q1") (pin "C") (pinfunction "C_C") (pintype "passive"))
      (node (ref "R3") (pin "1") (pinfunction "1_1") (pintype "passive"))
    )
    (net (code "254") (name "CLK-SIG") (class "Default")
      (node (ref "74LS161N") (pin "2") (pinfunction "CLK_2") (pintype "input"))
      (node (ref "74LS161N-0") (pin "2") (pinfunction "CLK_2") (pintype "input"))
      (node (ref "74LS161N-1") (pin "2") (pinfunction "CLK_2") (pintype "input"))
      (node (ref "74LS161N-2") (pin "2") (pinfunction "CLK_2") (pintype "input"))
      (node (ref "74LS161N-3") (pin "2") (pinfunction "CLK_2") (pintype "input"))
      (node (ref "CHIP-SELECT-REG-0") (pin "7") (pinfunction "CLK_7") (pintype "input"))
      (node (ref "IC10") (pin "1") (pinfunction "I_1") (pintype "input"))
      (node (ref "IC10") (pin "2") (pinfunction "O_2") (pintype "output"))
      (node (ref "LED1") (pin "K") (pinfunction "C_K") (pintype "passive"))
      (node (ref "PAGE-ADDR-REG-0") (pin "7") (pinfunction "CLK_7") (pintype "input"))
      (node (ref "REG-ACU-H") (pin "7") (pinfunction "CLK_7") (pintype "input"))
      (node (ref "REG-ACU-L") (pin "7") (pinfunction "CLK_7") (pintype "input"))
      (node (ref "REG-IO0-H") (pin "7") (pinfunction "CLK_7") (pintype "input"))
      (node (ref "REG-IO0-L") (pin "7") (pinfunction "CLK_7") (pintype "input"))
      (node (ref "REG-IO1-H") (pin "7") (pinfunction "CLK_7") (pintype "input"))
      (node (ref "REG-IO1-L") (pin "7") (pinfunction "CLK_7") (pintype "input"))
      (node (ref "REG-IO2-H") (pin "7") (pinfunction "CLK_7") (pintype "input"))
      (node (ref "REG-IO2-L") (pin "7") (pinfunction "CLK_7") (pintype "input"))
      (node (ref "REG-IO3-H") (pin "7") (pinfunction "CLK_7") (pintype "input"))
      (node (ref "REG-IO3-L") (pin "7") (pinfunction "CLK_7") (pintype "input"))
      (node (ref "REG-IR-H") (pin "7") (pinfunction "CLK_7") (pintype "input"))
      (node (ref "REG-IR-L") (pin "7") (pinfunction "CLK_7") (pintype "input"))
      (node (ref "REG-MAR-H") (pin "7") (pinfunction "CLK_7") (pintype "input"))
      (node (ref "REG-MAR-L") (pin "7") (pinfunction "CLK_7") (pintype "input"))
      (node (ref "REG-MBR-H") (pin "7") (pinfunction "CLK_7") (pintype "input"))
      (node (ref "REG-MBR-L") (pin "7") (pinfunction "CLK_7") (pintype "input"))
    )
    (net (code "255") (name "CLK-TR-THR") (class "Default")
      (node (ref "C2") (pin "+") (pinfunction "+_+") (pintype "passive"))
      (node (ref "CLK") (pin "2") (pinfunction "TR_2") (pintype "input"))
      (node (ref "CLK") (pin "6") (pinfunction "THR_6") (pintype "input"))
      (node (ref "Q1") (pin "B") (pinfunction "B_B") (pintype "passive"))
      (node (ref "R2") (pin "2") (pinfunction "S_2") (pintype "passive"))
      (node (ref "R6") (pin "1") (pinfunction "1_1") (pintype "passive"))
      (node (ref "R6") (pin "2") (pinfunction "2_2") (pintype "passive"))
      (node (ref "S2") (pin "1") (pinfunction "S_1") (pintype "passive"))
    )
    (net (code "256") (name "COUNTER-CARRY-0") (class "Default")
      (node (ref "74LS161N-0") (pin "15") (pinfunction "RCO_15") (pintype "output"))
      (node (ref "74LS161N-1") (pin "10") (pinfunction "ENT_10") (pintype "input"))
    )
    (net (code "257") (name "COUNTER-CARRY-1") (class "Default")
      (node (ref "74LS161N-1") (pin "15") (pinfunction "RCO_15") (pintype "output"))
      (node (ref "74LS161N-2") (pin "10") (pinfunction "ENT_10") (pintype "input"))
    )
    (net (code "258") (name "COUNTER-CARRY-2") (class "Default")
      (node (ref "74LS161N-2") (pin "15") (pinfunction "RCO_15") (pintype "output"))
      (node (ref "74LS161N-3") (pin "10") (pinfunction "ENT_10") (pintype "input"))
    )
    (net (code "259") (name "CS-I") (class "Default")
      (node (ref "AT28C16-3") (pin "14") (pinfunction "D4_14") (pintype "bidirectional"))
      (node (ref "CHIP-SELECT-REG-0") (pin "10") (pinfunction "G2_10") (pintype "input"))
      (node (ref "CHIP-SELECT-REG-0") (pin "9") (pinfunction "G1_9") (pintype "input"))
    )
    (net (code "260") (name "CS0") (class "Default")
      (node (ref "CHIP-SELECT-REG-0") (pin "3") (pinfunction "Q1_3") (pintype "tri_state"))
      (node (ref "DEMUX-2X4-0") (pin "2") (pinfunction "A_2") (pintype "input"))
    )
    (net (code "261") (name "CS1") (class "Default")
      (node (ref "CHIP-SELECT-REG-0") (pin "4") (pinfunction "Q2_4") (pintype "tri_state"))
      (node (ref "DEMUX-2X4-0") (pin "3") (pinfunction "B_3") (pintype "input"))
    )
    (net (code "262") (name "DATA-BUS0") (class "Default")
      (node (ref "74LS161N-0") (pin "3") (pinfunction "A_3") (pintype "input"))
      (node (ref "ALU-BUF") (pin "18") (pinfunction "B1_18") (pintype "bidirectional"))
      (node (ref "CHIP-SELECT-REG-0") (pin "14") (pinfunction "D1_14") (pintype "input"))
      (node (ref "DATA-R/P-SW-0") (pin "2") (pinfunction "1A_2") (pintype "input"))
      (node (ref "DATA-R/P-SW-0") (pin "4") (pinfunction "1Y_4") (pintype "output"))
      (node (ref "MEM-BUF") (pin "18") (pinfunction "B1_18") (pintype "bidirectional"))
      (node (ref "PC-BUF-L") (pin "18") (pinfunction "B1_18") (pintype "bidirectional"))
      (node (ref "REG-ACU-BUF0") (pin "18") (pinfunction "B1_18") (pintype "bidirectional"))
      (node (ref "REG-ACU-L") (pin "14") (pinfunction "D1_14") (pintype "input"))
      (node (ref "REG-IO0-BUF") (pin "18") (pinfunction "B1_18") (pintype "bidirectional"))
      (node (ref "REG-IO0-L") (pin "14") (pinfunction "D1_14") (pintype "input"))
      (node (ref "REG-IO1-BUF") (pin "18") (pinfunction "B1_18") (pintype "bidirectional"))
      (node (ref "REG-IO1-L") (pin "14") (pinfunction "D1_14") (pintype "input"))
      (node (ref "REG-IO2-BUF") (pin "18") (pinfunction "B1_18") (pintype "bidirectional"))
      (node (ref "REG-IO2-L") (pin "14") (pinfunction "D1_14") (pintype "input"))
      (node (ref "REG-IO3-BUF") (pin "18") (pinfunction "B1_18") (pintype "bidirectional"))
      (node (ref "REG-IO3-L") (pin "14") (pinfunction "D1_14") (pintype "input"))
      (node (ref "REG-IR-BUF") (pin "18") (pinfunction "B1_18") (pintype "bidirectional"))
      (node (ref "REG-IR-L") (pin "14") (pinfunction "D1_14") (pintype "input"))
      (node (ref "REG-MAR-BUF") (pin "18") (pinfunction "B1_18") (pintype "bidirectional"))
      (node (ref "REG-MAR-L") (pin "14") (pinfunction "D1_14") (pintype "input"))
      (node (ref "REG-MBR-BUF0") (pin "18") (pinfunction "B1_18") (pintype "bidirectional"))
      (node (ref "REG-MBR-L") (pin "14") (pinfunction "D1_14") (pintype "input"))
    )
    (net (code "263") (name "DATA-BUS1") (class "Default")
      (node (ref "74LS161N-0") (pin "4") (pinfunction "B_4") (pintype "input"))
      (node (ref "ALU-BUF") (pin "17") (pinfunction "B2_17") (pintype "bidirectional"))
      (node (ref "CHIP-SELECT-REG-0") (pin "13") (pinfunction "D2_13") (pintype "input"))
      (node (ref "DATA-R/P-SW-0") (pin "5") (pinfunction "2A_5") (pintype "input"))
      (node (ref "DATA-R/P-SW-0") (pin "7") (pinfunction "2Y_7") (pintype "output"))
      (node (ref "MEM-BUF") (pin "17") (pinfunction "B2_17") (pintype "bidirectional"))
      (node (ref "PC-BUF-L") (pin "17") (pinfunction "B2_17") (pintype "bidirectional"))
      (node (ref "REG-ACU-BUF0") (pin "17") (pinfunction "B2_17") (pintype "bidirectional"))
      (node (ref "REG-ACU-L") (pin "13") (pinfunction "D2_13") (pintype "input"))
      (node (ref "REG-IO0-BUF") (pin "17") (pinfunction "B2_17") (pintype "bidirectional"))
      (node (ref "REG-IO0-L") (pin "13") (pinfunction "D2_13") (pintype "input"))
      (node (ref "REG-IO1-BUF") (pin "17") (pinfunction "B2_17") (pintype "bidirectional"))
      (node (ref "REG-IO1-L") (pin "13") (pinfunction "D2_13") (pintype "input"))
      (node (ref "REG-IO2-BUF") (pin "17") (pinfunction "B2_17") (pintype "bidirectional"))
      (node (ref "REG-IO2-L") (pin "13") (pinfunction "D2_13") (pintype "input"))
      (node (ref "REG-IO3-BUF") (pin "17") (pinfunction "B2_17") (pintype "bidirectional"))
      (node (ref "REG-IO3-L") (pin "13") (pinfunction "D2_13") (pintype "input"))
      (node (ref "REG-IR-BUF") (pin "17") (pinfunction "B2_17") (pintype "bidirectional"))
      (node (ref "REG-IR-L") (pin "13") (pinfunction "D2_13") (pintype "input"))
      (node (ref "REG-MAR-BUF") (pin "17") (pinfunction "B2_17") (pintype "bidirectional"))
      (node (ref "REG-MAR-L") (pin "13") (pinfunction "D2_13") (pintype "input"))
      (node (ref "REG-MBR-BUF0") (pin "17") (pinfunction "B2_17") (pintype "bidirectional"))
      (node (ref "REG-MBR-L") (pin "13") (pinfunction "D2_13") (pintype "input"))
    )
    (net (code "264") (name "DATA-BUS2") (class "Default")
      (node (ref "74LS161N-0") (pin "5") (pinfunction "C_5") (pintype "input"))
      (node (ref "ALU-BUF") (pin "16") (pinfunction "B3_16") (pintype "bidirectional"))
      (node (ref "CHIP-SELECT-REG-0") (pin "12") (pinfunction "D3_12") (pintype "input"))
      (node (ref "DATA-R/P-SW-0") (pin "11") (pinfunction "3A_11") (pintype "input"))
      (node (ref "DATA-R/P-SW-0") (pin "9") (pinfunction "3Y_9") (pintype "output"))
      (node (ref "MEM-BUF") (pin "16") (pinfunction "B3_16") (pintype "bidirectional"))
      (node (ref "PC-BUF-L") (pin "16") (pinfunction "B3_16") (pintype "bidirectional"))
      (node (ref "REG-ACU-BUF0") (pin "16") (pinfunction "B3_16") (pintype "bidirectional"))
      (node (ref "REG-ACU-L") (pin "12") (pinfunction "D3_12") (pintype "input"))
      (node (ref "REG-IO0-BUF") (pin "16") (pinfunction "B3_16") (pintype "bidirectional"))
      (node (ref "REG-IO0-L") (pin "12") (pinfunction "D3_12") (pintype "input"))
      (node (ref "REG-IO1-BUF") (pin "16") (pinfunction "B3_16") (pintype "bidirectional"))
      (node (ref "REG-IO1-L") (pin "12") (pinfunction "D3_12") (pintype "input"))
      (node (ref "REG-IO2-BUF") (pin "16") (pinfunction "B3_16") (pintype "bidirectional"))
      (node (ref "REG-IO2-L") (pin "12") (pinfunction "D3_12") (pintype "input"))
      (node (ref "REG-IO3-BUF") (pin "16") (pinfunction "B3_16") (pintype "bidirectional"))
      (node (ref "REG-IO3-L") (pin "12") (pinfunction "D3_12") (pintype "input"))
      (node (ref "REG-IR-BUF") (pin "16") (pinfunction "B3_16") (pintype "bidirectional"))
      (node (ref "REG-IR-L") (pin "12") (pinfunction "D3_12") (pintype "input"))
      (node (ref "REG-MAR-BUF") (pin "16") (pinfunction "B3_16") (pintype "bidirectional"))
      (node (ref "REG-MAR-L") (pin "12") (pinfunction "D3_12") (pintype "input"))
      (node (ref "REG-MBR-BUF0") (pin "16") (pinfunction "B3_16") (pintype "bidirectional"))
      (node (ref "REG-MBR-L") (pin "12") (pinfunction "D3_12") (pintype "input"))
    )
    (net (code "265") (name "DATA-BUS3") (class "Default")
      (node (ref "74LS161N-0") (pin "6") (pinfunction "D_6") (pintype "input"))
      (node (ref "ALU-BUF") (pin "15") (pinfunction "B4_15") (pintype "bidirectional"))
      (node (ref "CHIP-SELECT-REG-0") (pin "11") (pinfunction "D4_11") (pintype "input"))
      (node (ref "DATA-R/P-SW-0") (pin "12") (pinfunction "4Y_12") (pintype "output"))
      (node (ref "DATA-R/P-SW-0") (pin "14") (pinfunction "4A_14") (pintype "input"))
      (node (ref "MEM-BUF") (pin "15") (pinfunction "B4_15") (pintype "bidirectional"))
      (node (ref "PC-BUF-L") (pin "15") (pinfunction "B4_15") (pintype "bidirectional"))
      (node (ref "REG-ACU-BUF0") (pin "15") (pinfunction "B4_15") (pintype "bidirectional"))
      (node (ref "REG-ACU-L") (pin "11") (pinfunction "D4_11") (pintype "input"))
      (node (ref "REG-IO0-BUF") (pin "15") (pinfunction "B4_15") (pintype "bidirectional"))
      (node (ref "REG-IO0-L") (pin "11") (pinfunction "D4_11") (pintype "input"))
      (node (ref "REG-IO1-BUF") (pin "15") (pinfunction "B4_15") (pintype "bidirectional"))
      (node (ref "REG-IO1-L") (pin "11") (pinfunction "D4_11") (pintype "input"))
      (node (ref "REG-IO2-BUF") (pin "15") (pinfunction "B4_15") (pintype "bidirectional"))
      (node (ref "REG-IO2-L") (pin "11") (pinfunction "D4_11") (pintype "input"))
      (node (ref "REG-IO3-BUF") (pin "15") (pinfunction "B4_15") (pintype "bidirectional"))
      (node (ref "REG-IO3-L") (pin "11") (pinfunction "D4_11") (pintype "input"))
      (node (ref "REG-IR-BUF") (pin "15") (pinfunction "B4_15") (pintype "bidirectional"))
      (node (ref "REG-IR-L") (pin "11") (pinfunction "D4_11") (pintype "input"))
      (node (ref "REG-MAR-BUF") (pin "15") (pinfunction "B4_15") (pintype "bidirectional"))
      (node (ref "REG-MAR-L") (pin "11") (pinfunction "D4_11") (pintype "input"))
      (node (ref "REG-MBR-BUF0") (pin "15") (pinfunction "B4_15") (pintype "bidirectional"))
      (node (ref "REG-MBR-L") (pin "11") (pinfunction "D4_11") (pintype "input"))
    )
    (net (code "266") (name "DATA-BUS4") (class "Default")
      (node (ref "74LS161N-1") (pin "3") (pinfunction "A_3") (pintype "input"))
      (node (ref "74LS161N-2") (pin "3") (pinfunction "A_3") (pintype "input"))
      (node (ref "ALU-BUF") (pin "14") (pinfunction "B5_14") (pintype "bidirectional"))
      (node (ref "DATA-R/P-SW-1") (pin "2") (pinfunction "1A_2") (pintype "input"))
      (node (ref "DATA-R/P-SW-1") (pin "4") (pinfunction "1Y_4") (pintype "output"))
      (node (ref "MEM-BUF") (pin "14") (pinfunction "B5_14") (pintype "bidirectional"))
      (node (ref "PAGE-ADDR-REG-0") (pin "14") (pinfunction "D1_14") (pintype "input"))
      (node (ref "PAGE-ADDR-REG-0") (pin "3") (pinfunction "Q1_3") (pintype "tri_state"))
      (node (ref "PC-BUF-H") (pin "18") (pinfunction "B1_18") (pintype "bidirectional"))
      (node (ref "PC-BUF-L") (pin "14") (pinfunction "B5_14") (pintype "bidirectional"))
      (node (ref "REG-ACU-BUF0") (pin "14") (pinfunction "B5_14") (pintype "bidirectional"))
      (node (ref "REG-ACU-H") (pin "14") (pinfunction "D1_14") (pintype "input"))
      (node (ref "REG-IO0-BUF") (pin "14") (pinfunction "B5_14") (pintype "bidirectional"))
      (node (ref "REG-IO0-H") (pin "14") (pinfunction "D1_14") (pintype "input"))
      (node (ref "REG-IO1-BUF") (pin "14") (pinfunction "B5_14") (pintype "bidirectional"))
      (node (ref "REG-IO1-H") (pin "14") (pinfunction "D1_14") (pintype "input"))
      (node (ref "REG-IO2-BUF") (pin "14") (pinfunction "B5_14") (pintype "bidirectional"))
      (node (ref "REG-IO2-H") (pin "14") (pinfunction "D1_14") (pintype "input"))
      (node (ref "REG-IO3-BUF") (pin "14") (pinfunction "B5_14") (pintype "bidirectional"))
      (node (ref "REG-IO3-H") (pin "14") (pinfunction "D1_14") (pintype "input"))
      (node (ref "REG-IR-H") (pin "14") (pinfunction "D1_14") (pintype "input"))
      (node (ref "REG-MAR-BUF") (pin "14") (pinfunction "B5_14") (pintype "bidirectional"))
      (node (ref "REG-MAR-H") (pin "14") (pinfunction "D1_14") (pintype "input"))
      (node (ref "REG-MBR-BUF0") (pin "14") (pinfunction "B5_14") (pintype "bidirectional"))
      (node (ref "REG-MBR-H") (pin "14") (pinfunction "D1_14") (pintype "input"))
    )
    (net (code "267") (name "DATA-BUS5") (class "Default")
      (node (ref "74LS161N-1") (pin "4") (pinfunction "B_4") (pintype "input"))
      (node (ref "74LS161N-2") (pin "4") (pinfunction "B_4") (pintype "input"))
      (node (ref "ALU-BUF") (pin "13") (pinfunction "B6_13") (pintype "bidirectional"))
      (node (ref "DATA-R/P-SW-1") (pin "5") (pinfunction "2A_5") (pintype "input"))
      (node (ref "DATA-R/P-SW-1") (pin "7") (pinfunction "2Y_7") (pintype "output"))
      (node (ref "MEM-BUF") (pin "13") (pinfunction "B6_13") (pintype "bidirectional"))
      (node (ref "PAGE-ADDR-REG-0") (pin "13") (pinfunction "D2_13") (pintype "input"))
      (node (ref "PAGE-ADDR-REG-0") (pin "4") (pinfunction "Q2_4") (pintype "tri_state"))
      (node (ref "PC-BUF-H") (pin "17") (pinfunction "B2_17") (pintype "bidirectional"))
      (node (ref "PC-BUF-L") (pin "13") (pinfunction "B6_13") (pintype "bidirectional"))
      (node (ref "REG-ACU-BUF0") (pin "13") (pinfunction "B6_13") (pintype "bidirectional"))
      (node (ref "REG-ACU-H") (pin "13") (pinfunction "D2_13") (pintype "input"))
      (node (ref "REG-IO0-BUF") (pin "13") (pinfunction "B6_13") (pintype "bidirectional"))
      (node (ref "REG-IO0-H") (pin "13") (pinfunction "D2_13") (pintype "input"))
      (node (ref "REG-IO1-BUF") (pin "13") (pinfunction "B6_13") (pintype "bidirectional"))
      (node (ref "REG-IO1-H") (pin "13") (pinfunction "D2_13") (pintype "input"))
      (node (ref "REG-IO2-BUF") (pin "13") (pinfunction "B6_13") (pintype "bidirectional"))
      (node (ref "REG-IO2-H") (pin "13") (pinfunction "D2_13") (pintype "input"))
      (node (ref "REG-IO3-BUF") (pin "13") (pinfunction "B6_13") (pintype "bidirectional"))
      (node (ref "REG-IO3-H") (pin "13") (pinfunction "D2_13") (pintype "input"))
      (node (ref "REG-IR-H") (pin "13") (pinfunction "D2_13") (pintype "input"))
      (node (ref "REG-MAR-BUF") (pin "13") (pinfunction "B6_13") (pintype "bidirectional"))
      (node (ref "REG-MAR-H") (pin "13") (pinfunction "D2_13") (pintype "input"))
      (node (ref "REG-MBR-BUF0") (pin "13") (pinfunction "B6_13") (pintype "bidirectional"))
      (node (ref "REG-MBR-H") (pin "13") (pinfunction "D2_13") (pintype "input"))
    )
    (net (code "268") (name "DATA-BUS6") (class "Default")
      (node (ref "74LS161N-1") (pin "5") (pinfunction "C_5") (pintype "input"))
      (node (ref "74LS161N-2") (pin "5") (pinfunction "C_5") (pintype "input"))
      (node (ref "ALU-BUF") (pin "12") (pinfunction "B7_12") (pintype "bidirectional"))
      (node (ref "DATA-R/P-SW-1") (pin "11") (pinfunction "3A_11") (pintype "input"))
      (node (ref "DATA-R/P-SW-1") (pin "9") (pinfunction "3Y_9") (pintype "output"))
      (node (ref "MEM-BUF") (pin "12") (pinfunction "B7_12") (pintype "bidirectional"))
      (node (ref "PAGE-ADDR-REG-0") (pin "12") (pinfunction "D3_12") (pintype "input"))
      (node (ref "PAGE-ADDR-REG-0") (pin "5") (pinfunction "Q3_5") (pintype "tri_state"))
      (node (ref "PC-BUF-H") (pin "16") (pinfunction "B3_16") (pintype "bidirectional"))
      (node (ref "PC-BUF-L") (pin "12") (pinfunction "B7_12") (pintype "bidirectional"))
      (node (ref "REG-ACU-BUF0") (pin "12") (pinfunction "B7_12") (pintype "bidirectional"))
      (node (ref "REG-ACU-H") (pin "12") (pinfunction "D3_12") (pintype "input"))
      (node (ref "REG-IO0-BUF") (pin "12") (pinfunction "B7_12") (pintype "bidirectional"))
      (node (ref "REG-IO0-H") (pin "12") (pinfunction "D3_12") (pintype "input"))
      (node (ref "REG-IO1-BUF") (pin "12") (pinfunction "B7_12") (pintype "bidirectional"))
      (node (ref "REG-IO1-H") (pin "12") (pinfunction "D3_12") (pintype "input"))
      (node (ref "REG-IO2-BUF") (pin "12") (pinfunction "B7_12") (pintype "bidirectional"))
      (node (ref "REG-IO2-H") (pin "12") (pinfunction "D3_12") (pintype "input"))
      (node (ref "REG-IO3-BUF") (pin "12") (pinfunction "B7_12") (pintype "bidirectional"))
      (node (ref "REG-IO3-H") (pin "12") (pinfunction "D3_12") (pintype "input"))
      (node (ref "REG-IR-H") (pin "12") (pinfunction "D3_12") (pintype "input"))
      (node (ref "REG-MAR-BUF") (pin "12") (pinfunction "B7_12") (pintype "bidirectional"))
      (node (ref "REG-MAR-H") (pin "12") (pinfunction "D3_12") (pintype "input"))
      (node (ref "REG-MBR-BUF0") (pin "12") (pinfunction "B7_12") (pintype "bidirectional"))
      (node (ref "REG-MBR-H") (pin "12") (pinfunction "D3_12") (pintype "input"))
    )
    (net (code "269") (name "DATA-BUS7") (class "Default")
      (node (ref "74LS161N-1") (pin "6") (pinfunction "D_6") (pintype "input"))
      (node (ref "74LS161N-2") (pin "6") (pinfunction "D_6") (pintype "input"))
      (node (ref "ALU-BUF") (pin "11") (pinfunction "B8_11") (pintype "bidirectional"))
      (node (ref "DATA-R/P-SW-1") (pin "12") (pinfunction "4Y_12") (pintype "output"))
      (node (ref "DATA-R/P-SW-1") (pin "14") (pinfunction "4A_14") (pintype "input"))
      (node (ref "MEM-BUF") (pin "11") (pinfunction "B8_11") (pintype "bidirectional"))
      (node (ref "PAGE-ADDR-REG-0") (pin "11") (pinfunction "D4_11") (pintype "input"))
      (node (ref "PAGE-ADDR-REG-0") (pin "6") (pinfunction "Q4_6") (pintype "tri_state"))
      (node (ref "PC-BUF-H") (pin "15") (pinfunction "B4_15") (pintype "bidirectional"))
      (node (ref "PC-BUF-L") (pin "11") (pinfunction "B8_11") (pintype "bidirectional"))
      (node (ref "REG-ACU-BUF0") (pin "11") (pinfunction "B8_11") (pintype "bidirectional"))
      (node (ref "REG-ACU-H") (pin "11") (pinfunction "D4_11") (pintype "input"))
      (node (ref "REG-IO0-BUF") (pin "11") (pinfunction "B8_11") (pintype "bidirectional"))
      (node (ref "REG-IO0-H") (pin "11") (pinfunction "D4_11") (pintype "input"))
      (node (ref "REG-IO1-BUF") (pin "11") (pinfunction "B8_11") (pintype "bidirectional"))
      (node (ref "REG-IO1-H") (pin "11") (pinfunction "D4_11") (pintype "input"))
      (node (ref "REG-IO2-BUF") (pin "11") (pinfunction "B8_11") (pintype "bidirectional"))
      (node (ref "REG-IO2-H") (pin "11") (pinfunction "D4_11") (pintype "input"))
      (node (ref "REG-IO3-BUF") (pin "11") (pinfunction "B8_11") (pintype "bidirectional"))
      (node (ref "REG-IO3-H") (pin "11") (pinfunction "D4_11") (pintype "input"))
      (node (ref "REG-IR-H") (pin "11") (pinfunction "D4_11") (pintype "input"))
      (node (ref "REG-MAR-BUF") (pin "11") (pinfunction "B8_11") (pintype "bidirectional"))
      (node (ref "REG-MAR-H") (pin "11") (pinfunction "D4_11") (pintype "input"))
      (node (ref "REG-MBR-BUF0") (pin "11") (pinfunction "B8_11") (pintype "bidirectional"))
      (node (ref "REG-MBR-H") (pin "11") (pinfunction "D4_11") (pintype "input"))
    )
    (net (code "270") (name "DATA-IR0") (class "Default")
      (node (ref "REG-IR-BUF") (pin "14") (pinfunction "B5_14") (pintype "bidirectional"))
    )
    (net (code "271") (name "DATA-IR1") (class "Default")
      (node (ref "REG-IR-BUF") (pin "13") (pinfunction "B6_13") (pintype "bidirectional"))
    )
    (net (code "272") (name "DATA-IR2") (class "Default")
      (node (ref "REG-IR-BUF") (pin "12") (pinfunction "B7_12") (pintype "bidirectional"))
    )
    (net (code "273") (name "DATA-IR3") (class "Default")
      (node (ref "REG-IR-BUF") (pin "11") (pinfunction "B8_11") (pintype "bidirectional"))
    )
    (net (code "274") (name "DISP-CLK") (class "Default")
      (node (ref "JK-FLIP-FLOP") (pin "1") (pinfunction "CLK_1") (pintype "input"))
      (node (ref "SEG-SWITCH") (pin "3") (pinfunction "Q_3") (pintype "output"))
    )
    (net (code "275") (name "DISP-DATA-IN0") (class "Default")
      (node (ref "EEPROM-AT28C16") (pin "8") (pinfunction "A0_8") (pintype "input"))
    )
    (net (code "276") (name "DISP-DATA-IN1") (class "Default")
      (node (ref "EEPROM-AT28C16") (pin "7") (pinfunction "A1_7") (pintype "input"))
    )
    (net (code "277") (name "DISP-DATA-IN2") (class "Default")
      (node (ref "EEPROM-AT28C16") (pin "6") (pinfunction "A2_6") (pintype "input"))
    )
    (net (code "278") (name "DISP-DATA-IN3") (class "Default")
      (node (ref "EEPROM-AT28C16") (pin "5") (pinfunction "A3_5") (pintype "input"))
    )
    (net (code "279") (name "DISP-DATA-IN4") (class "Default")
      (node (ref "EEPROM-AT28C16") (pin "4") (pinfunction "A4_4") (pintype "input"))
    )
    (net (code "280") (name "DISP-DATA-IN5") (class "Default")
      (node (ref "EEPROM-AT28C16") (pin "3") (pinfunction "A5_3") (pintype "input"))
    )
    (net (code "281") (name "DISP-DATA-IN6") (class "Default")
      (node (ref "EEPROM-AT28C16") (pin "2") (pinfunction "A6_2") (pintype "input"))
    )
    (net (code "282") (name "DISP-DATA-IN7") (class "Default")
      (node (ref "EEPROM-AT28C16") (pin "1") (pinfunction "A7_1") (pintype "input"))
    )
    (net (code "283") (name "DISP-FF-OUT0") (class "Default")
      (node (ref "EEPROM-AT28C16") (pin "23") (pinfunction "A8_23") (pintype "input"))
      (node (ref "IC12") (pin "2") (pinfunction "A_2") (pintype "input"))
      (node (ref "JK-FLIP-FLOP") (pin "15") (pinfunction "Q_15") (pintype "output"))
      (node (ref "JK-FLIP-FLOP") (pin "6") (pinfunction "CLK_6") (pintype "input"))
    )
    (net (code "284") (name "DISP-FF-OUT1") (class "Default")
      (node (ref "EEPROM-AT28C16") (pin "22") (pinfunction "A9_22") (pintype "input"))
      (node (ref "IC12") (pin "3") (pinfunction "B_3") (pintype "input"))
      (node (ref "JK-FLIP-FLOP") (pin "11") (pinfunction "Q_11") (pintype "output"))
    )
    (net (code "285") (name "DISP-NEG-SWITCH") (class "Default")
      (node (ref "EEPROM-AT28C16") (pin "19") (pinfunction "A10_19") (pintype "input"))
    )
    (net (code "286") (name "DISP-TRIG") (class "Default")
      (node (ref "C4") (pin "2") (pinfunction "2_2") (pintype "passive"))
      (node (ref "R8") (pin "2") (pinfunction "2_2") (pintype "passive"))
      (node (ref "R9") (pin "2") (pinfunction "2_2") (pintype "passive"))
      (node (ref "SEG-SWITCH") (pin "2") (pinfunction "TR_2") (pintype "input"))
      (node (ref "SEG-SWITCH") (pin "6") (pinfunction "THR_6") (pintype "input"))
    )
    (net (code "287") (name "FLAG-I") (class "Default")
      (node (ref "AT28C16-3") (pin "15") (pinfunction "D5_15") (pintype "bidirectional"))
    )
    (net (code "288") (name "GND") (class "Default")
      (node (ref "74LS161N") (pin "15") (pinfunction "RCO_15") (pintype "output"))
      (node (ref "74LS161N") (pin "3") (pinfunction "A_3") (pintype "input"))
      (node (ref "74LS161N") (pin "4") (pinfunction "B_4") (pintype "input"))
      (node (ref "74LS161N") (pin "5") (pinfunction "C_5") (pintype "input"))
      (node (ref "74LS161N") (pin "6") (pinfunction "D_6") (pintype "input"))
      (node (ref "74LS161N-3") (pin "11") (pinfunction "QD_11") (pintype "output"))
      (node (ref "74LS161N-3") (pin "12") (pinfunction "QC_12") (pintype "output"))
      (node (ref "74LS161N-3") (pin "15") (pinfunction "RCO_15") (pintype "output"))
      (node (ref "74LS161N-3") (pin "4") (pinfunction "B_4") (pintype "input"))
      (node (ref "74LS161N-3") (pin "5") (pinfunction "C_5") (pintype "input"))
      (node (ref "74LS161N-3") (pin "6") (pinfunction "D_6") (pintype "input"))
      (node (ref "ADDR-R/P-SW-0") (pin "15") (pinfunction "G_15") (pintype "input"))
      (node (ref "ADDR-R/P-SW-1") (pin "15") (pinfunction "G_15") (pintype "input"))
      (node (ref "ADDR-R/P-SW-2") (pin "15") (pinfunction "G_15") (pintype "input"))
      (node (ref "ADDR-R/P-SW-3") (pin "10") (pinfunction "3B_10") (pintype "input"))
      (node (ref "ADDR-R/P-SW-3") (pin "11") (pinfunction "3A_11") (pintype "input"))
      (node (ref "ADDR-R/P-SW-3") (pin "12") (pinfunction "4Y_12") (pintype "output"))
      (node (ref "ADDR-R/P-SW-3") (pin "13") (pinfunction "4B_13") (pintype "input"))
      (node (ref "ADDR-R/P-SW-3") (pin "14") (pinfunction "4A_14") (pintype "input"))
      (node (ref "ADDR-R/P-SW-3") (pin "15") (pinfunction "G_15") (pintype "input"))
      (node (ref "ADDR-R/P-SW-3") (pin "5") (pinfunction "2A_5") (pintype "input"))
      (node (ref "ADDR-R/P-SW-3") (pin "6") (pinfunction "2B_6") (pintype "input"))
      (node (ref "ADDR-R/P-SW-3") (pin "7") (pinfunction "2Y_7") (pintype "output"))
      (node (ref "ADDR-R/P-SW-3") (pin "9") (pinfunction "3Y_9") (pintype "output"))
      (node (ref "AT28C16-0") (pin "18") (pinfunction "~{CE}_18") (pintype "input"))
      (node (ref "AT28C16-0") (pin "20") (pinfunction "~{OE}_20") (pintype "input"))
      (node (ref "AT28C16-1") (pin "18") (pinfunction "~{CE}_18") (pintype "input"))
      (node (ref "AT28C16-1") (pin "20") (pinfunction "~{OE}_20") (pintype "input"))
      (node (ref "AT28C16-2") (pin "18") (pinfunction "~{CE}_18") (pintype "input"))
      (node (ref "AT28C16-2") (pin "20") (pinfunction "~{OE}_20") (pintype "input"))
      (node (ref "AT28C16-3") (pin "16") (pinfunction "D6_16") (pintype "bidirectional"))
      (node (ref "AT28C16-3") (pin "17") (pinfunction "D7_17") (pintype "bidirectional"))
      (node (ref "AT28C16-3") (pin "18") (pinfunction "~{CE}_18") (pintype "input"))
      (node (ref "AT28C16-3") (pin "20") (pinfunction "~{OE}_20") (pintype "input"))
      (node (ref "C1") (pin "1") (pinfunction "1_1") (pintype "passive"))
      (node (ref "C2") (pin "-") (pinfunction "-_-") (pintype "passive"))
      (node (ref "C3") (pin "2") (pinfunction "2_2") (pintype "passive"))
      (node (ref "C4") (pin "1") (pinfunction "1_1") (pintype "passive"))
      (node (ref "CHIP-SELECT-REG-0") (pin "1") (pinfunction "M_1") (pintype "input"))
      (node (ref "CHIP-SELECT-REG-0") (pin "15") (pinfunction "CLR_15") (pintype "input"))
      (node (ref "CHIP-SELECT-REG-0") (pin "2") (pinfunction "N_2") (pintype "input"))
      (node (ref "CHIP-SELECT-REG-0") (pin "6") (pinfunction "Q4_6") (pintype "tri_state"))
      (node (ref "CLK") (pin "1") (pinfunction "GND_1") (pintype "power_in"))
      (node (ref "CLK") (pin "4") (pinfunction "R_4") (pintype "input"))
      (node (ref "DATA-R/P-SW-0") (pin "15") (pinfunction "G_15") (pintype "input"))
      (node (ref "DATA-R/P-SW-1") (pin "15") (pinfunction "G_15") (pintype "input"))
      (node (ref "DUAL-4X1-MUX-0") (pin "1") (pinfunction "1G_1") (pintype "input"))
      (node (ref "DUAL-4X1-MUX-0") (pin "15") (pinfunction "2G_15") (pintype "input"))
      (node (ref "DUAL-4X1-MUX-1") (pin "1") (pinfunction "1G_1") (pintype "input"))
      (node (ref "DUAL-4X1-MUX-1") (pin "15") (pinfunction "2G_15") (pintype "input"))
      (node (ref "DUAL-4X1-MUX-2") (pin "1") (pinfunction "1G_1") (pintype "input"))
      (node (ref "DUAL-4X1-MUX-2") (pin "15") (pinfunction "2G_15") (pintype "input"))
      (node (ref "DUAL-4X1-MUX-3") (pin "1") (pinfunction "1G_1") (pintype "input"))
      (node (ref "DUAL-4X1-MUX-3") (pin "15") (pinfunction "2G_15") (pintype "input"))
      (node (ref "EEPROM-AT28C16") (pin "18") (pinfunction "~{CE}_18") (pintype "input"))
      (node (ref "EEPROM-AT28C16") (pin "20") (pinfunction "~{OE}_20") (pintype "input"))
      (node (ref "IC11") (pin "13") (pinfunction "11_13") (pintype "output"))
      (node (ref "IC11") (pin "14") (pinfunction "12_14") (pintype "output"))
      (node (ref "IC11") (pin "15") (pinfunction "13_15") (pintype "output"))
      (node (ref "IC11") (pin "16") (pinfunction "14_16") (pintype "output"))
      (node (ref "IC11") (pin "17") (pinfunction "15_17") (pintype "output"))
      (node (ref "IC11") (pin "18") (pinfunction "G1_18") (pintype "input"))
      (node (ref "IC11") (pin "19") (pinfunction "G2_19") (pintype "input"))
      (node (ref "IC12") (pin "1") (pinfunction "G_1") (pintype "input"))
      (node (ref "JK-FLIP-FLOP") (pin "10") (pinfunction "~{Q}_10") (pintype "output"))
      (node (ref "JK-FLIP-FLOP") (pin "12") (pinfunction "K_12") (pintype "input"))
      (node (ref "JK-FLIP-FLOP") (pin "14") (pinfunction "~{Q}_14") (pintype "output"))
      (node (ref "LED0") (pin "K") (pinfunction "C_K") (pintype "passive"))
      (node (ref "LED10") (pin "K") (pinfunction "C_K") (pintype "passive"))
      (node (ref "LED11") (pin "K") (pinfunction "C_K") (pintype "passive"))
      (node (ref "LED12") (pin "K") (pinfunction "C_K") (pintype "passive"))
      (node (ref "LED13") (pin "K") (pinfunction "C_K") (pintype "passive"))
      (node (ref "LED14") (pin "K") (pinfunction "C_K") (pintype "passive"))
      (node (ref "LED15") (pin "K") (pinfunction "C_K") (pintype "passive"))
      (node (ref "LED16") (pin "K") (pinfunction "C_K") (pintype "passive"))
      (node (ref "LED17") (pin "K") (pinfunction "C_K") (pintype "passive"))
      (node (ref "LED18") (pin "K") (pinfunction "C_K") (pintype "passive"))
      (node (ref "LED19") (pin "K") (pinfunction "C_K") (pintype "passive"))
      (node (ref "LED2") (pin "K") (pinfunction "C_K") (pintype "passive"))
      (node (ref "LED20") (pin "K") (pinfunction "C_K") (pintype "passive"))
      (node (ref "LED21") (pin "K") (pinfunction "C_K") (pintype "passive"))
      (node (ref "LED22") (pin "K") (pinfunction "C_K") (pintype "passive"))
      (node (ref "LED23") (pin "K") (pinfunction "C_K") (pintype "passive"))
      (node (ref "LED24") (pin "K") (pinfunction "C_K") (pintype "passive"))
      (node (ref "LED25") (pin "K") (pinfunction "C_K") (pintype "passive"))
      (node (ref "LED26") (pin "K") (pinfunction "C_K") (pintype "passive"))
      (node (ref "LED27") (pin "K") (pinfunction "C_K") (pintype "passive"))
      (node (ref "LED28") (pin "K") (pinfunction "C_K") (pintype "passive"))
      (node (ref "LED29") (pin "K") (pinfunction "C_K") (pintype "passive"))
      (node (ref "LED3") (pin "K") (pinfunction "C_K") (pintype "passive"))
      (node (ref "LED30") (pin "K") (pinfunction "C_K") (pintype "passive"))
      (node (ref "LED31") (pin "K") (pinfunction "C_K") (pintype "passive"))
      (node (ref "LED32") (pin "K") (pinfunction "C_K") (pintype "passive"))
      (node (ref "LED33") (pin "K") (pinfunction "C_K") (pintype "passive"))
      (node (ref "LED34") (pin "K") (pinfunction "C_K") (pintype "passive"))
      (node (ref "LED35") (pin "K") (pinfunction "C_K") (pintype "passive"))
      (node (ref "LED36") (pin "K") (pinfunction "C_K") (pintype "passive"))
      (node (ref "LED37") (pin "K") (pinfunction "C_K") (pintype "passive"))
      (node (ref "LED38") (pin "K") (pinfunction "C_K") (pintype "passive"))
      (node (ref "LED39") (pin "K") (pinfunction "C_K") (pintype "passive"))
      (node (ref "LED4") (pin "K") (pinfunction "C_K") (pintype "passive"))
      (node (ref "LED40") (pin "K") (pinfunction "C_K") (pintype "passive"))
      (node (ref "LED41") (pin "K") (pinfunction "C_K") (pintype "passive"))
      (node (ref "LED42") (pin "K") (pinfunction "C_K") (pintype "passive"))
      (node (ref "LED43") (pin "K") (pinfunction "C_K") (pintype "passive"))
      (node (ref "LED44") (pin "K") (pinfunction "C_K") (pintype "passive"))
      (node (ref "LED45") (pin "K") (pinfunction "C_K") (pintype "passive"))
      (node (ref "LED46") (pin "K") (pinfunction "C_K") (pintype "passive"))
      (node (ref "LED47") (pin "K") (pinfunction "C_K") (pintype "passive"))
      (node (ref "LED48") (pin "K") (pinfunction "C_K") (pintype "passive"))
      (node (ref "LED49") (pin "K") (pinfunction "C_K") (pintype "passive"))
      (node (ref "LED5") (pin "K") (pinfunction "C_K") (pintype "passive"))
      (node (ref "LED50") (pin "K") (pinfunction "C_K") (pintype "passive"))
      (node (ref "LED51") (pin "K") (pinfunction "C_K") (pintype "passive"))
      (node (ref "LED52") (pin "K") (pinfunction "C_K") (pintype "passive"))
      (node (ref "LED53") (pin "K") (pinfunction "C_K") (pintype "passive"))
      (node (ref "LED54") (pin "K") (pinfunction "C_K") (pintype "passive"))
      (node (ref "LED55") (pin "K") (pinfunction "C_K") (pintype "passive"))
      (node (ref "LED56") (pin "K") (pinfunction "C_K") (pintype "passive"))
      (node (ref "LED57") (pin "K") (pinfunction "C_K") (pintype "passive"))
      (node (ref "LED58") (pin "K") (pinfunction "C_K") (pintype "passive"))
      (node (ref "LED59") (pin "K") (pinfunction "C_K") (pintype "passive"))
      (node (ref "LED6") (pin "K") (pinfunction "C_K") (pintype "passive"))
      (node (ref "LED60") (pin "K") (pinfunction "C_K") (pintype "passive"))
      (node (ref "LED61") (pin "K") (pinfunction "C_K") (pintype "passive"))
      (node (ref "LED62") (pin "K") (pinfunction "C_K") (pintype "passive"))
      (node (ref "LED63") (pin "K") (pinfunction "C_K") (pintype "passive"))
      (node (ref "LED64") (pin "K") (pinfunction "C_K") (pintype "passive"))
      (node (ref "LED65") (pin "K") (pinfunction "C_K") (pintype "passive"))
      (node (ref "LED66") (pin "K") (pinfunction "C_K") (pintype "passive"))
      (node (ref "LED67") (pin "K") (pinfunction "C_K") (pintype "passive"))
      (node (ref "LED68") (pin "K") (pinfunction "C_K") (pintype "passive"))
      (node (ref "LED69") (pin "K") (pinfunction "C_K") (pintype "passive"))
      (node (ref "LED7") (pin "K") (pinfunction "C_K") (pintype "passive"))
      (node (ref "LED70") (pin "K") (pinfunction "C_K") (pintype "passive"))
      (node (ref "LED71") (pin "K") (pinfunction "C_K") (pintype "passive"))
      (node (ref "LED72") (pin "K") (pinfunction "C_K") (pintype "passive"))
      (node (ref "LED73") (pin "K") (pinfunction "C_K") (pintype "passive"))
      (node (ref "LED74") (pin "K") (pinfunction "C_K") (pintype "passive"))
      (node (ref "LED75") (pin "K") (pinfunction "C_K") (pintype "passive"))
      (node (ref "LED76") (pin "K") (pinfunction "C_K") (pintype "passive"))
      (node (ref "LED77") (pin "K") (pinfunction "C_K") (pintype "passive"))
      (node (ref "LED78") (pin "K") (pinfunction "C_K") (pintype "passive"))
      (node (ref "LED79") (pin "K") (pinfunction "C_K") (pintype "passive"))
      (node (ref "LED8") (pin "K") (pinfunction "C_K") (pintype "passive"))
      (node (ref "LED80") (pin "K") (pinfunction "C_K") (pintype "passive"))
      (node (ref "LED81") (pin "K") (pinfunction "C_K") (pintype "passive"))
      (node (ref "LED82") (pin "K") (pinfunction "C_K") (pintype "passive"))
      (node (ref "LED83") (pin "K") (pinfunction "C_K") (pintype "passive"))
      (node (ref "LED84") (pin "K") (pinfunction "C_K") (pintype "passive"))
      (node (ref "LED85") (pin "K") (pinfunction "C_K") (pintype "passive"))
      (node (ref "LED86") (pin "K") (pinfunction "C_K") (pintype "passive"))
      (node (ref "LED87") (pin "K") (pinfunction "C_K") (pintype "passive"))
      (node (ref "LED88") (pin "K") (pinfunction "C_K") (pintype "passive"))
      (node (ref "LED89") (pin "K") (pinfunction "C_K") (pintype "passive"))
      (node (ref "LED9") (pin "K") (pinfunction "C_K") (pintype "passive"))
      (node (ref "LED90") (pin "K") (pinfunction "C_K") (pintype "passive"))
      (node (ref "LED91") (pin "K") (pinfunction "C_K") (pintype "passive"))
      (node (ref "LED92") (pin "K") (pinfunction "C_K") (pintype "passive"))
      (node (ref "LED93") (pin "K") (pinfunction "C_K") (pintype "passive"))
      (node (ref "LED94") (pin "K") (pinfunction "C_K") (pintype "passive"))
      (node (ref "LED95") (pin "K") (pinfunction "C_K") (pintype "passive"))
      (node (ref "LED96") (pin "K") (pinfunction "C_K") (pintype "passive"))
      (node (ref "LED97") (pin "K") (pinfunction "C_K") (pintype "passive"))
      (node (ref "LED98") (pin "K") (pinfunction "C_K") (pintype "passive"))
      (node (ref "LED99") (pin "K") (pinfunction "C_K") (pintype "passive"))
      (node (ref "MEM-INT-BUF-0") (pin "19") (pinfunction "G_19") (pintype "input"))
      (node (ref "MEM-INT-BUF-1") (pin "19") (pinfunction "G_19") (pintype "input"))
      (node (ref "MEM-INT-BUF-2") (pin "11") (pinfunction "B8_11") (pintype "bidirectional"))
      (node (ref "MEM-INT-BUF-2") (pin "12") (pinfunction "B7_12") (pintype "bidirectional"))
      (node (ref "MEM-INT-BUF-2") (pin "13") (pinfunction "B6_13") (pintype "bidirectional"))
      (node (ref "MEM-INT-BUF-2") (pin "14") (pinfunction "B5_14") (pintype "bidirectional"))
      (node (ref "MEM-INT-BUF-2") (pin "15") (pinfunction "B4_15") (pintype "bidirectional"))
      (node (ref "MEM-INT-BUF-2") (pin "16") (pinfunction "B3_16") (pintype "bidirectional"))
      (node (ref "MEM-INT-BUF-2") (pin "17") (pinfunction "B2_17") (pintype "bidirectional"))
      (node (ref "MEM-INT-BUF-2") (pin "19") (pinfunction "G_19") (pintype "input"))
      (node (ref "MEM-INT-BUF-2") (pin "3") (pinfunction "A2_3") (pintype "bidirectional"))
      (node (ref "MEM-INT-BUF-2") (pin "4") (pinfunction "A3_4") (pintype "bidirectional"))
      (node (ref "MEM-INT-BUF-2") (pin "5") (pinfunction "A4_5") (pintype "bidirectional"))
      (node (ref "MEM-INT-BUF-2") (pin "6") (pinfunction "A5_6") (pintype "bidirectional"))
      (node (ref "MEM-INT-BUF-2") (pin "7") (pinfunction "A6_7") (pintype "bidirectional"))
      (node (ref "MEM-INT-BUF-2") (pin "8") (pinfunction "A7_8") (pintype "bidirectional"))
      (node (ref "MEM-INT-BUF-2") (pin "9") (pinfunction "A8_9") (pintype "bidirectional"))
      (node (ref "MEMORY-0-8KX8-6264") (pin "14") (pinfunction "VSS_14") (pintype "power_in"))
      (node (ref "MEMORY-1-8KX8-6264") (pin "14") (pinfunction "VSS_14") (pintype "power_in"))
      (node (ref "MEMORY-2-8KX8-6264") (pin "14") (pinfunction "VSS_14") (pintype "power_in"))
      (node (ref "MEMORY-3-8KX8-6264") (pin "14") (pinfunction "VSS_14") (pintype "power_in"))
      (node (ref "PAGE-ADDR-REG-0") (pin "1") (pinfunction "M_1") (pintype "input"))
      (node (ref "PAGE-ADDR-REG-0") (pin "15") (pinfunction "CLR_15") (pintype "input"))
      (node (ref "PAGE-ADDR-REG-0") (pin "2") (pinfunction "N_2") (pintype "input"))
      (node (ref "PC-BUF-H") (pin "11") (pinfunction "B8_11") (pintype "bidirectional"))
      (node (ref "PC-BUF-H") (pin "12") (pinfunction "B7_12") (pintype "bidirectional"))
      (node (ref "PC-BUF-H") (pin "13") (pinfunction "B6_13") (pintype "bidirectional"))
      (node (ref "PC-BUF-H") (pin "14") (pinfunction "B5_14") (pintype "bidirectional"))
      (node (ref "PC-BUF-H") (pin "6") (pinfunction "A5_6") (pintype "bidirectional"))
      (node (ref "PC-BUF-H") (pin "7") (pinfunction "A6_7") (pintype "bidirectional"))
      (node (ref "PC-BUF-H") (pin "8") (pinfunction "A7_8") (pintype "bidirectional"))
      (node (ref "PC-BUF-H") (pin "9") (pinfunction "A8_9") (pintype "bidirectional"))
      (node (ref "PROG/RUN-ADDR-SW") (pin "13") (pinfunction "13_13") (pintype "passive"))
      (node (ref "PROG/RUN-ADDR-SW") (pin "14") (pinfunction "14_14") (pintype "passive"))
      (node (ref "PROG/RUN-ADDR-SW") (pin "15") (pinfunction "15_15") (pintype "passive"))
      (node (ref "PROG/RUN-ADDR-SW") (pin "16") (pinfunction "16_16") (pintype "passive"))
      (node (ref "PROG/RUN-ADDR-SW") (pin "17") (pinfunction "17_17") (pintype "passive"))
      (node (ref "PROG/RUN-ADDR-SW") (pin "18") (pinfunction "18_18") (pintype "passive"))
      (node (ref "PROG/RUN-ADDR-SW") (pin "19") (pinfunction "19_19") (pintype "passive"))
      (node (ref "PROG/RUN-ADDR-SW") (pin "20") (pinfunction "20_20") (pintype "passive"))
      (node (ref "PROG/RUN-ADDR-SW") (pin "21") (pinfunction "21_21") (pintype "passive"))
      (node (ref "PROG/RUN-ADDR-SW") (pin "22") (pinfunction "22_22") (pintype "passive"))
      (node (ref "PROG/RUN-ADDR-SW") (pin "23") (pinfunction "23_23") (pintype "passive"))
      (node (ref "PROG/RUN-ADDR-SW") (pin "24") (pinfunction "24_24") (pintype "passive"))
      (node (ref "PROG/RUN-DATA-SW") (pin "10") (pinfunction "10_10") (pintype "passive"))
      (node (ref "PROG/RUN-DATA-SW") (pin "11") (pinfunction "11_11") (pintype "passive"))
      (node (ref "PROG/RUN-DATA-SW") (pin "12") (pinfunction "12_12") (pintype "passive"))
      (node (ref "PROG/RUN-DATA-SW") (pin "13") (pinfunction "13_13") (pintype "passive"))
      (node (ref "PROG/RUN-DATA-SW") (pin "14") (pinfunction "14_14") (pintype "passive"))
      (node (ref "PROG/RUN-DATA-SW") (pin "15") (pinfunction "15_15") (pintype "passive"))
      (node (ref "PROG/RUN-DATA-SW") (pin "16") (pinfunction "16_16") (pintype "passive"))
      (node (ref "PROG/RUN-DATA-SW") (pin "9") (pinfunction "9_9") (pintype "passive"))
      (node (ref "R2") (pin "1") (pinfunction "A_1") (pintype "passive"))
      (node (ref "R4") (pin "1") (pinfunction "1_1") (pintype "passive"))
      (node (ref "REG-ACU-H") (pin "1") (pinfunction "M_1") (pintype "input"))
      (node (ref "REG-ACU-H") (pin "2") (pinfunction "N_2") (pintype "input"))
      (node (ref "REG-ACU-L") (pin "1") (pinfunction "M_1") (pintype "input"))
      (node (ref "REG-ACU-L") (pin "2") (pinfunction "N_2") (pintype "input"))
      (node (ref "REG-IO0-H") (pin "1") (pinfunction "M_1") (pintype "input"))
      (node (ref "REG-IO0-H") (pin "2") (pinfunction "N_2") (pintype "input"))
      (node (ref "REG-IO0-L") (pin "1") (pinfunction "M_1") (pintype "input"))
      (node (ref "REG-IO0-L") (pin "2") (pinfunction "N_2") (pintype "input"))
      (node (ref "REG-IO1-H") (pin "1") (pinfunction "M_1") (pintype "input"))
      (node (ref "REG-IO1-H") (pin "2") (pinfunction "N_2") (pintype "input"))
      (node (ref "REG-IO1-L") (pin "1") (pinfunction "M_1") (pintype "input"))
      (node (ref "REG-IO1-L") (pin "2") (pinfunction "N_2") (pintype "input"))
      (node (ref "REG-IO2-H") (pin "1") (pinfunction "M_1") (pintype "input"))
      (node (ref "REG-IO2-H") (pin "2") (pinfunction "N_2") (pintype "input"))
      (node (ref "REG-IO2-L") (pin "1") (pinfunction "M_1") (pintype "input"))
      (node (ref "REG-IO2-L") (pin "2") (pinfunction "N_2") (pintype "input"))
      (node (ref "REG-IO3-H") (pin "1") (pinfunction "M_1") (pintype "input"))
      (node (ref "REG-IO3-H") (pin "2") (pinfunction "N_2") (pintype "input"))
      (node (ref "REG-IO3-L") (pin "1") (pinfunction "M_1") (pintype "input"))
      (node (ref "REG-IO3-L") (pin "2") (pinfunction "N_2") (pintype "input"))
      (node (ref "REG-IR-H") (pin "1") (pinfunction "M_1") (pintype "input"))
      (node (ref "REG-IR-H") (pin "2") (pinfunction "N_2") (pintype "input"))
      (node (ref "REG-IR-L") (pin "1") (pinfunction "M_1") (pintype "input"))
      (node (ref "REG-IR-L") (pin "2") (pinfunction "N_2") (pintype "input"))
      (node (ref "REG-MAR-H") (pin "1") (pinfunction "M_1") (pintype "input"))
      (node (ref "REG-MAR-H") (pin "2") (pinfunction "N_2") (pintype "input"))
      (node (ref "REG-MAR-L") (pin "1") (pinfunction "M_1") (pintype "input"))
      (node (ref "REG-MAR-L") (pin "2") (pinfunction "N_2") (pintype "input"))
      (node (ref "REG-MBR-H") (pin "1") (pinfunction "M_1") (pintype "input"))
      (node (ref "REG-MBR-H") (pin "2") (pinfunction "N_2") (pintype "input"))
      (node (ref "REG-MBR-L") (pin "1") (pinfunction "M_1") (pintype "input"))
      (node (ref "REG-MBR-L") (pin "2") (pinfunction "N_2") (pintype "input"))
      (node (ref "S1") (pin "1") (pinfunction "S_1") (pintype "passive"))
      (node (ref "S2") (pin "2") (pinfunction "P_2") (pintype "passive"))
      (node (ref "S2") (pin "3") (pinfunction "O_3") (pintype "passive"))
      (node (ref "S3") (pin "2") (pinfunction "S1_2") (pintype "passive"))
      (node (ref "S3") (pin "4") (pinfunction "P1_4") (pintype "passive"))
      (node (ref "SEG-SWITCH") (pin "1") (pinfunction "GND_1") (pintype "power_in"))
      (node (ref "SW2") (pin "2") (pinfunction "2_2") (pintype "passive"))
      (node (ref "SW3") (pin "2") (pinfunction "2_2") (pintype "passive"))
    )
    (net (code "289") (name "HLT") (class "Default")
      (node (ref "AT28C16-1") (pin "14") (pinfunction "D4_14") (pintype "bidirectional"))
      (node (ref "Q2") (pin "S") (pinfunction "S_S") (pintype "passive"))
      (node (ref "R7") (pin "1") (pinfunction "1_1") (pintype "passive"))
    )
    (net (code "290") (name "IO0-I") (class "Default")
      (node (ref "AT28C16-2") (pin "10") (pinfunction "D1_10") (pintype "bidirectional"))
      (node (ref "REG-IO0-H") (pin "10") (pinfunction "G2_10") (pintype "input"))
      (node (ref "REG-IO0-H") (pin "9") (pinfunction "G1_9") (pintype "input"))
      (node (ref "REG-IO0-L") (pin "10") (pinfunction "G2_10") (pintype "input"))
      (node (ref "REG-IO0-L") (pin "9") (pinfunction "G1_9") (pintype "input"))
    )
    (net (code "291") (name "IO0-O") (class "Default")
      (node (ref "AT28C16-3") (pin "9") (pinfunction "D0_9") (pintype "bidirectional"))
      (node (ref "REG-IO0-BUF") (pin "19") (pinfunction "G_19") (pintype "input"))
    )
    (net (code "292") (name "IO1-I") (class "Default")
      (node (ref "AT28C16-2") (pin "11") (pinfunction "D2_11") (pintype "bidirectional"))
      (node (ref "REG-IO1-H") (pin "10") (pinfunction "G2_10") (pintype "input"))
      (node (ref "REG-IO1-H") (pin "9") (pinfunction "G1_9") (pintype "input"))
      (node (ref "REG-IO1-L") (pin "10") (pinfunction "G2_10") (pintype "input"))
      (node (ref "REG-IO1-L") (pin "9") (pinfunction "G1_9") (pintype "input"))
    )
    (net (code "293") (name "IO1-O") (class "Default")
      (node (ref "AT28C16-3") (pin "10") (pinfunction "D1_10") (pintype "bidirectional"))
      (node (ref "REG-IO1-BUF") (pin "19") (pinfunction "G_19") (pintype "input"))
    )
    (net (code "294") (name "IO2-I") (class "Default")
      (node (ref "AT28C16-2") (pin "13") (pinfunction "D3_13") (pintype "bidirectional"))
      (node (ref "REG-IO2-H") (pin "10") (pinfunction "G2_10") (pintype "input"))
      (node (ref "REG-IO2-H") (pin "9") (pinfunction "G1_9") (pintype "input"))
      (node (ref "REG-IO2-L") (pin "10") (pinfunction "G2_10") (pintype "input"))
      (node (ref "REG-IO2-L") (pin "9") (pinfunction "G1_9") (pintype "input"))
    )
    (net (code "295") (name "IO2-O") (class "Default")
      (node (ref "AT28C16-3") (pin "11") (pinfunction "D2_11") (pintype "bidirectional"))
      (node (ref "REG-IO2-BUF") (pin "19") (pinfunction "G_19") (pintype "input"))
    )
    (net (code "296") (name "IO3-I") (class "Default")
      (node (ref "REG-IO3-H") (pin "10") (pinfunction "G2_10") (pintype "input"))
      (node (ref "REG-IO3-H") (pin "9") (pinfunction "G1_9") (pintype "input"))
      (node (ref "REG-IO3-L") (pin "10") (pinfunction "G2_10") (pintype "input"))
      (node (ref "REG-IO3-L") (pin "9") (pinfunction "G1_9") (pintype "input"))
    )
    (net (code "297") (name "IO3-O") (class "Default")
      (node (ref "REG-IO3-BUF") (pin "19") (pinfunction "G_19") (pintype "input"))
    )
    (net (code "298") (name "IR-I") (class "Default")
      (node (ref "AT28C16-1") (pin "17") (pinfunction "D7_17") (pintype "bidirectional"))
      (node (ref "REG-IR-H") (pin "10") (pinfunction "G2_10") (pintype "input"))
      (node (ref "REG-IR-H") (pin "9") (pinfunction "G1_9") (pintype "input"))
      (node (ref "REG-IR-L") (pin "10") (pinfunction "G2_10") (pintype "input"))
      (node (ref "REG-IR-L") (pin "9") (pinfunction "G1_9") (pintype "input"))
    )
    (net (code "299") (name "IR-O") (class "Default")
      (node (ref "AT28C16-2") (pin "16") (pinfunction "D6_16") (pintype "bidirectional"))
      (node (ref "REG-IR-BUF") (pin "19") (pinfunction "G_19") (pintype "input"))
    )
    (net (code "300") (name "MAR-I") (class "Default")
      (node (ref "AT28C16-1") (pin "16") (pinfunction "D6_16") (pintype "bidirectional"))
      (node (ref "REG-MAR-H") (pin "10") (pinfunction "G2_10") (pintype "input"))
      (node (ref "REG-MAR-H") (pin "9") (pinfunction "G1_9") (pintype "input"))
      (node (ref "REG-MAR-L") (pin "10") (pinfunction "G2_10") (pintype "input"))
      (node (ref "REG-MAR-L") (pin "9") (pinfunction "G1_9") (pintype "input"))
    )
    (net (code "301") (name "MAR-O") (class "Default")
      (node (ref "AT28C16-2") (pin "15") (pinfunction "D5_15") (pintype "bidirectional"))
      (node (ref "REG-MAR-BUF") (pin "19") (pinfunction "G_19") (pintype "input"))
    )
    (net (code "302") (name "MBR-DATA0") (class "Default")
      (node (ref "IC35") (pin "12") (pinfunction "I0_12") (pintype "input"))
      (node (ref "IC37") (pin "13") (pinfunction "I1_13") (pintype "input"))
      (node (ref "REG-MBR-BUF1") (pin "18") (pinfunction "B1_18") (pintype "bidirectional"))
    )
    (net (code "303") (name "MBR-DATA1") (class "Default")
      (node (ref "IC38") (pin "2") (pinfunction "I1_2") (pintype "input"))
      (node (ref "IC39") (pin "1") (pinfunction "I0_1") (pintype "input"))
      (node (ref "REG-MBR-BUF1") (pin "17") (pinfunction "B2_17") (pintype "bidirectional"))
    )
    (net (code "304") (name "MBR-DATA2") (class "Default")
      (node (ref "IC41") (pin "13") (pinfunction "I1_13") (pintype "input"))
      (node (ref "IC42") (pin "12") (pinfunction "I0_12") (pintype "input"))
      (node (ref "REG-MBR-BUF1") (pin "16") (pinfunction "B3_16") (pintype "bidirectional"))
    )
    (net (code "305") (name "MBR-DATA3") (class "Default")
      (node (ref "IC44") (pin "2") (pinfunction "I1_2") (pintype "input"))
      (node (ref "IC45") (pin "1") (pinfunction "I0_1") (pintype "input"))
      (node (ref "REG-MBR-BUF1") (pin "15") (pinfunction "B4_15") (pintype "bidirectional"))
    )
    (net (code "306") (name "MBR-DATA4") (class "Default")
      (node (ref "IC48") (pin "12") (pinfunction "I0_12") (pintype "input"))
      (node (ref "IC50") (pin "13") (pinfunction "I1_13") (pintype "input"))
      (node (ref "REG-MBR-BUF1") (pin "14") (pinfunction "B5_14") (pintype "bidirectional"))
    )
    (net (code "307") (name "MBR-DATA5") (class "Default")
      (node (ref "IC51") (pin "2") (pinfunction "I1_2") (pintype "input"))
      (node (ref "IC52") (pin "1") (pinfunction "I0_1") (pintype "input"))
      (node (ref "REG-MBR-BUF1") (pin "13") (pinfunction "B6_13") (pintype "bidirectional"))
    )
    (net (code "308") (name "MBR-DATA6") (class "Default")
      (node (ref "IC54") (pin "13") (pinfunction "I1_13") (pintype "input"))
      (node (ref "IC55") (pin "12") (pinfunction "I0_12") (pintype "input"))
      (node (ref "REG-MBR-BUF1") (pin "12") (pinfunction "B7_12") (pintype "bidirectional"))
    )
    (net (code "309") (name "MBR-DATA7") (class "Default")
      (node (ref "IC57") (pin "2") (pinfunction "I1_2") (pintype "input"))
      (node (ref "IC58") (pin "1") (pinfunction "I0_1") (pintype "input"))
      (node (ref "REG-MBR-BUF1") (pin "11") (pinfunction "B8_11") (pintype "bidirectional"))
    )
    (net (code "310") (name "MBR-I") (class "Default")
      (node (ref "AT28C16-2") (pin "9") (pinfunction "D0_9") (pintype "bidirectional"))
      (node (ref "REG-MBR-H") (pin "10") (pinfunction "G2_10") (pintype "input"))
      (node (ref "REG-MBR-H") (pin "9") (pinfunction "G1_9") (pintype "input"))
      (node (ref "REG-MBR-L") (pin "10") (pinfunction "G2_10") (pintype "input"))
      (node (ref "REG-MBR-L") (pin "9") (pinfunction "G1_9") (pintype "input"))
    )
    (net (code "311") (name "MBR-O") (class "Default")
      (node (ref "AT28C16-2") (pin "17") (pinfunction "D7_17") (pintype "bidirectional"))
      (node (ref "REG-MBR-BUF0") (pin "19") (pinfunction "G_19") (pintype "input"))
    )
    (net (code "312") (name "MRD") (class "Default")
      (node (ref "AT28C16-0") (pin "15") (pinfunction "D5_15") (pintype "bidirectional"))
      (node (ref "MEMORY-0-8KX8-6264") (pin "22") (pinfunction "~{OE}_22") (pintype "input"))
      (node (ref "MEMORY-1-8KX8-6264") (pin "22") (pinfunction "~{OE}_22") (pintype "input"))
      (node (ref "MEMORY-2-8KX8-6264") (pin "22") (pinfunction "~{OE}_22") (pintype "input"))
      (node (ref "MEMORY-3-8KX8-6264") (pin "22") (pinfunction "~{OE}_22") (pintype "input"))
    )
    (net (code "313") (name "MRQ") (class "Default")
      (node (ref "AT28C16-0") (pin "13") (pinfunction "D3_13") (pintype "bidirectional"))
      (node (ref "DEMUX-2X4-0") (pin "1") (pinfunction "G_1") (pintype "input"))
      (node (ref "MEM-BUF") (pin "19") (pinfunction "G_19") (pintype "input"))
    )
    (net (code "314") (name "MUX1-2C1-IN") (class "Default")
      (node (ref "IC45") (pin "3") (pinfunction "O_3") (pintype "output"))
    )
    (net (code "315") (name "MUX1-2C2-IN") (class "Default")
      (node (ref "IC4") (pin "2") (pinfunction "O_2") (pintype "output"))
    )
    (net (code "316") (name "MUX1-2C3-IN") (class "Default")
      (node (ref "IC44") (pin "3") (pinfunction "O_3") (pintype "output"))
    )
    (net (code "317") (name "MWR") (class "Default")
      (node (ref "AT28C16-0") (pin "14") (pinfunction "D4_14") (pintype "bidirectional"))
      (node (ref "MEM-BUF") (pin "1") (pinfunction "DIR_1") (pintype "input"))
      (node (ref "MEMORY-0-8KX8-6264") (pin "27") (pinfunction "~{WE}_27") (pintype "input"))
      (node (ref "MEMORY-1-8KX8-6264") (pin "27") (pinfunction "~{WE}_27") (pintype "input"))
      (node (ref "MEMORY-2-8KX8-6264") (pin "27") (pinfunction "~{WE}_27") (pintype "input"))
      (node (ref "MEMORY-3-8KX8-6264") (pin "27") (pinfunction "~{WE}_27") (pintype "input"))
    )
    (net (code "318") (name "Net-(4BIT-FULL-ADDER-2A-C4)") (class "Default")
      (node (ref "4BIT-FULL-ADDER-2") (pin "9") (pinfunction "C4_9") (pintype "output"))
      (node (ref "4BIT-FULL-ADDER-3") (pin "7") (pinfunction "C0_7") (pintype "input"))
    )
    (net (code "319") (name "Net-(74LS161N-3A-QB)") (class "Default")
      (node (ref "74LS161N-3") (pin "13") (pinfunction "QB_13") (pintype "output"))
      (node (ref "RST-INVERTER") (pin "1") (pinfunction "I_1") (pintype "input"))
    )
    (net (code "320") (name "Net-(CLK-CV)") (class "Default")
      (node (ref "C1") (pin "2") (pinfunction "2_2") (pintype "passive"))
      (node (ref "CLK") (pin "5") (pinfunction "CV_5") (pintype "input"))
    )
    (net (code "321") (name "Net-(CLK-Q)") (class "Default")
      (node (ref "CLK") (pin "3") (pinfunction "Q_3") (pintype "output"))
      (node (ref "Q2") (pin "G") (pinfunction "G_G") (pintype "passive"))
      (node (ref "R7") (pin "2") (pinfunction "2_2") (pintype "passive"))
    )
    (net (code "322") (name "Net-(CLK-V+)") (class "Default")
      (node (ref "CLK") (pin "8") (pinfunction "V+_8") (pintype "power_in"))
      (node (ref "Q1") (pin "E") (pinfunction "E_E") (pintype "passive"))
      (node (ref "R1") (pin "1") (pinfunction "1_1") (pintype "passive"))
    )
    (net (code "323") (name "Net-(IC9A-I0)") (class "Default")
      (node (ref "IC9") (pin "1") (pinfunction "I0_1") (pintype "input"))
      (node (ref "IC9") (pin "2") (pinfunction "I1_2") (pintype "input"))
      (node (ref "R4") (pin "2") (pinfunction "2_2") (pintype "passive"))
      (node (ref "S3") (pin "1") (pinfunction "S_1") (pintype "passive"))
    )
    (net (code "324") (name "Net-(IC9C-O)") (class "Default")
      (node (ref "IC9") (pin "12") (pinfunction "I0_12") (pintype "input"))
      (node (ref "IC9") (pin "13") (pinfunction "I1_13") (pintype "input"))
      (node (ref "IC9") (pin "8") (pinfunction "O_8") (pintype "output"))
    )
    (net (code "325") (name "Net-(IC11A-0)") (class "Default")
      (node (ref "IC11") (pin "1") (pinfunction "0_1") (pintype "output"))
      (node (ref "LED90") (pin "A") (pinfunction "A_A") (pintype "passive"))
    )
    (net (code "326") (name "Net-(IC11A-1)") (class "Default")
      (node (ref "IC11") (pin "2") (pinfunction "1_2") (pintype "output"))
      (node (ref "LED91") (pin "A") (pinfunction "A_A") (pintype "passive"))
    )
    (net (code "327") (name "Net-(IC11A-2)") (class "Default")
      (node (ref "IC11") (pin "3") (pinfunction "2_3") (pintype "output"))
      (node (ref "LED92") (pin "A") (pinfunction "A_A") (pintype "passive"))
    )
    (net (code "328") (name "Net-(IC11A-3)") (class "Default")
      (node (ref "IC11") (pin "4") (pinfunction "3_4") (pintype "output"))
      (node (ref "LED93") (pin "A") (pinfunction "A_A") (pintype "passive"))
    )
    (net (code "329") (name "Net-(IC11A-4)") (class "Default")
      (node (ref "IC11") (pin "5") (pinfunction "4_5") (pintype "output"))
      (node (ref "LED94") (pin "A") (pinfunction "A_A") (pintype "passive"))
    )
    (net (code "330") (name "Net-(IC11A-5)") (class "Default")
      (node (ref "IC11") (pin "6") (pinfunction "5_6") (pintype "output"))
      (node (ref "LED95") (pin "A") (pinfunction "A_A") (pintype "passive"))
    )
    (net (code "331") (name "Net-(IC11A-6)") (class "Default")
      (node (ref "IC11") (pin "7") (pinfunction "6_7") (pintype "output"))
      (node (ref "LED96") (pin "A") (pinfunction "A_A") (pintype "passive"))
    )
    (net (code "332") (name "Net-(IC11A-7)") (class "Default")
      (node (ref "IC11") (pin "8") (pinfunction "7_8") (pintype "output"))
      (node (ref "LED97") (pin "A") (pinfunction "A_A") (pintype "passive"))
    )
    (net (code "333") (name "Net-(IC11A-8)") (class "Default")
      (node (ref "IC11") (pin "9") (pinfunction "8_9") (pintype "output"))
      (node (ref "LED98") (pin "A") (pinfunction "A_A") (pintype "passive"))
    )
    (net (code "334") (name "Net-(IC11A-9)") (class "Default")
      (node (ref "IC11") (pin "10") (pinfunction "9_10") (pintype "output"))
      (node (ref "LED99") (pin "A") (pinfunction "A_A") (pintype "passive"))
    )
    (net (code "335") (name "Net-(LED1-PadA)") (class "Default")
      (node (ref "LED1") (pin "A") (pinfunction "A_A") (pintype "passive"))
      (node (ref "Q2") (pin "D") (pinfunction "D_D") (pintype "passive"))
    )
    (net (code "336") (name "Net-(R2-E)") (class "Default")
      (node (ref "R2") (pin "3") (pinfunction "E_3") (pintype "passive"))
      (node (ref "R3") (pin "2") (pinfunction "2_2") (pintype "passive"))
    )
    (net (code "337") (name "Net-(S1-P)") (class "Default")
      (node (ref "R5") (pin "1") (pinfunction "1_1") (pintype "passive"))
      (node (ref "S1") (pin "3") (pinfunction "P_3") (pintype "passive"))
    )
    (net (code "338") (name "Net-(SEG-SWITCH-CV)") (class "Default")
      (node (ref "C3") (pin "1") (pinfunction "1_1") (pintype "passive"))
      (node (ref "SEG-SWITCH") (pin "5") (pinfunction "CV_5") (pintype "input"))
    )
    (net (code "339") (name "Net-(SEG-SWITCH-DIS)") (class "Default")
      (node (ref "R8") (pin "1") (pinfunction "1_1") (pintype "passive"))
      (node (ref "SEG-SWITCH") (pin "7") (pinfunction "DIS_7") (pintype "input"))
    )
    (net (code "340") (name "PC-EN") (class "Default")
      (node (ref "74LS161N-0") (pin "10") (pinfunction "ENT_10") (pintype "input"))
      (node (ref "74LS161N-0") (pin "7") (pinfunction "ENP_7") (pintype "input"))
      (node (ref "74LS161N-1") (pin "7") (pinfunction "ENP_7") (pintype "input"))
      (node (ref "74LS161N-2") (pin "7") (pinfunction "ENP_7") (pintype "input"))
      (node (ref "74LS161N-3") (pin "7") (pinfunction "ENP_7") (pintype "input"))
      (node (ref "AT28C16-0") (pin "16") (pinfunction "D6_16") (pintype "bidirectional"))
    )
    (net (code "341") (name "PC-I") (class "Default")
      (node (ref "AT28C16-0") (pin "17") (pinfunction "D7_17") (pintype "bidirectional"))
    )
    (net (code "342") (name "PCH-I") (class "Default")
      (node (ref "74LS161N-2") (pin "9") (pinfunction "LD_9") (pintype "input"))
      (node (ref "74LS161N-3") (pin "9") (pinfunction "LD_9") (pintype "input"))
    )
    (net (code "343") (name "PCH-O") (class "Default")
      (node (ref "AT28C16-0") (pin "10") (pinfunction "D1_10") (pintype "bidirectional"))
      (node (ref "PC-BUF-H") (pin "19") (pinfunction "G_19") (pintype "input"))
    )
    (net (code "344") (name "PCL-I") (class "Default")
      (node (ref "74LS161N-0") (pin "9") (pinfunction "LD_9") (pintype "input"))
      (node (ref "74LS161N-1") (pin "9") (pinfunction "LD_9") (pintype "input"))
      (node (ref "AT28C16-3") (pin "13") (pinfunction "D3_13") (pintype "bidirectional"))
    )
    (net (code "345") (name "PCL-O") (class "Default")
      (node (ref "AT28C16-0") (pin "9") (pinfunction "D0_9") (pintype "bidirectional"))
      (node (ref "PC-BUF-L") (pin "19") (pinfunction "G_19") (pintype "input"))
    )
    (net (code "346") (name "PR-I") (class "Default")
      (node (ref "AT28C16-0") (pin "11") (pinfunction "D2_11") (pintype "bidirectional"))
      (node (ref "PAGE-ADDR-REG-0") (pin "10") (pinfunction "G2_10") (pintype "input"))
      (node (ref "PAGE-ADDR-REG-0") (pin "9") (pinfunction "G1_9") (pintype "input"))
    )
    (net (code "347") (name "PROG{slash}BUS-SW") (class "Default")
      (node (ref "ADDR-R/P-SW-0") (pin "1") (pinfunction "~{A}/B_1") (pintype "input"))
      (node (ref "ADDR-R/P-SW-1") (pin "1") (pinfunction "~{A}/B_1") (pintype "input"))
      (node (ref "ADDR-R/P-SW-2") (pin "1") (pinfunction "~{A}/B_1") (pintype "input"))
      (node (ref "ADDR-R/P-SW-3") (pin "1") (pinfunction "~{A}/B_1") (pintype "input"))
      (node (ref "DATA-R/P-SW-0") (pin "1") (pinfunction "~{A}/B_1") (pintype "input"))
      (node (ref "DATA-R/P-SW-1") (pin "1") (pinfunction "~{A}/B_1") (pintype "input"))
      (node (ref "SW2") (pin "1") (pinfunction "1_1") (pintype "passive"))
    )
    (net (code "348") (name "REG-ACU-DATA0") (class "Default")
      (node (ref "4BIT-FULL-ADDER-2") (pin "5") (pinfunction "A1_5") (pintype "input"))
      (node (ref "LED0") (pin "A") (pinfunction "A_A") (pintype "passive"))
      (node (ref "REG-ACU-BUF0") (pin "2") (pinfunction "A1_2") (pintype "bidirectional"))
      (node (ref "REG-ACU-BUF1") (pin "2") (pinfunction "A1_2") (pintype "bidirectional"))
      (node (ref "REG-ACU-L") (pin "3") (pinfunction "Q1_3") (pintype "tri_state"))
    )
    (net (code "349") (name "REG-ACU-DATA1") (class "Default")
      (node (ref "4BIT-FULL-ADDER-2") (pin "3") (pinfunction "A2_3") (pintype "input"))
      (node (ref "LED33") (pin "A") (pinfunction "A_A") (pintype "passive"))
      (node (ref "REG-ACU-BUF0") (pin "3") (pinfunction "A2_3") (pintype "bidirectional"))
      (node (ref "REG-ACU-BUF1") (pin "3") (pinfunction "A2_3") (pintype "bidirectional"))
      (node (ref "REG-ACU-L") (pin "4") (pinfunction "Q2_4") (pintype "tri_state"))
    )
    (net (code "350") (name "REG-ACU-DATA2") (class "Default")
      (node (ref "4BIT-FULL-ADDER-2") (pin "14") (pinfunction "A3_14") (pintype "input"))
      (node (ref "LED32") (pin "A") (pinfunction "A_A") (pintype "passive"))
      (node (ref "REG-ACU-BUF0") (pin "4") (pinfunction "A3_4") (pintype "bidirectional"))
      (node (ref "REG-ACU-BUF1") (pin "4") (pinfunction "A3_4") (pintype "bidirectional"))
      (node (ref "REG-ACU-L") (pin "5") (pinfunction "Q3_5") (pintype "tri_state"))
    )
    (net (code "351") (name "REG-ACU-DATA3") (class "Default")
      (node (ref "4BIT-FULL-ADDER-2") (pin "12") (pinfunction "A4_12") (pintype "input"))
      (node (ref "LED31") (pin "A") (pinfunction "A_A") (pintype "passive"))
      (node (ref "REG-ACU-BUF0") (pin "5") (pinfunction "A4_5") (pintype "bidirectional"))
      (node (ref "REG-ACU-BUF1") (pin "5") (pinfunction "A4_5") (pintype "bidirectional"))
      (node (ref "REG-ACU-L") (pin "6") (pinfunction "Q4_6") (pintype "tri_state"))
    )
    (net (code "352") (name "REG-ACU-DATA4") (class "Default")
      (node (ref "4BIT-FULL-ADDER-3") (pin "5") (pinfunction "A1_5") (pintype "input"))
      (node (ref "LED30") (pin "A") (pinfunction "A_A") (pintype "passive"))
      (node (ref "REG-ACU-BUF0") (pin "6") (pinfunction "A5_6") (pintype "bidirectional"))
      (node (ref "REG-ACU-BUF1") (pin "6") (pinfunction "A5_6") (pintype "bidirectional"))
      (node (ref "REG-ACU-H") (pin "3") (pinfunction "Q1_3") (pintype "tri_state"))
    )
    (net (code "353") (name "REG-ACU-DATA5") (class "Default")
      (node (ref "4BIT-FULL-ADDER-3") (pin "3") (pinfunction "A2_3") (pintype "input"))
      (node (ref "LED29") (pin "A") (pinfunction "A_A") (pintype "passive"))
      (node (ref "REG-ACU-BUF0") (pin "7") (pinfunction "A6_7") (pintype "bidirectional"))
      (node (ref "REG-ACU-BUF1") (pin "7") (pinfunction "A6_7") (pintype "bidirectional"))
      (node (ref "REG-ACU-H") (pin "4") (pinfunction "Q2_4") (pintype "tri_state"))
    )
    (net (code "354") (name "REG-ACU-DATA6") (class "Default")
      (node (ref "4BIT-FULL-ADDER-3") (pin "14") (pinfunction "A3_14") (pintype "input"))
      (node (ref "LED28") (pin "A") (pinfunction "A_A") (pintype "passive"))
      (node (ref "REG-ACU-BUF0") (pin "8") (pinfunction "A7_8") (pintype "bidirectional"))
      (node (ref "REG-ACU-BUF1") (pin "8") (pinfunction "A7_8") (pintype "bidirectional"))
      (node (ref "REG-ACU-H") (pin "5") (pinfunction "Q3_5") (pintype "tri_state"))
    )
    (net (code "355") (name "REG-ACU-DATA7") (class "Default")
      (node (ref "4BIT-FULL-ADDER-3") (pin "12") (pinfunction "A4_12") (pintype "input"))
      (node (ref "LED27") (pin "A") (pinfunction "A_A") (pintype "passive"))
      (node (ref "REG-ACU-BUF0") (pin "9") (pinfunction "A8_9") (pintype "bidirectional"))
      (node (ref "REG-ACU-BUF1") (pin "9") (pinfunction "A8_9") (pintype "bidirectional"))
      (node (ref "REG-ACU-H") (pin "6") (pinfunction "Q4_6") (pintype "tri_state"))
    )
    (net (code "356") (name "REG-MBR-DATA0") (class "Default")
      (node (ref "IC46") (pin "2") (pinfunction "I1_2") (pintype "input"))
      (node (ref "LED34") (pin "A") (pinfunction "A_A") (pintype "passive"))
      (node (ref "REG-MBR-BUF0") (pin "2") (pinfunction "A1_2") (pintype "bidirectional"))
      (node (ref "REG-MBR-BUF1") (pin "2") (pinfunction "A1_2") (pintype "bidirectional"))
      (node (ref "REG-MBR-L") (pin "3") (pinfunction "Q1_3") (pintype "tri_state"))
    )
    (net (code "357") (name "REG-MBR-DATA1") (class "Default")
      (node (ref "IC46") (pin "5") (pinfunction "I1_5") (pintype "input"))
      (node (ref "LED35") (pin "A") (pinfunction "A_A") (pintype "passive"))
      (node (ref "REG-MBR-BUF0") (pin "3") (pinfunction "A2_3") (pintype "bidirectional"))
      (node (ref "REG-MBR-BUF1") (pin "3") (pinfunction "A2_3") (pintype "bidirectional"))
      (node (ref "REG-MBR-L") (pin "4") (pinfunction "Q2_4") (pintype "tri_state"))
    )
    (net (code "358") (name "REG-MBR-DATA2") (class "Default")
      (node (ref "IC46") (pin "10") (pinfunction "I1_10") (pintype "input"))
      (node (ref "LED36") (pin "A") (pinfunction "A_A") (pintype "passive"))
      (node (ref "REG-MBR-BUF0") (pin "4") (pinfunction "A3_4") (pintype "bidirectional"))
      (node (ref "REG-MBR-BUF1") (pin "4") (pinfunction "A3_4") (pintype "bidirectional"))
      (node (ref "REG-MBR-L") (pin "5") (pinfunction "Q3_5") (pintype "tri_state"))
    )
    (net (code "359") (name "REG-MBR-DATA3") (class "Default")
      (node (ref "IC46") (pin "13") (pinfunction "I1_13") (pintype "input"))
      (node (ref "LED37") (pin "A") (pinfunction "A_A") (pintype "passive"))
      (node (ref "REG-MBR-BUF0") (pin "5") (pinfunction "A4_5") (pintype "bidirectional"))
      (node (ref "REG-MBR-BUF1") (pin "5") (pinfunction "A4_5") (pintype "bidirectional"))
      (node (ref "REG-MBR-L") (pin "6") (pinfunction "Q4_6") (pintype "tri_state"))
    )
    (net (code "360") (name "REG-MBR-DATA4") (class "Default")
      (node (ref "IC47") (pin "2") (pinfunction "I1_2") (pintype "input"))
      (node (ref "LED38") (pin "A") (pinfunction "A_A") (pintype "passive"))
      (node (ref "REG-MBR-BUF0") (pin "6") (pinfunction "A5_6") (pintype "bidirectional"))
      (node (ref "REG-MBR-BUF1") (pin "6") (pinfunction "A5_6") (pintype "bidirectional"))
      (node (ref "REG-MBR-H") (pin "3") (pinfunction "Q1_3") (pintype "tri_state"))
    )
    (net (code "361") (name "REG-MBR-DATA5") (class "Default")
      (node (ref "IC47") (pin "5") (pinfunction "I1_5") (pintype "input"))
      (node (ref "LED39") (pin "A") (pinfunction "A_A") (pintype "passive"))
      (node (ref "REG-MBR-BUF0") (pin "7") (pinfunction "A6_7") (pintype "bidirectional"))
      (node (ref "REG-MBR-BUF1") (pin "7") (pinfunction "A6_7") (pintype "bidirectional"))
      (node (ref "REG-MBR-H") (pin "4") (pinfunction "Q2_4") (pintype "tri_state"))
    )
    (net (code "362") (name "REG-MBR-DATA6") (class "Default")
      (node (ref "IC47") (pin "10") (pinfunction "I1_10") (pintype "input"))
      (node (ref "LED40") (pin "A") (pinfunction "A_A") (pintype "passive"))
      (node (ref "REG-MBR-BUF0") (pin "8") (pinfunction "A7_8") (pintype "bidirectional"))
      (node (ref "REG-MBR-BUF1") (pin "8") (pinfunction "A7_8") (pintype "bidirectional"))
      (node (ref "REG-MBR-H") (pin "5") (pinfunction "Q3_5") (pintype "tri_state"))
    )
    (net (code "363") (name "REG-MBR-DATA7") (class "Default")
      (node (ref "IC47") (pin "13") (pinfunction "I1_13") (pintype "input"))
      (node (ref "LED41") (pin "A") (pinfunction "A_A") (pintype "passive"))
      (node (ref "REG-MBR-BUF0") (pin "9") (pinfunction "A8_9") (pintype "bidirectional"))
      (node (ref "REG-MBR-BUF1") (pin "9") (pinfunction "A8_9") (pintype "bidirectional"))
      (node (ref "REG-MBR-H") (pin "6") (pinfunction "Q4_6") (pintype "tri_state"))
    )
    (net (code "364") (name "RST-H") (class "Default")
      (node (ref "IC9") (pin "6") (pinfunction "O_6") (pintype "output"))
      (node (ref "REG-ACU-H") (pin "15") (pinfunction "CLR_15") (pintype "input"))
      (node (ref "REG-ACU-L") (pin "15") (pinfunction "CLR_15") (pintype "input"))
      (node (ref "REG-IO0-H") (pin "15") (pinfunction "CLR_15") (pintype "input"))
      (node (ref "REG-IO0-L") (pin "15") (pinfunction "CLR_15") (pintype "input"))
      (node (ref "REG-IO1-H") (pin "15") (pinfunction "CLR_15") (pintype "input"))
      (node (ref "REG-IO1-L") (pin "15") (pinfunction "CLR_15") (pintype "input"))
      (node (ref "REG-IO2-H") (pin "15") (pinfunction "CLR_15") (pintype "input"))
      (node (ref "REG-IO2-L") (pin "15") (pinfunction "CLR_15") (pintype "input"))
      (node (ref "REG-IO3-H") (pin "15") (pinfunction "CLR_15") (pintype "input"))
      (node (ref "REG-IO3-L") (pin "15") (pinfunction "CLR_15") (pintype "input"))
      (node (ref "REG-IR-H") (pin "15") (pinfunction "CLR_15") (pintype "input"))
      (node (ref "REG-IR-L") (pin "15") (pinfunction "CLR_15") (pintype "input"))
      (node (ref "REG-MAR-H") (pin "15") (pinfunction "CLR_15") (pintype "input"))
      (node (ref "REG-MAR-L") (pin "15") (pinfunction "CLR_15") (pintype "input"))
      (node (ref "REG-MBR-H") (pin "15") (pinfunction "CLR_15") (pintype "input"))
      (node (ref "REG-MBR-L") (pin "15") (pinfunction "CLR_15") (pintype "input"))
    )
    (net (code "365") (name "RST-L") (class "Default")
      (node (ref "74LS161N-0") (pin "1") (pinfunction "CLR_1") (pintype "input"))
      (node (ref "74LS161N-1") (pin "1") (pinfunction "CLR_1") (pintype "input"))
      (node (ref "74LS161N-2") (pin "1") (pinfunction "CLR_1") (pintype "input"))
      (node (ref "74LS161N-3") (pin "1") (pinfunction "CLR_1") (pintype "input"))
      (node (ref "IC9") (pin "3") (pinfunction "O_3") (pintype "output"))
      (node (ref "IC9") (pin "4") (pinfunction "I0_4") (pintype "input"))
      (node (ref "IC9") (pin "5") (pinfunction "I1_5") (pintype "input"))
      (node (ref "IC9") (pin "9") (pinfunction "I0_9") (pintype "input"))
      (node (ref "RST-INVERTER") (pin "2") (pinfunction "O_2") (pintype "output"))
    )
    (net (code "366") (name "RST-USTEP") (class "Default")
      (node (ref "74LS161N") (pin "1") (pinfunction "CLR_1") (pintype "input"))
      (node (ref "IC11") (pin "11") (pinfunction "10_11") (pintype "output"))
      (node (ref "IC9") (pin "11") (pinfunction "O_11") (pintype "output"))
    )
    (net (code "367") (name "USTEP") (class "Default")
      (node (ref "IC9") (pin "10") (pinfunction "I1_10") (pintype "input"))
    )
    (net (code "368") (name "VCC") (class "Default")
      (node (ref "74LS161N") (pin "10") (pinfunction "ENT_10") (pintype "input"))
      (node (ref "74LS161N") (pin "7") (pinfunction "ENP_7") (pintype "input"))
      (node (ref "74LS161N") (pin "9") (pinfunction "LD_9") (pintype "input"))
      (node (ref "ALU-BUF") (pin "1") (pinfunction "DIR_1") (pintype "input"))
      (node (ref "AT28C16-0") (pin "21") (pinfunction "~{WE}_21") (pintype "input"))
      (node (ref "AT28C16-1") (pin "21") (pinfunction "~{WE}_21") (pintype "input"))
      (node (ref "AT28C16-2") (pin "21") (pinfunction "~{WE}_21") (pintype "input"))
      (node (ref "AT28C16-3") (pin "21") (pinfunction "~{WE}_21") (pintype "input"))
      (node (ref "EEPROM-AT28C16") (pin "21") (pinfunction "~{WE}_21") (pintype "input"))
      (node (ref "JK-FLIP-FLOP") (pin "16") (pinfunction "K_16") (pintype "input"))
      (node (ref "JK-FLIP-FLOP") (pin "2") (pinfunction "PRE_2") (pintype "input"))
      (node (ref "JK-FLIP-FLOP") (pin "3") (pinfunction "CLR_3") (pintype "input"))
      (node (ref "JK-FLIP-FLOP") (pin "4") (pinfunction "J_4") (pintype "input"))
      (node (ref "JK-FLIP-FLOP") (pin "7") (pinfunction "PRE_7") (pintype "input"))
      (node (ref "JK-FLIP-FLOP") (pin "8") (pinfunction "CLR_8") (pintype "input"))
      (node (ref "JK-FLIP-FLOP") (pin "9") (pinfunction "J_9") (pintype "input"))
      (node (ref "MEM-INT-BUF-0") (pin "1") (pinfunction "DIR_1") (pintype "input"))
      (node (ref "MEM-INT-BUF-1") (pin "1") (pinfunction "DIR_1") (pintype "input"))
      (node (ref "MEM-INT-BUF-2") (pin "1") (pinfunction "DIR_1") (pintype "input"))
      (node (ref "MEMORY-0-8KX8-6264") (pin "26") (pinfunction "CS2_26") (pintype "input"))
      (node (ref "MEMORY-0-8KX8-6264") (pin "28") (pinfunction "VCC_28") (pintype "power_in"))
      (node (ref "MEMORY-1-8KX8-6264") (pin "26") (pinfunction "CS2_26") (pintype "input"))
      (node (ref "MEMORY-1-8KX8-6264") (pin "28") (pinfunction "VCC_28") (pintype "power_in"))
      (node (ref "MEMORY-2-8KX8-6264") (pin "26") (pinfunction "CS2_26") (pintype "input"))
      (node (ref "MEMORY-2-8KX8-6264") (pin "28") (pinfunction "VCC_28") (pintype "power_in"))
      (node (ref "MEMORY-3-8KX8-6264") (pin "26") (pinfunction "CS2_26") (pintype "input"))
      (node (ref "MEMORY-3-8KX8-6264") (pin "28") (pinfunction "VCC_28") (pintype "power_in"))
      (node (ref "PC-BUF-H") (pin "1") (pinfunction "DIR_1") (pintype "input"))
      (node (ref "PC-BUF-L") (pin "1") (pinfunction "DIR_1") (pintype "input"))
      (node (ref "R1") (pin "2") (pinfunction "2_2") (pintype "passive"))
      (node (ref "R5") (pin "2") (pinfunction "2_2") (pintype "passive"))
      (node (ref "R9") (pin "1") (pinfunction "1_1") (pintype "passive"))
      (node (ref "REG-ACU-BUF0") (pin "1") (pinfunction "DIR_1") (pintype "input"))
      (node (ref "REG-ACU-BUF1") (pin "1") (pinfunction "DIR_1") (pintype "input"))
      (node (ref "REG-IO0-BUF") (pin "1") (pinfunction "DIR_1") (pintype "input"))
      (node (ref "REG-IO1-BUF") (pin "1") (pinfunction "DIR_1") (pintype "input"))
      (node (ref "REG-IO2-BUF") (pin "1") (pinfunction "DIR_1") (pintype "input"))
      (node (ref "REG-IO3-BUF") (pin "1") (pinfunction "DIR_1") (pintype "input"))
      (node (ref "REG-IR-BUF") (pin "1") (pinfunction "DIR_1") (pintype "input"))
      (node (ref "REG-MAR-BUF") (pin "1") (pinfunction "DIR_1") (pintype "input"))
      (node (ref "REG-MBR-BUF0") (pin "1") (pinfunction "DIR_1") (pintype "input"))
      (node (ref "REG-MBR-BUF1") (pin "1") (pinfunction "DIR_1") (pintype "input"))
      (node (ref "S3") (pin "3") (pinfunction "P_3") (pintype "passive"))
      (node (ref "SEG-SWITCH") (pin "4") (pinfunction "R_4") (pintype "input"))
      (node (ref "SEG-SWITCH") (pin "8") (pinfunction "V+_8") (pintype "power_in"))
    )
    (net (code "369") (name "unconnected-(MEMORY-0-8KX8-6264-NC-Pad1)") (class "Default")
      (node (ref "MEMORY-0-8KX8-6264") (pin "1") (pinfunction "NC_1") (pintype "no_connect"))
    )
    (net (code "370") (name "unconnected-(MEMORY-1-8KX8-6264-NC-Pad1)") (class "Default")
      (node (ref "MEMORY-1-8KX8-6264") (pin "1") (pinfunction "NC_1") (pintype "no_connect"))
    )
    (net (code "371") (name "unconnected-(MEMORY-2-8KX8-6264-NC-Pad1)") (class "Default")
      (node (ref "MEMORY-2-8KX8-6264") (pin "1") (pinfunction "NC_1") (pintype "no_connect"))
    )
    (net (code "372") (name "unconnected-(MEMORY-3-8KX8-6264-NC-Pad1)") (class "Default")
      (node (ref "MEMORY-3-8KX8-6264") (pin "1") (pinfunction "NC_1") (pintype "no_connect"))
    )
    (net (code "373") (name "unconnected-(REG-MBR-BUF1A-G-Pad19)") (class "Default")
      (node (ref "REG-MBR-BUF1") (pin "19") (pinfunction "G_19") (pintype "input"))
    )
    (net (code "374") (name "unconnected-(S1-P1-Pad4)") (class "Default")
      (node (ref "S1") (pin "4") (pinfunction "P1_4") (pintype "passive"))
    )
    (net (code "375") (name "unconnected-(S1-S1-Pad2)") (class "Default")
      (node (ref "S1") (pin "2") (pinfunction "S1_2") (pintype "passive"))
    )
  )
)
